# DL0WH_BiTuner_Ctrl_1V3.net
KiCad netlist of a schematic drawn in EAGLE
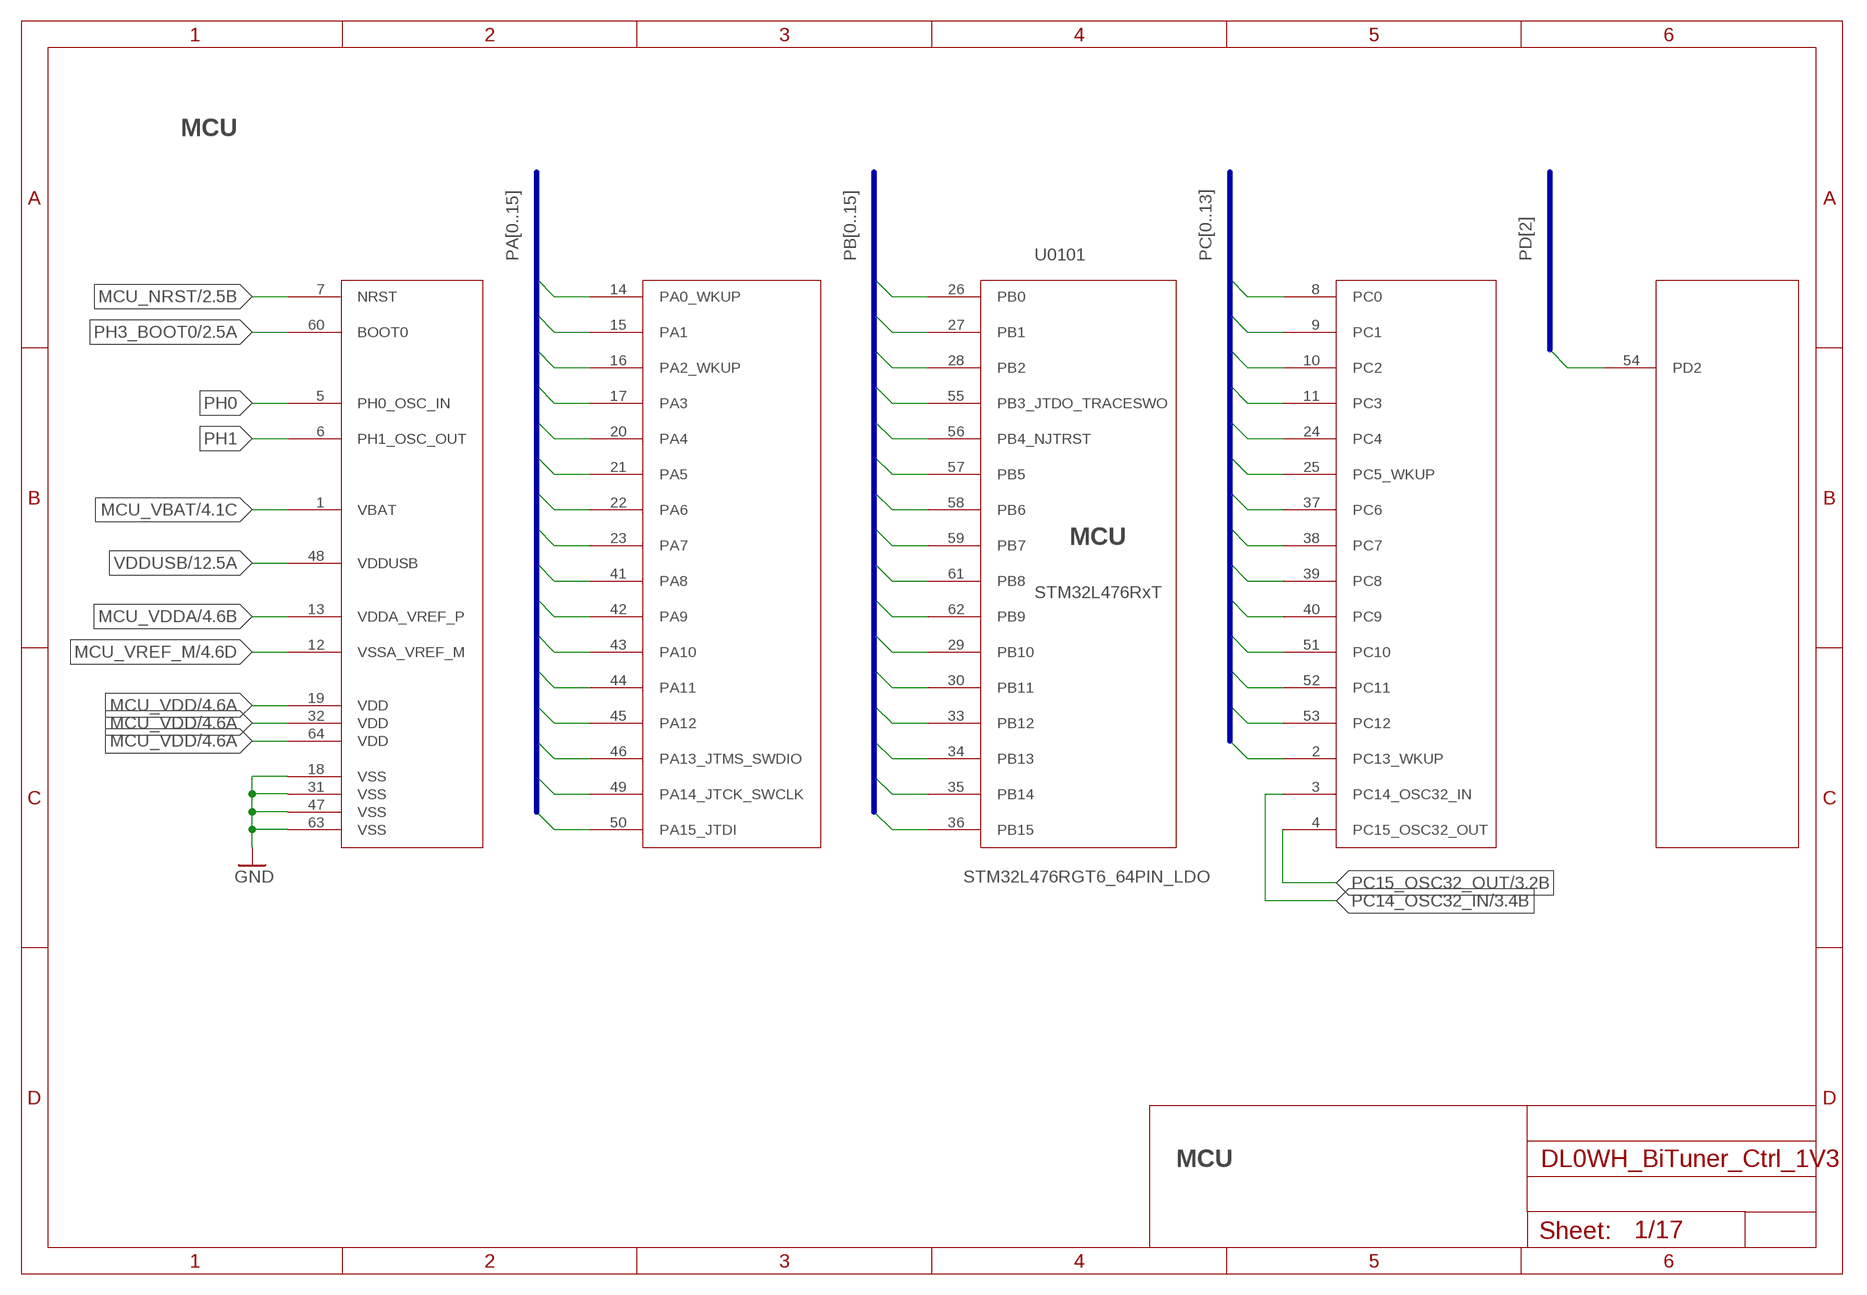
[diagram p0: schematic, sheet 1]
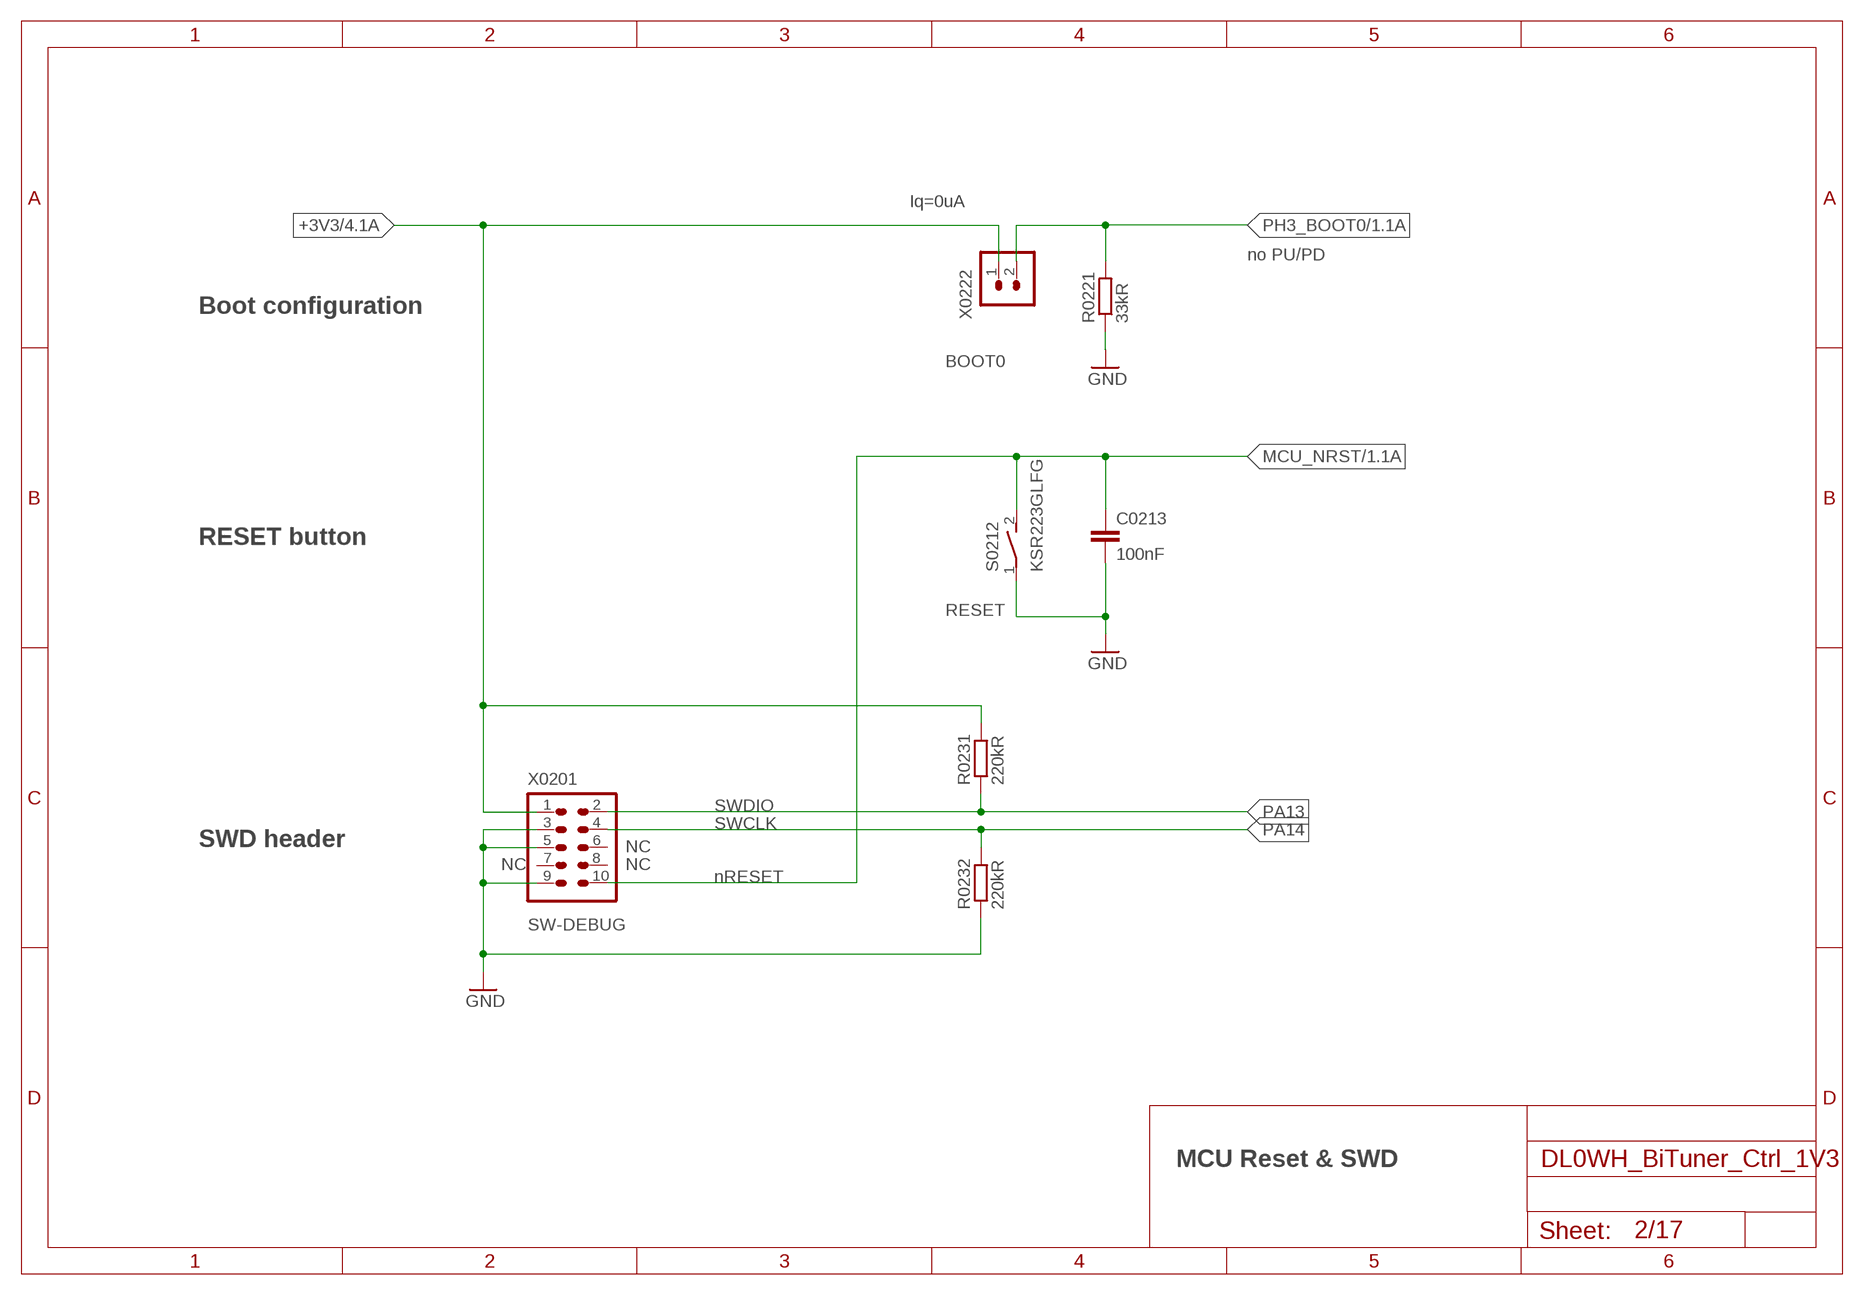
[diagram p1: schematic, sheet 2]
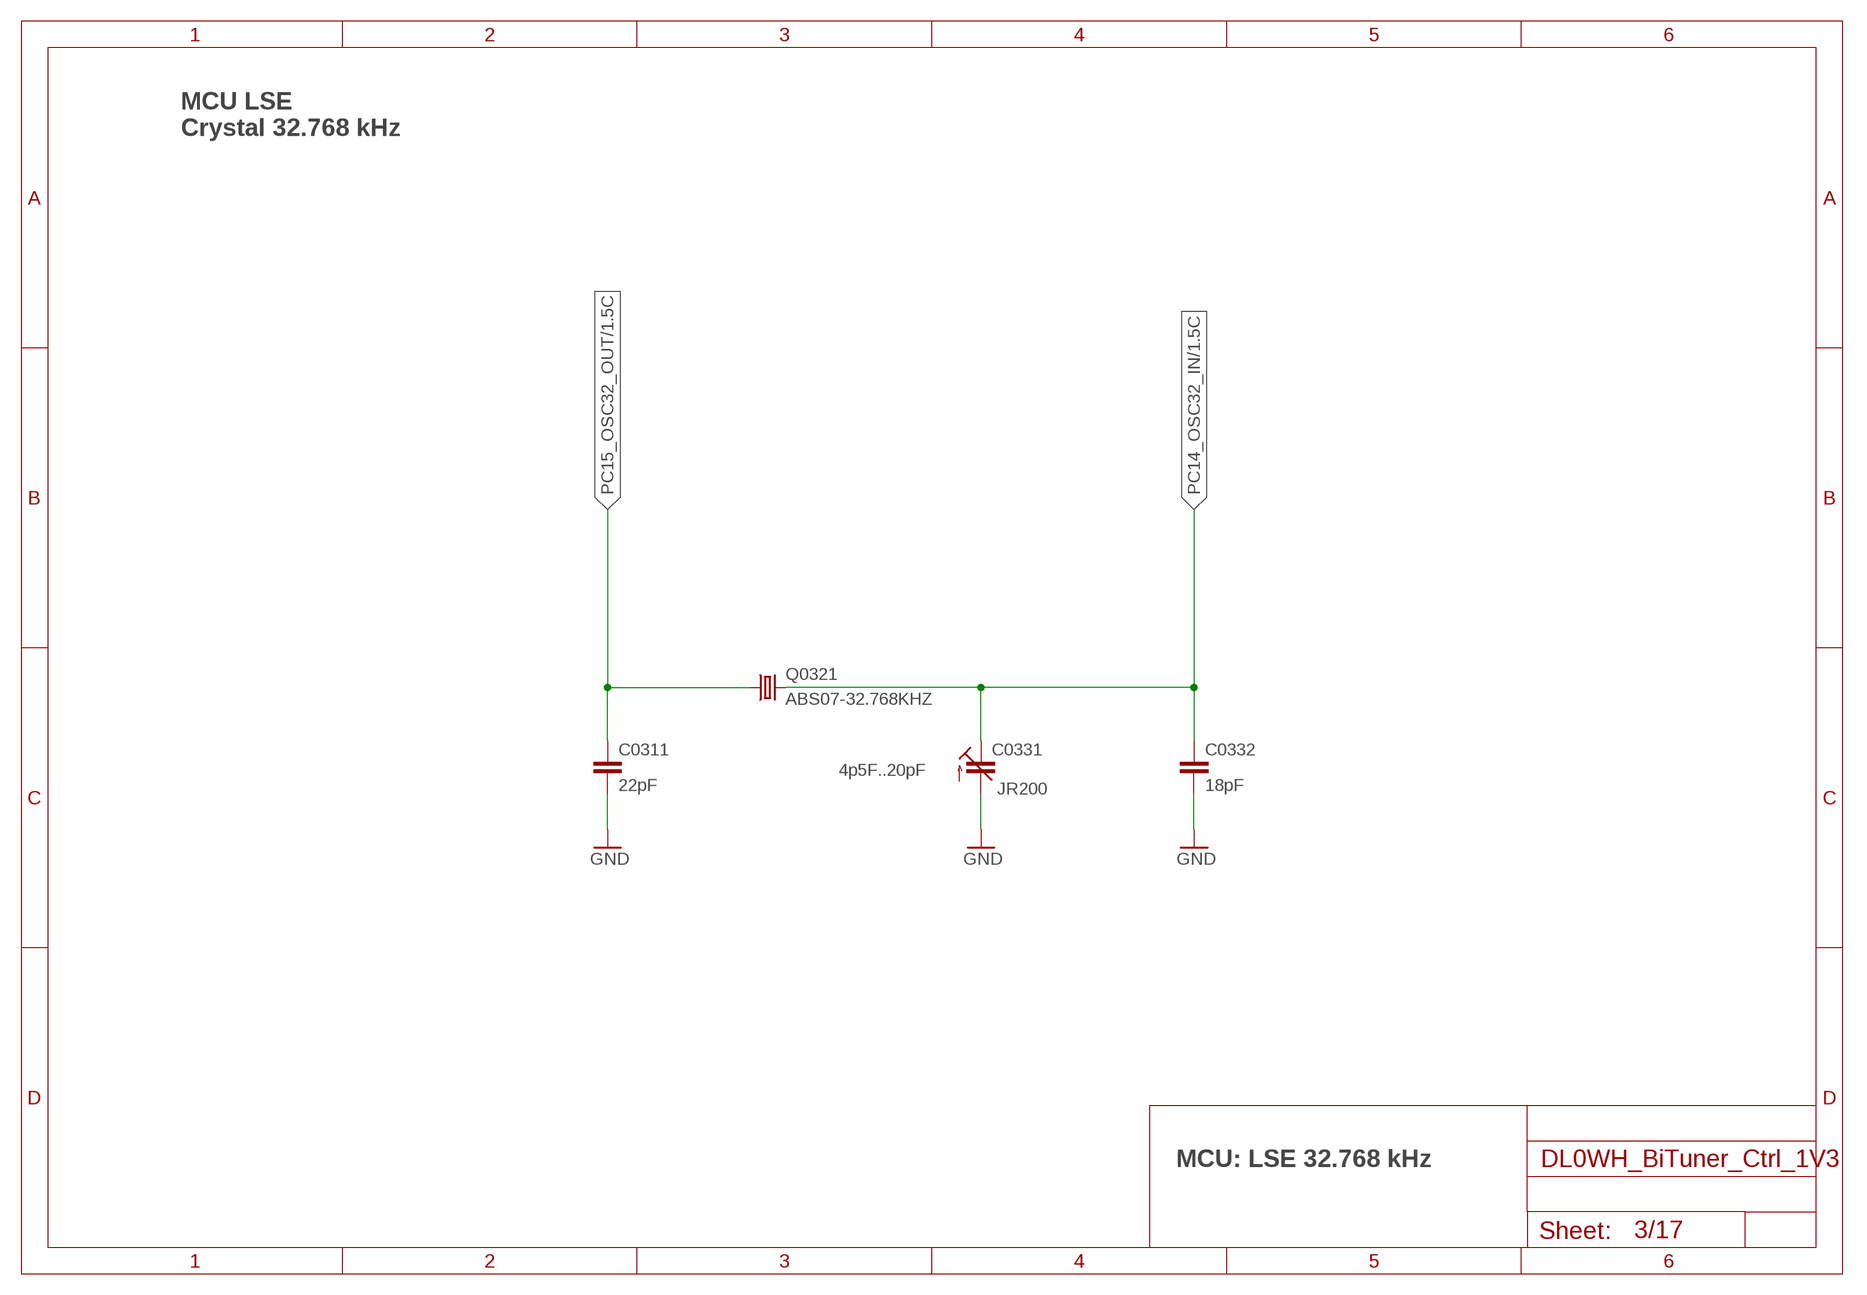
[diagram p2: schematic, sheet 3]
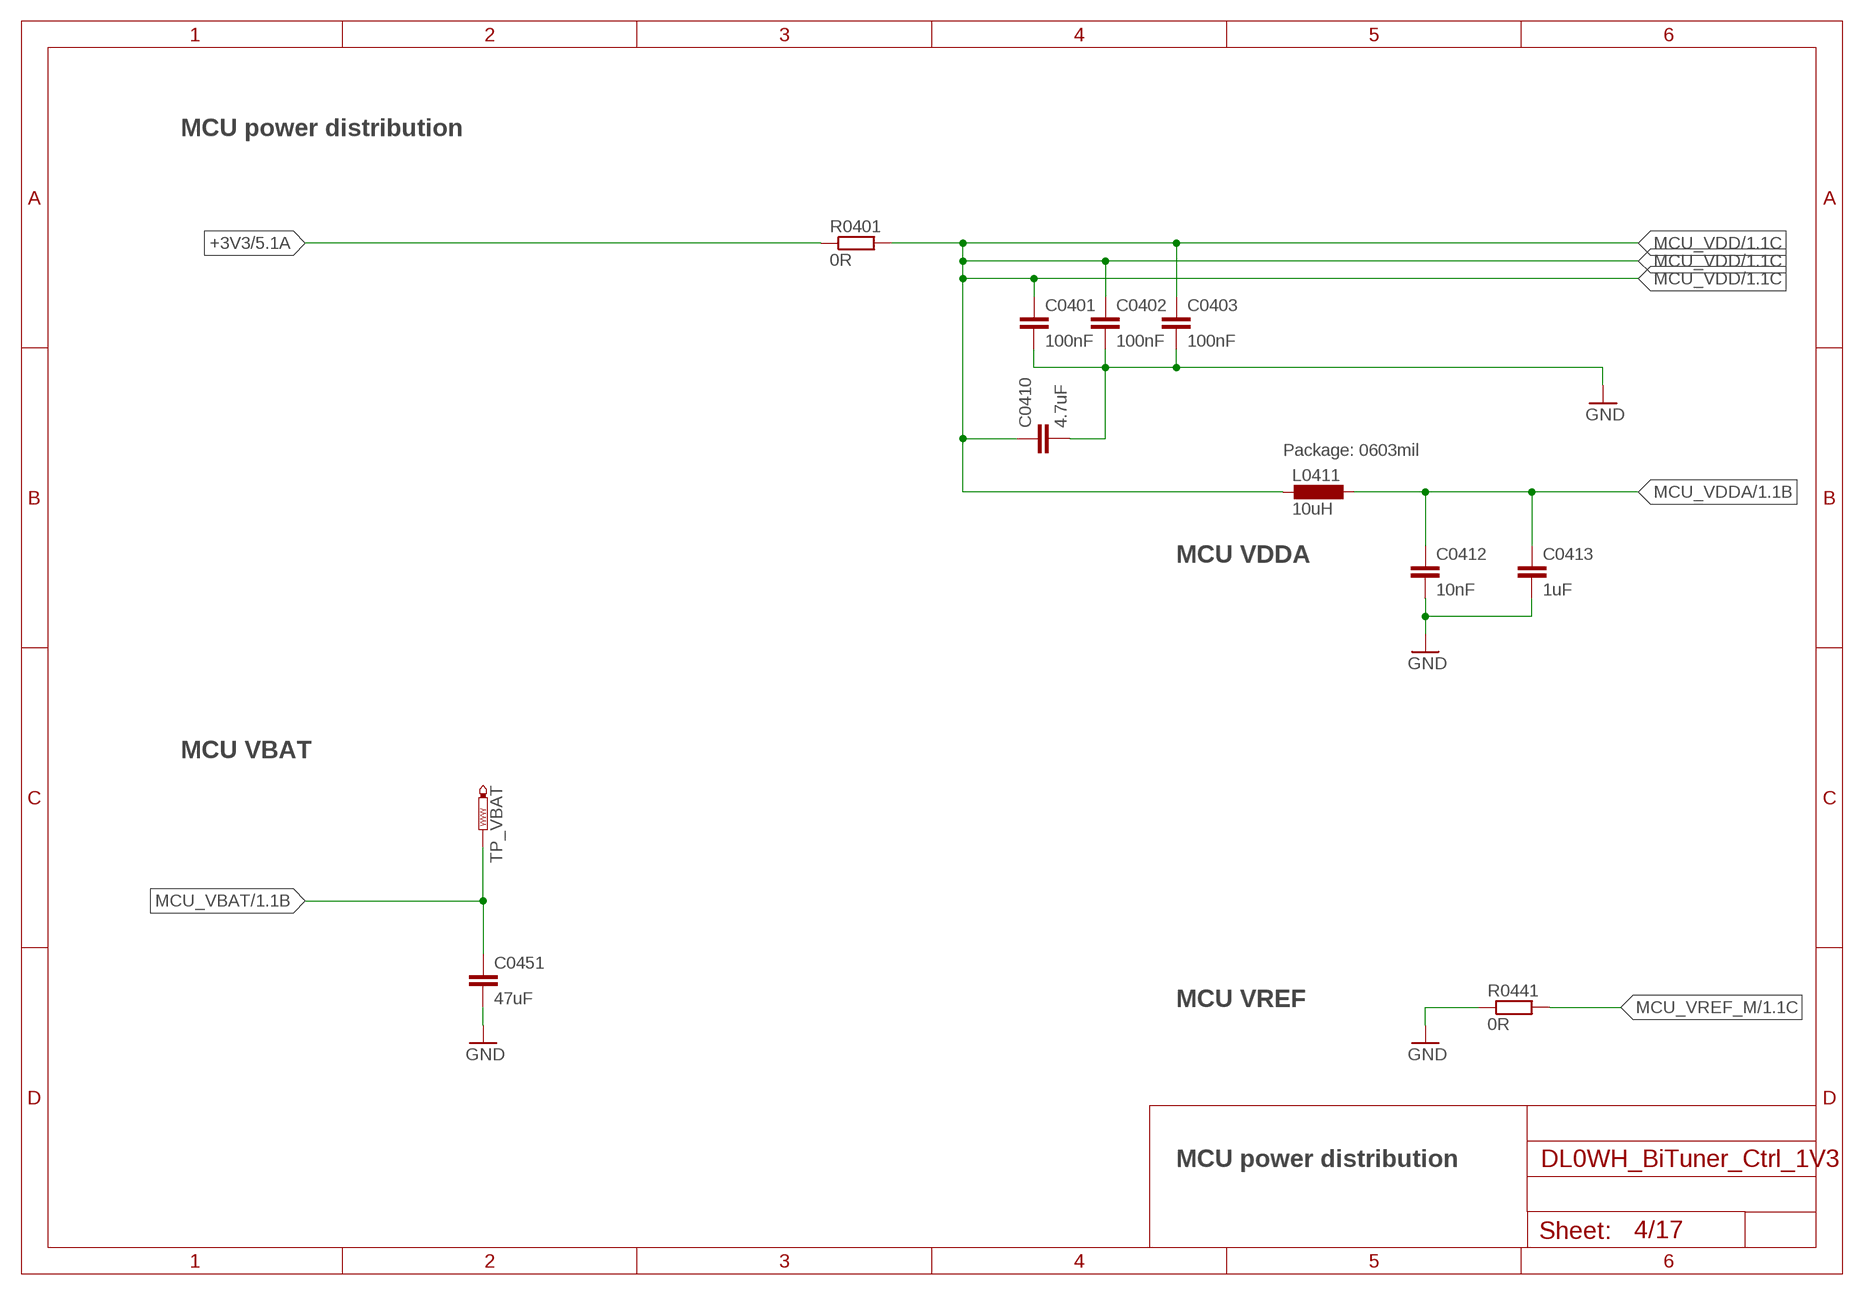
[diagram p3: schematic, sheet 4]
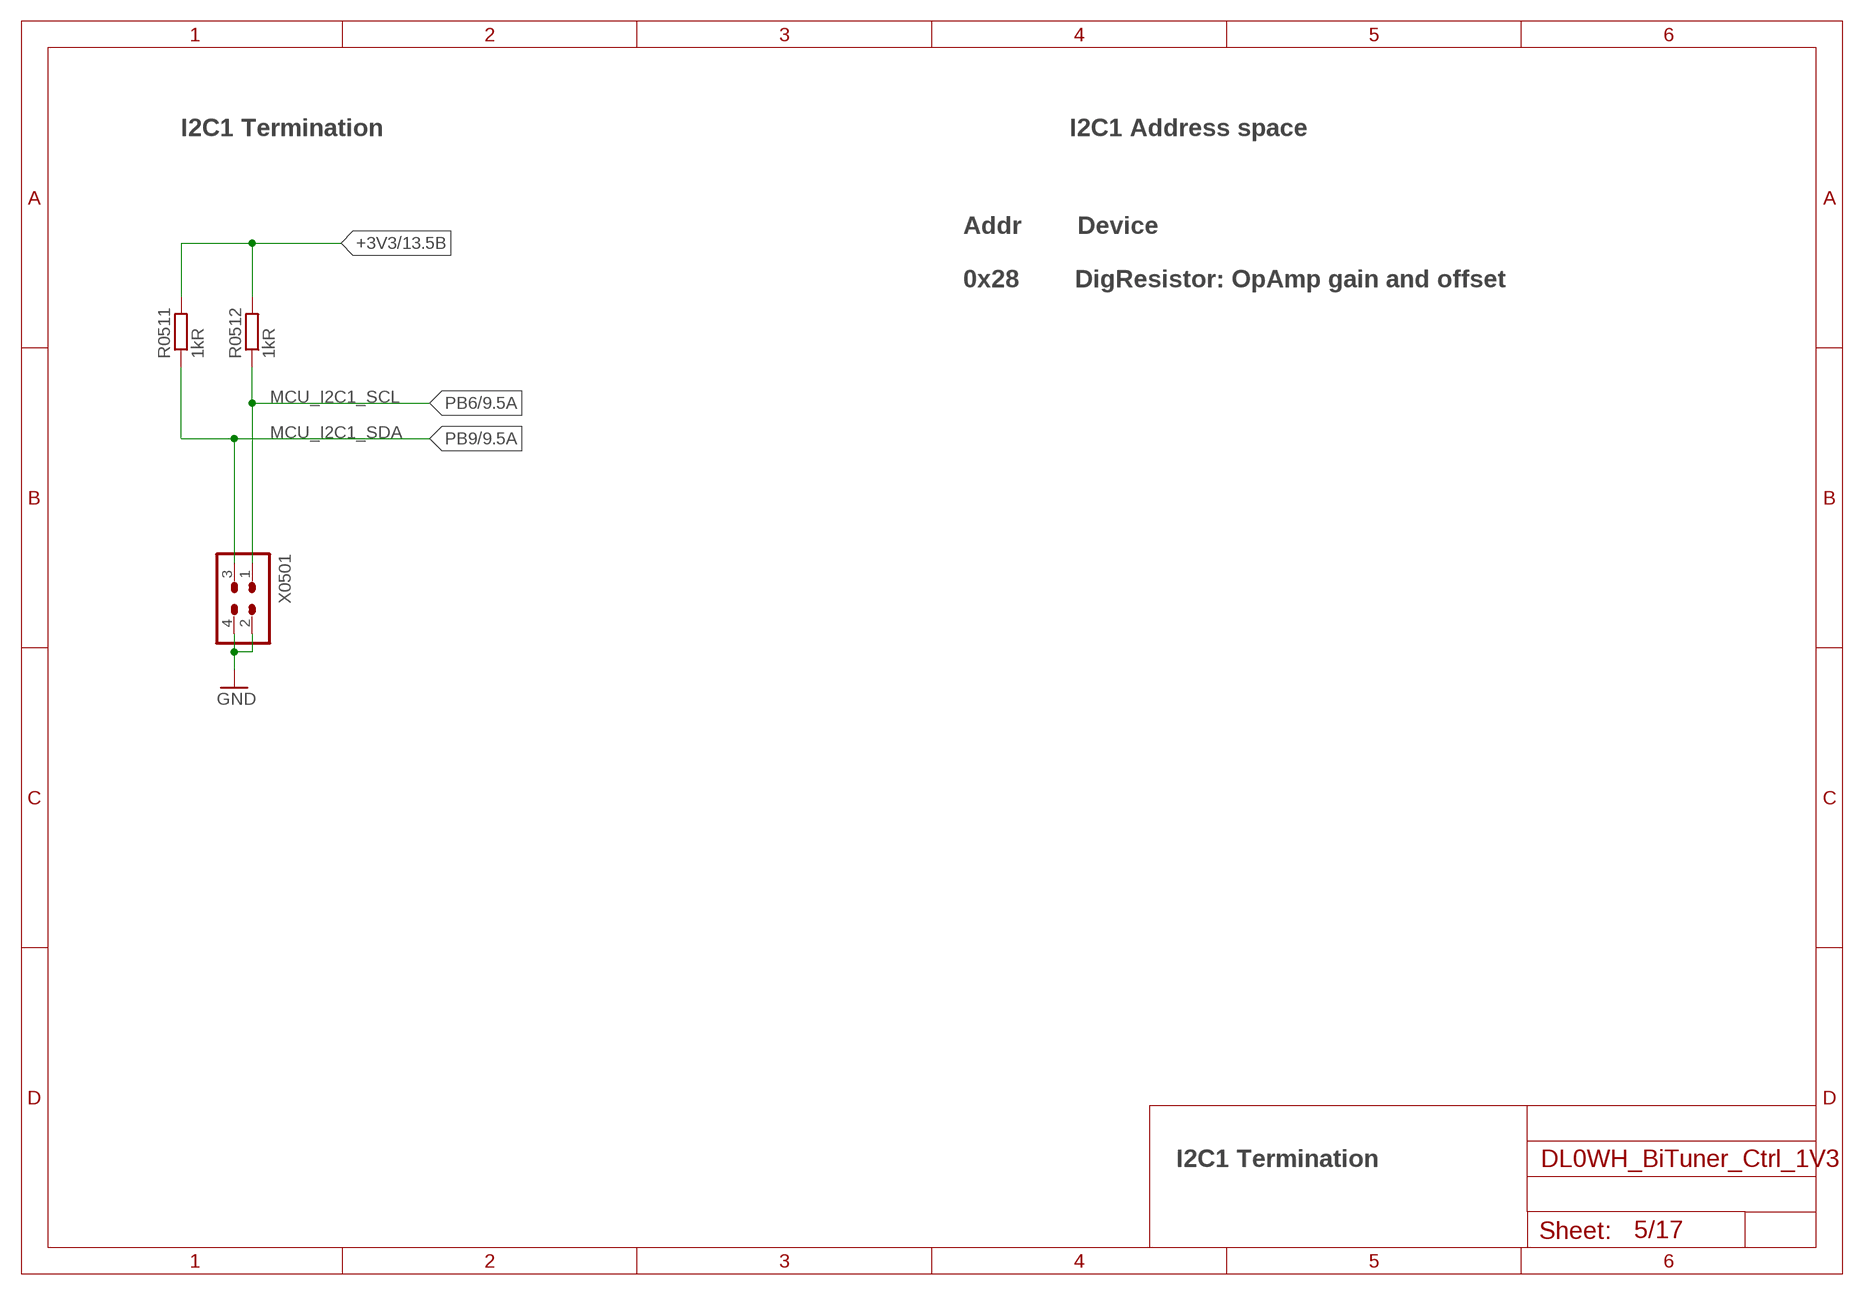
[diagram p4: schematic, sheet 5]
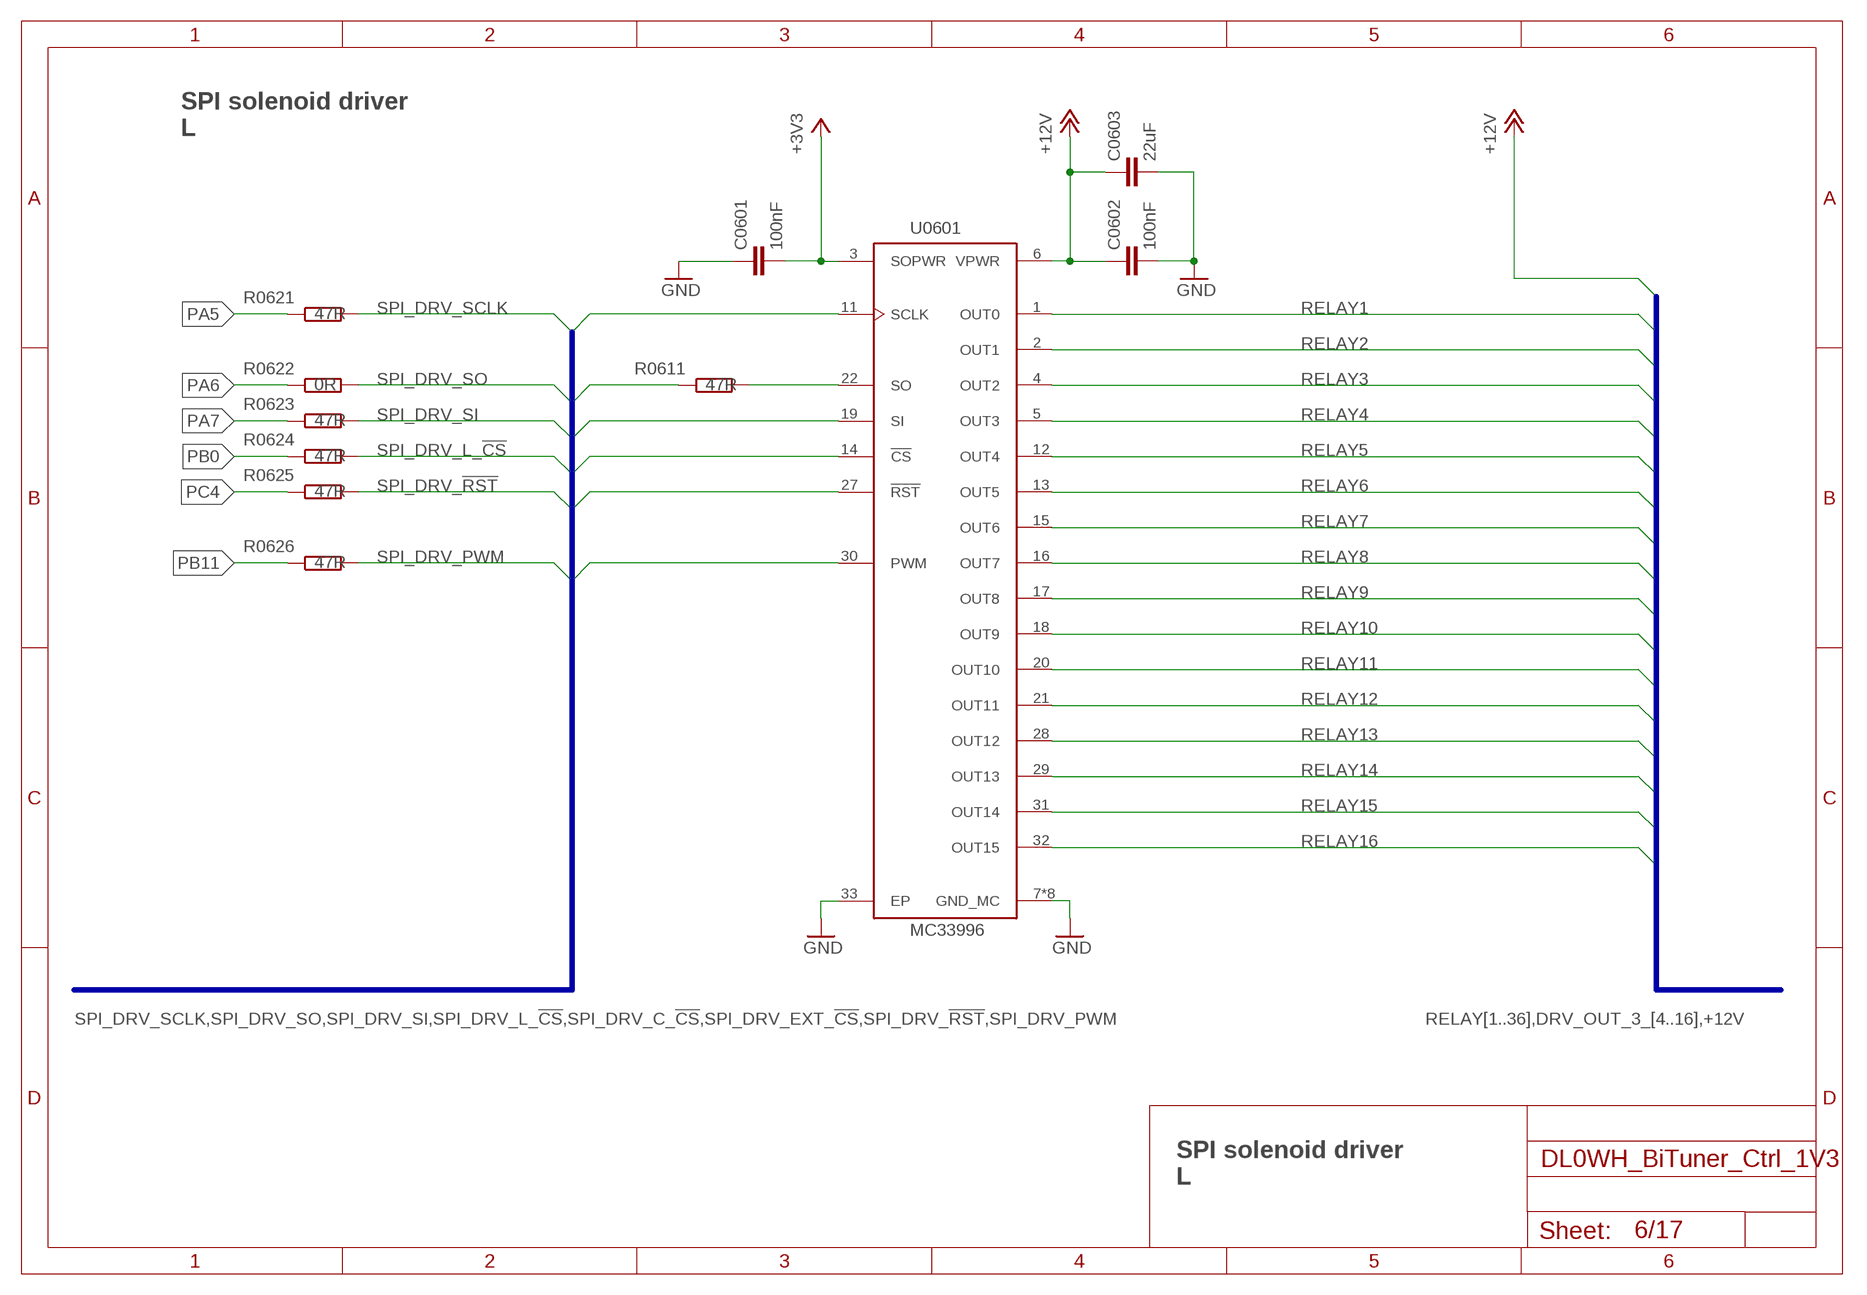
[diagram p5: schematic, sheet 6]
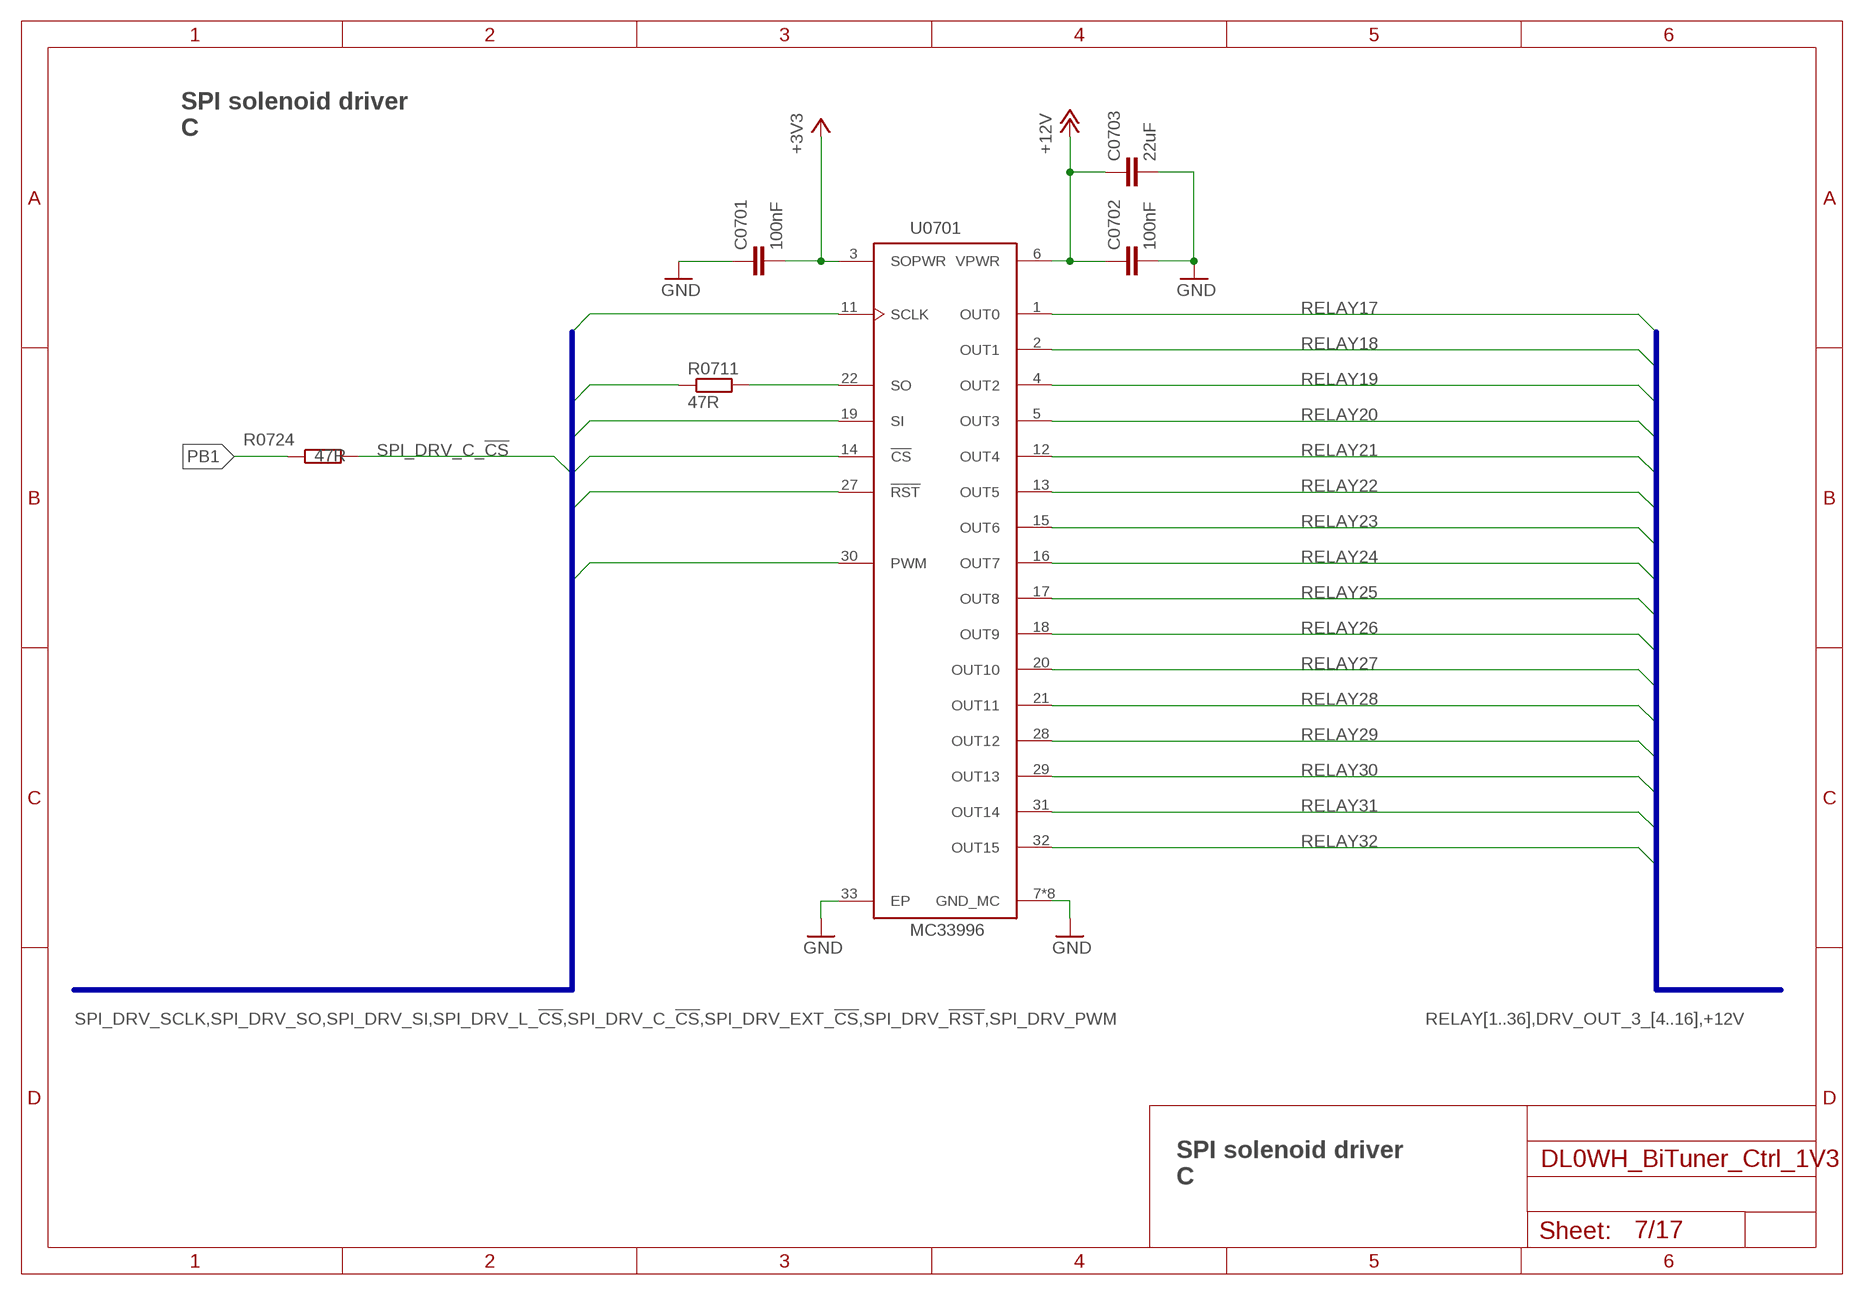
[diagram p6: schematic, sheet 7]
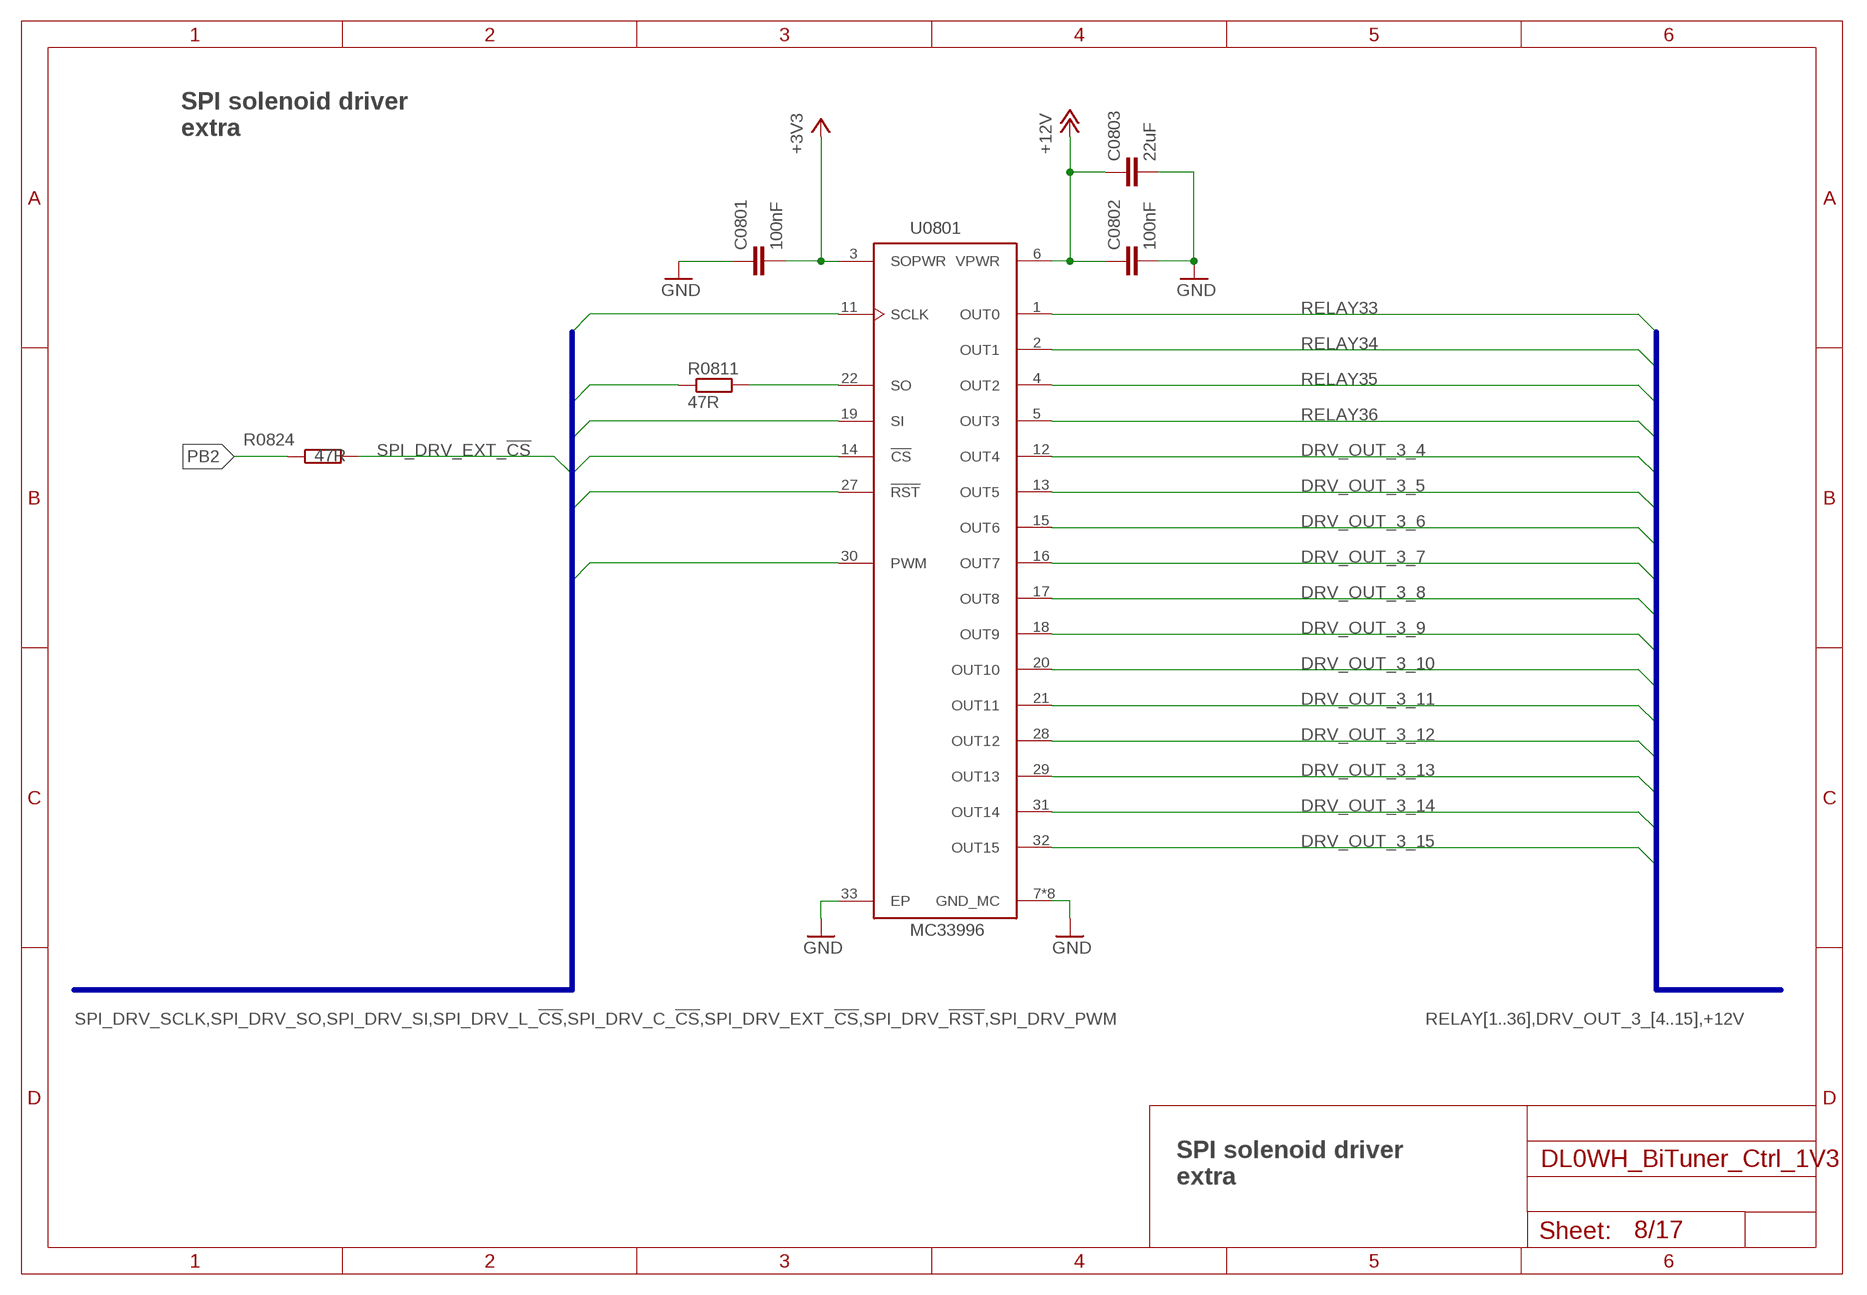
[diagram p7: schematic, sheet 8]
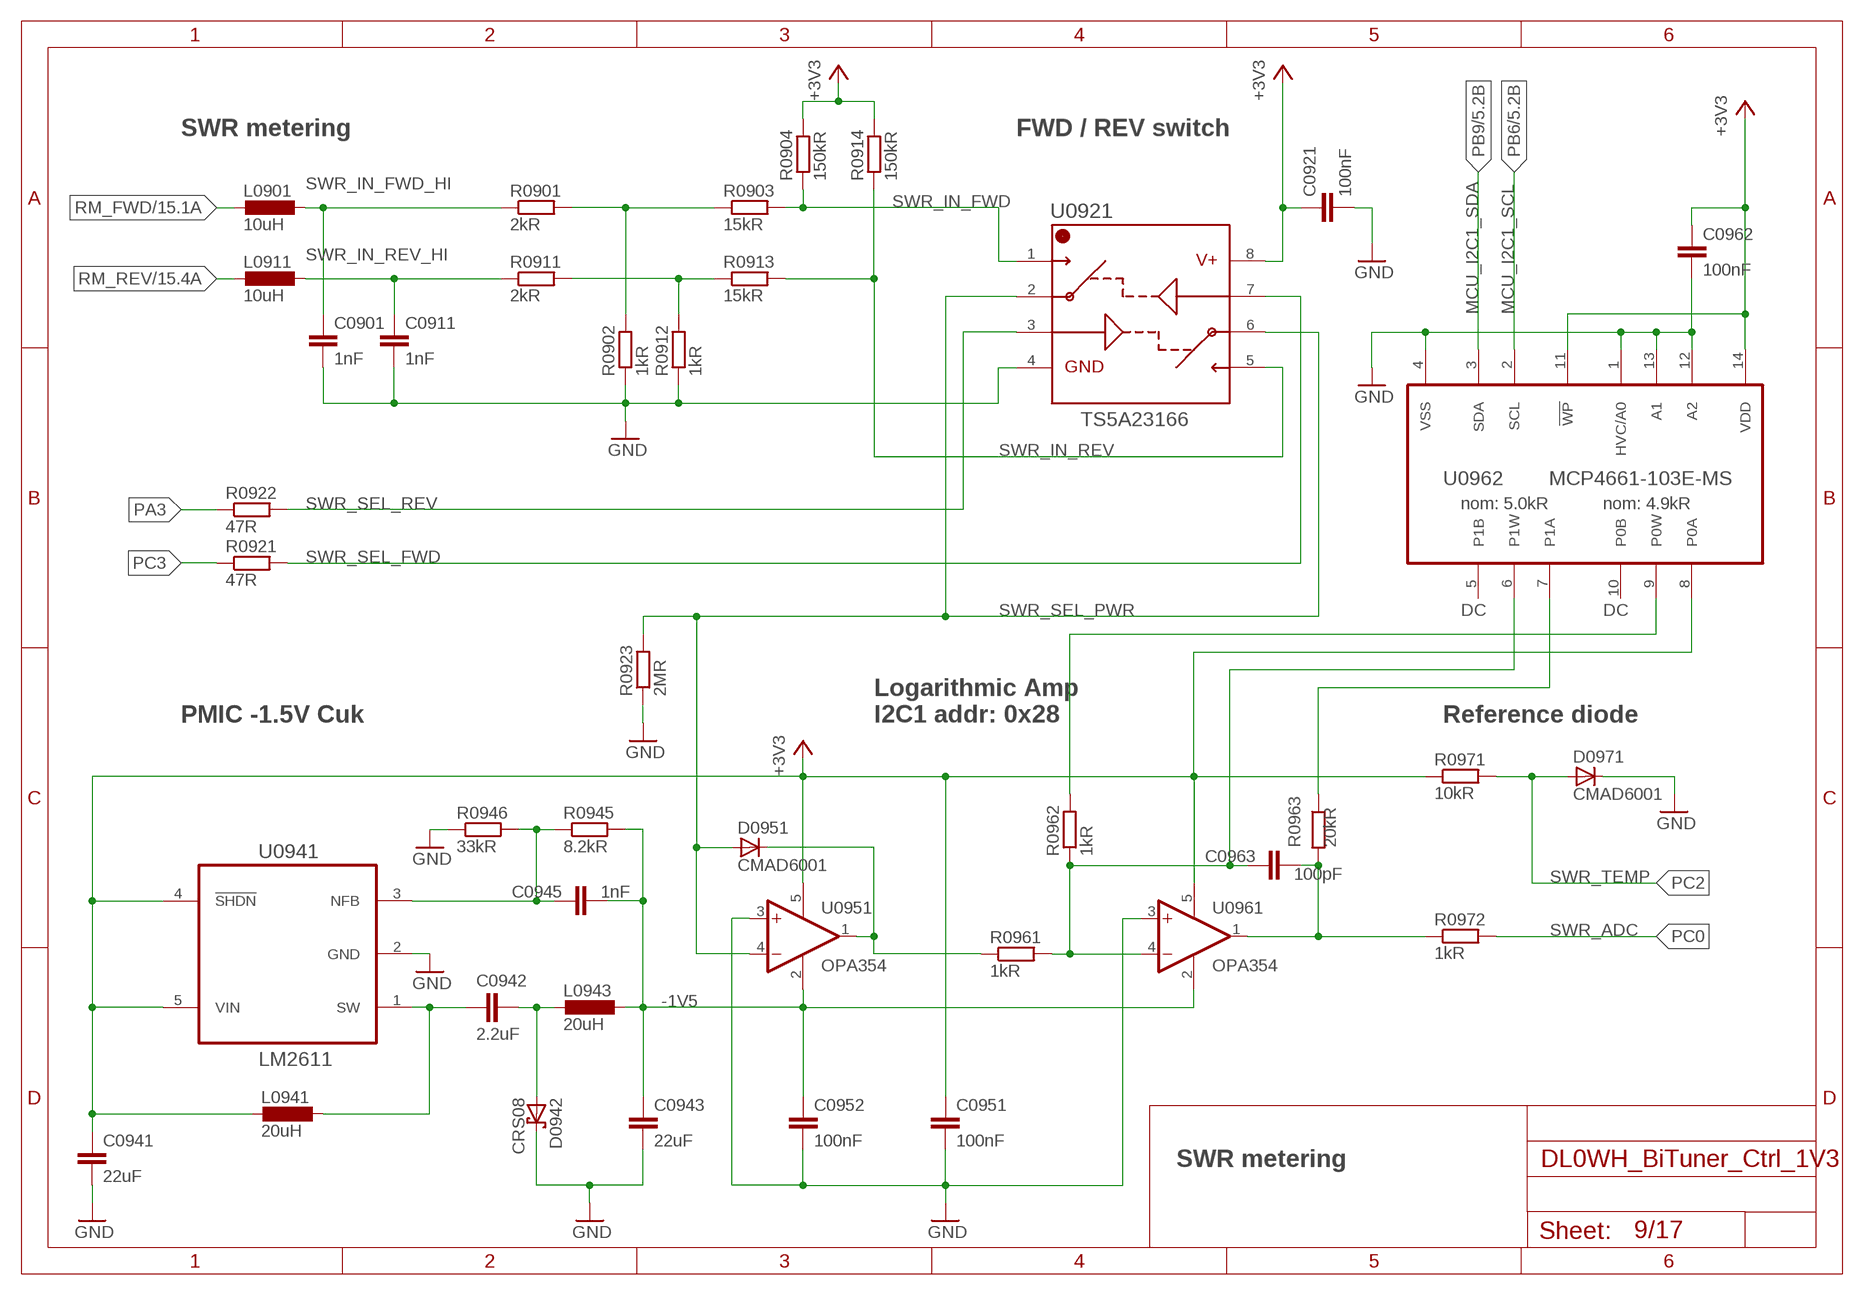
[diagram p8: schematic, sheet 9]
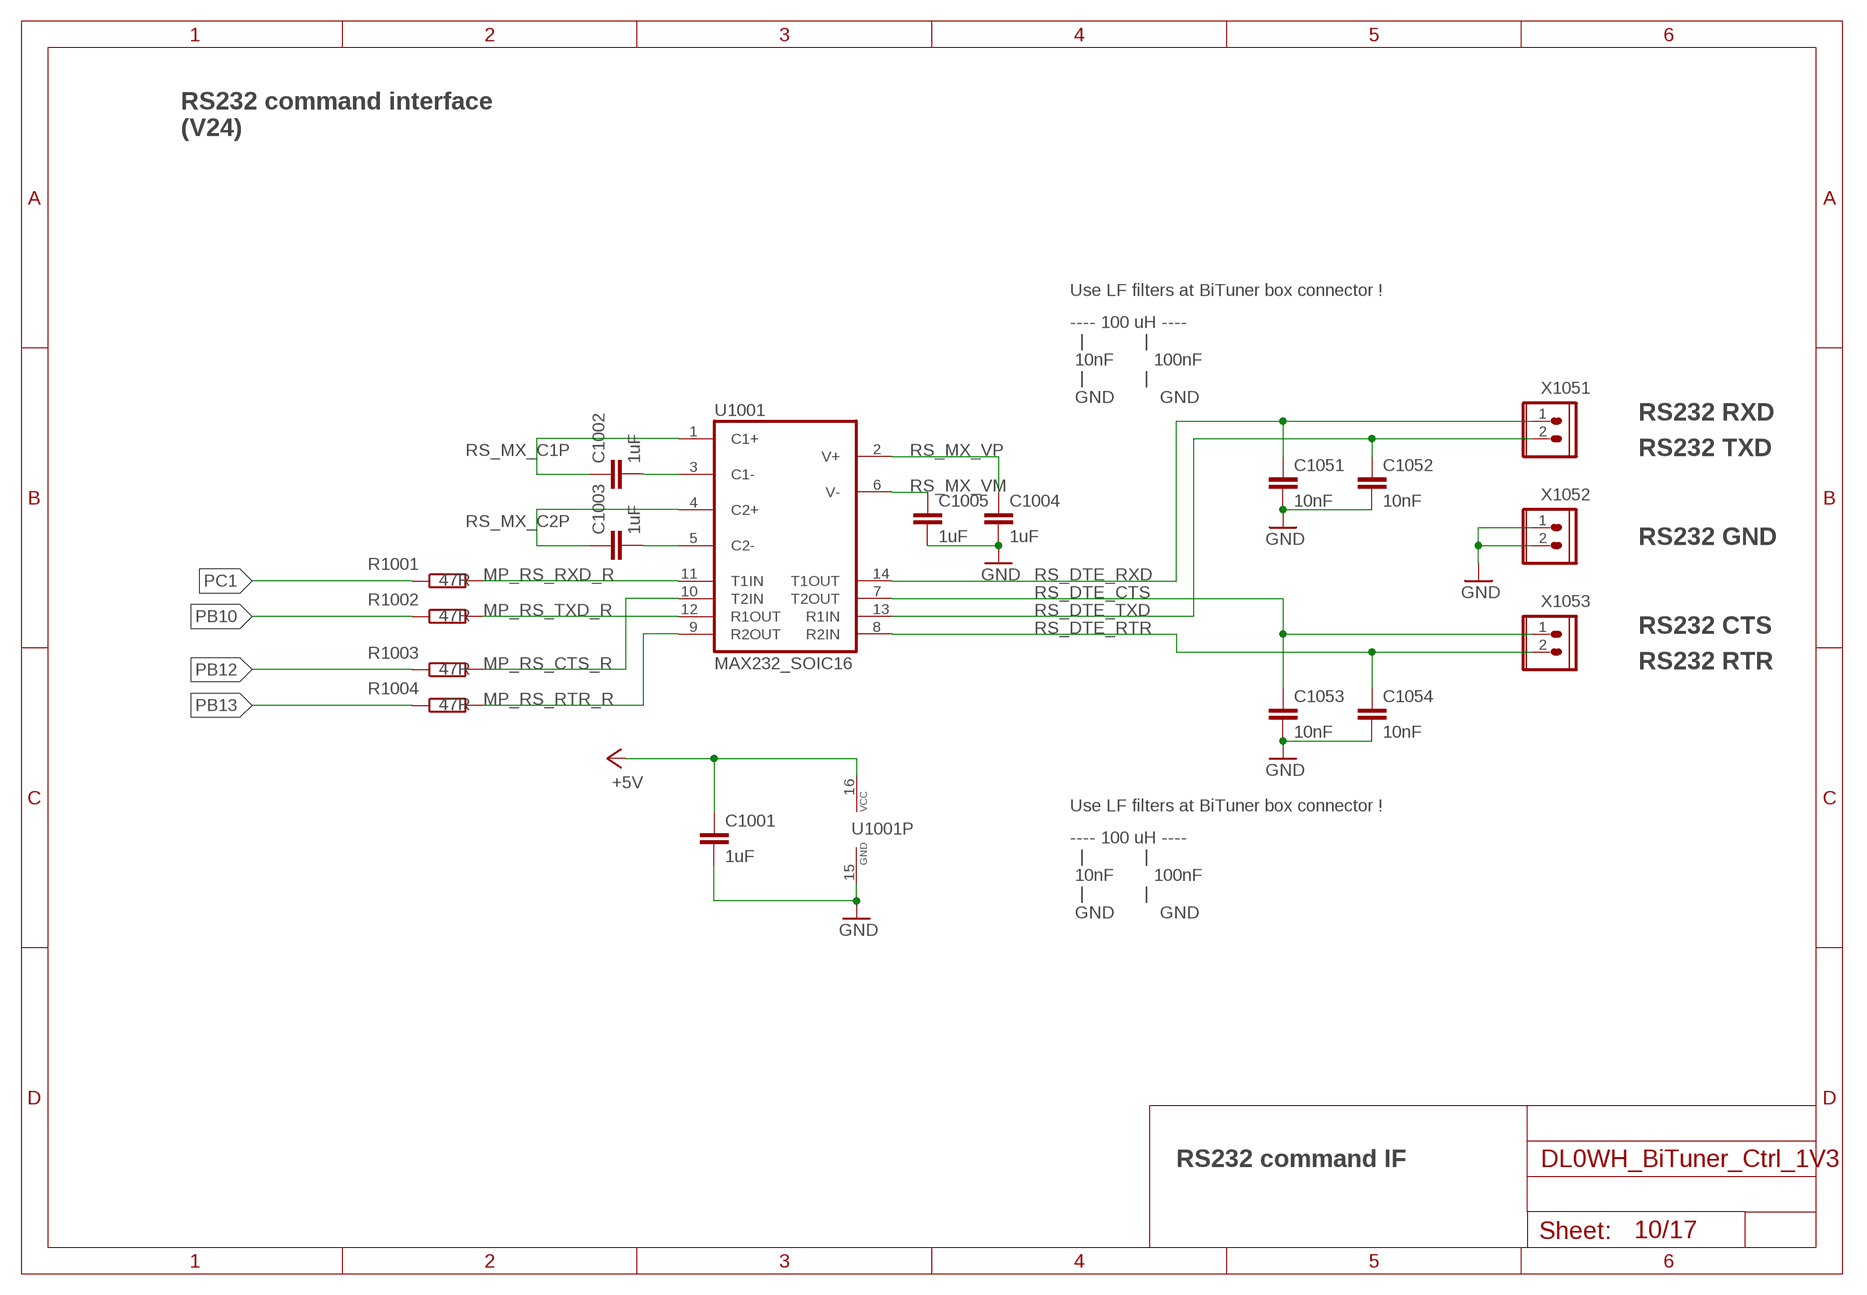
[diagram p9: schematic, sheet 10]
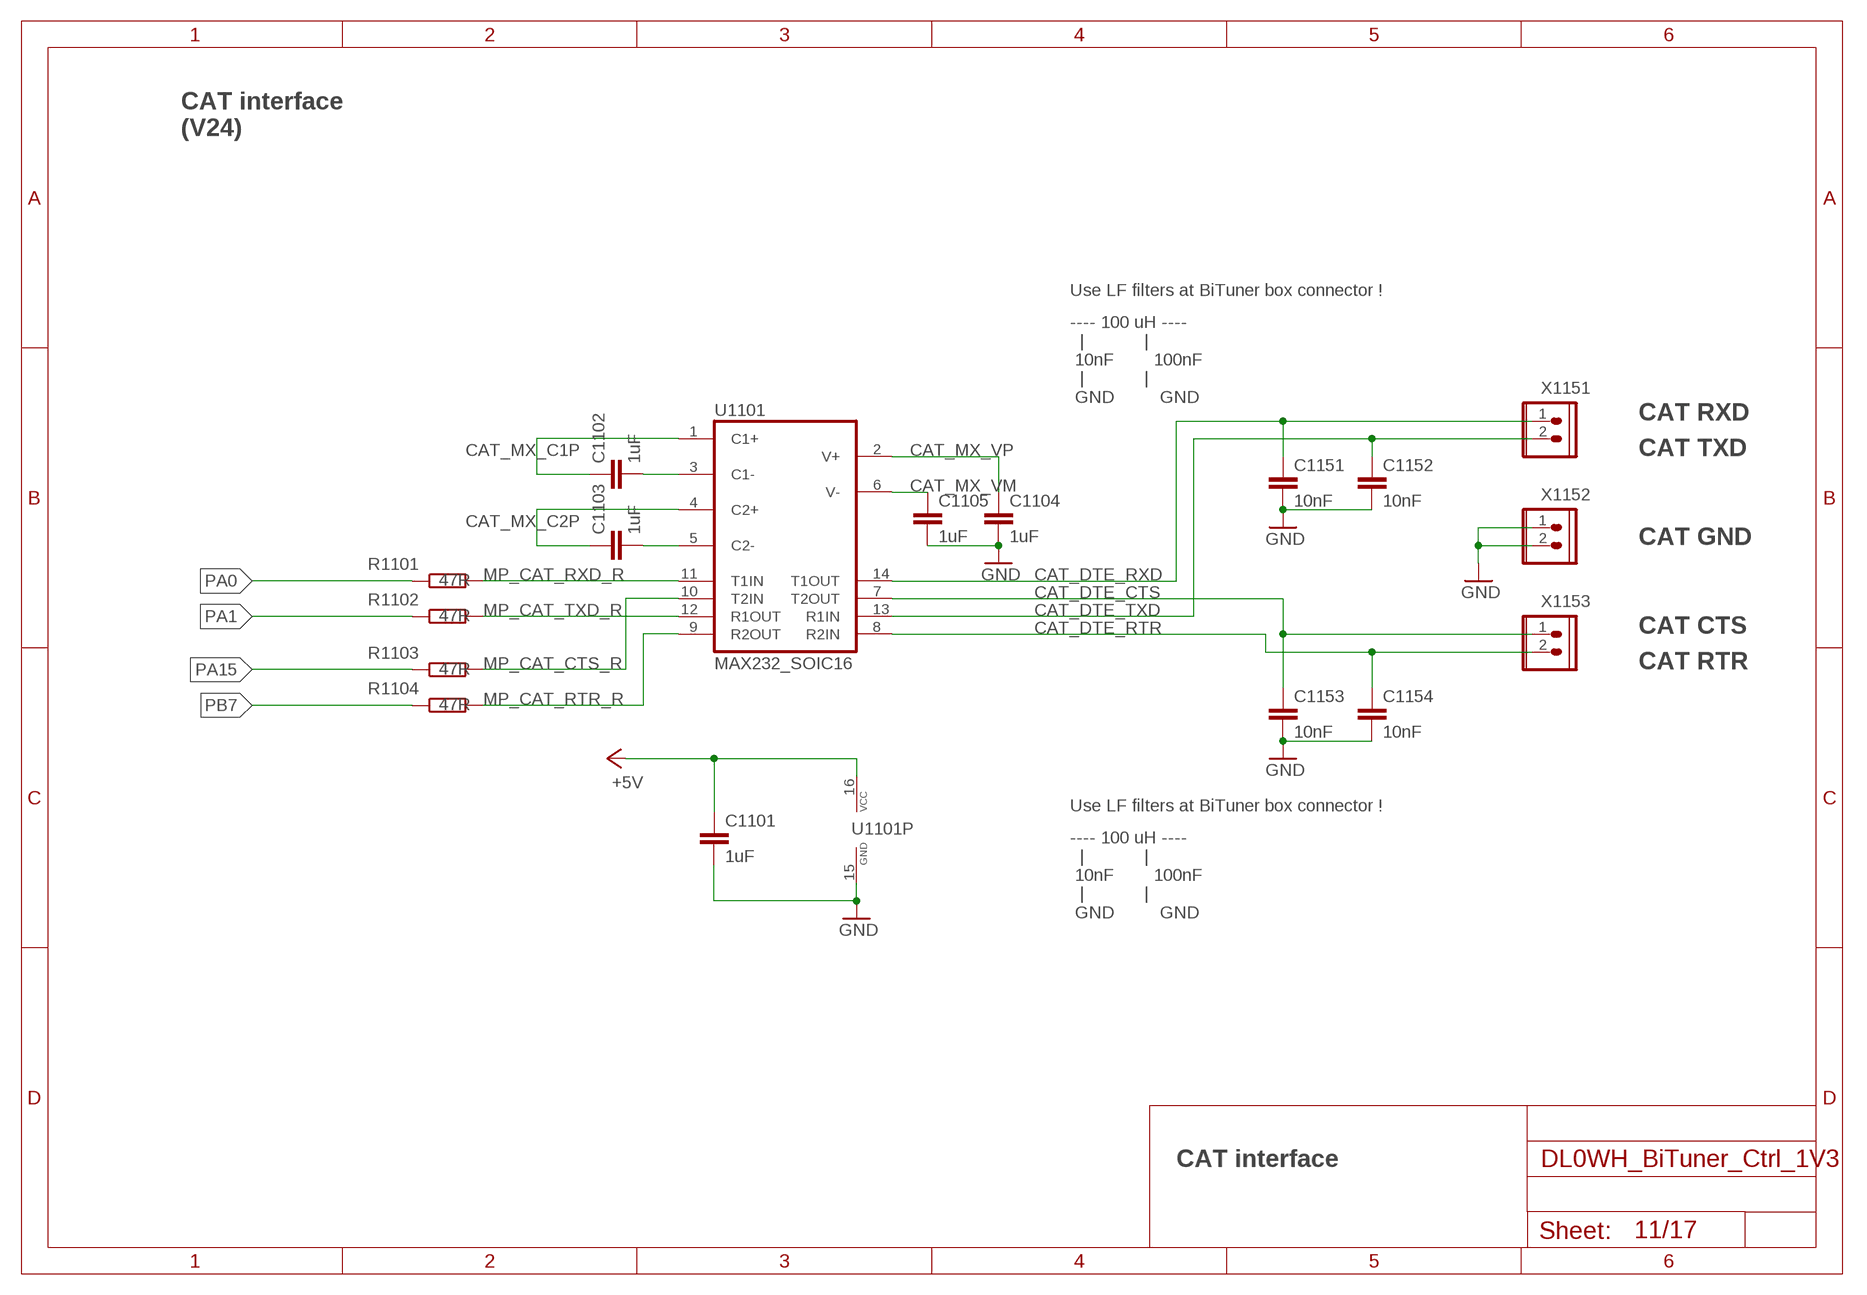
[diagram p10: schematic, sheet 11]
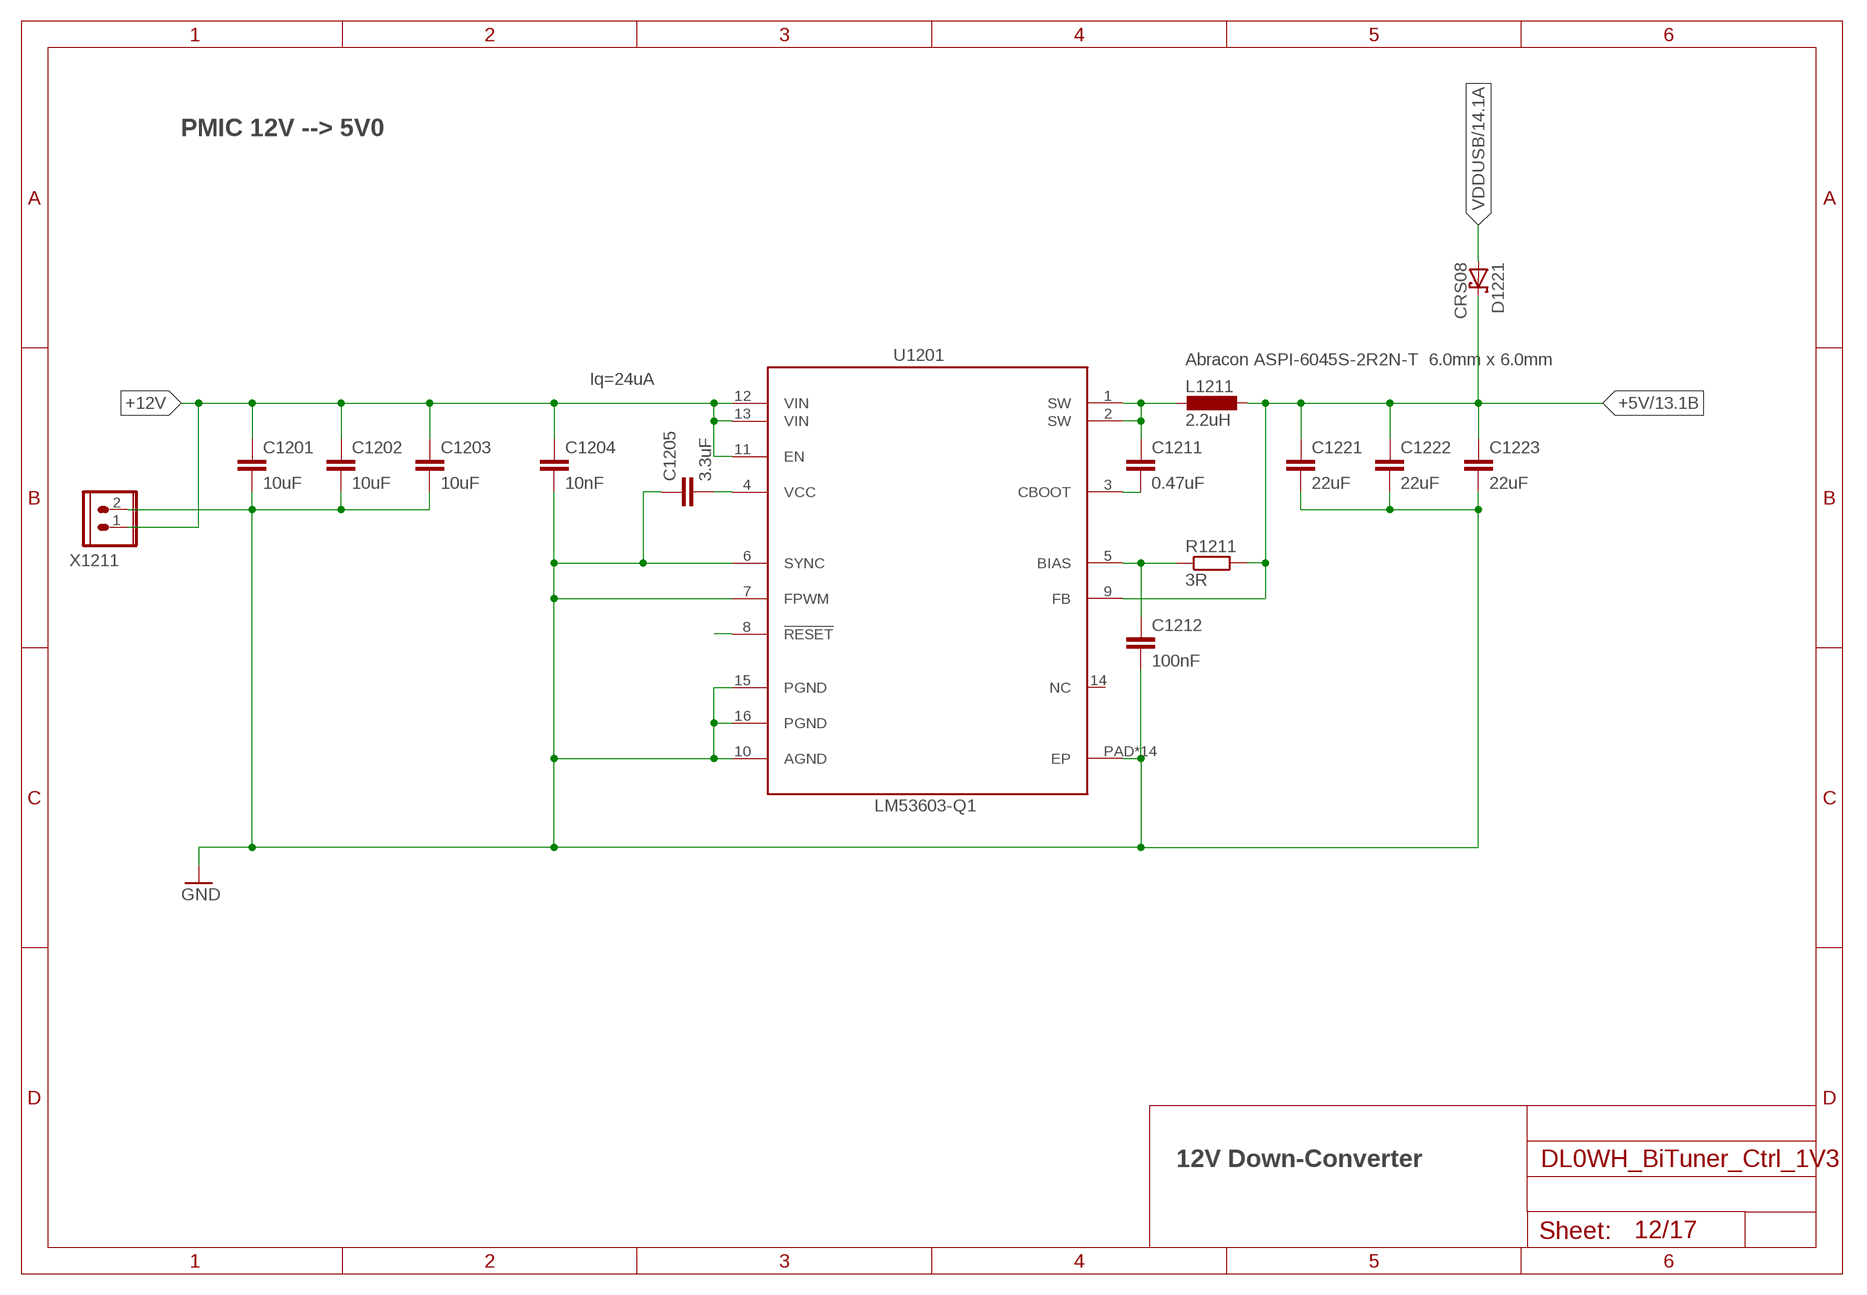
[diagram p11: schematic, sheet 12]
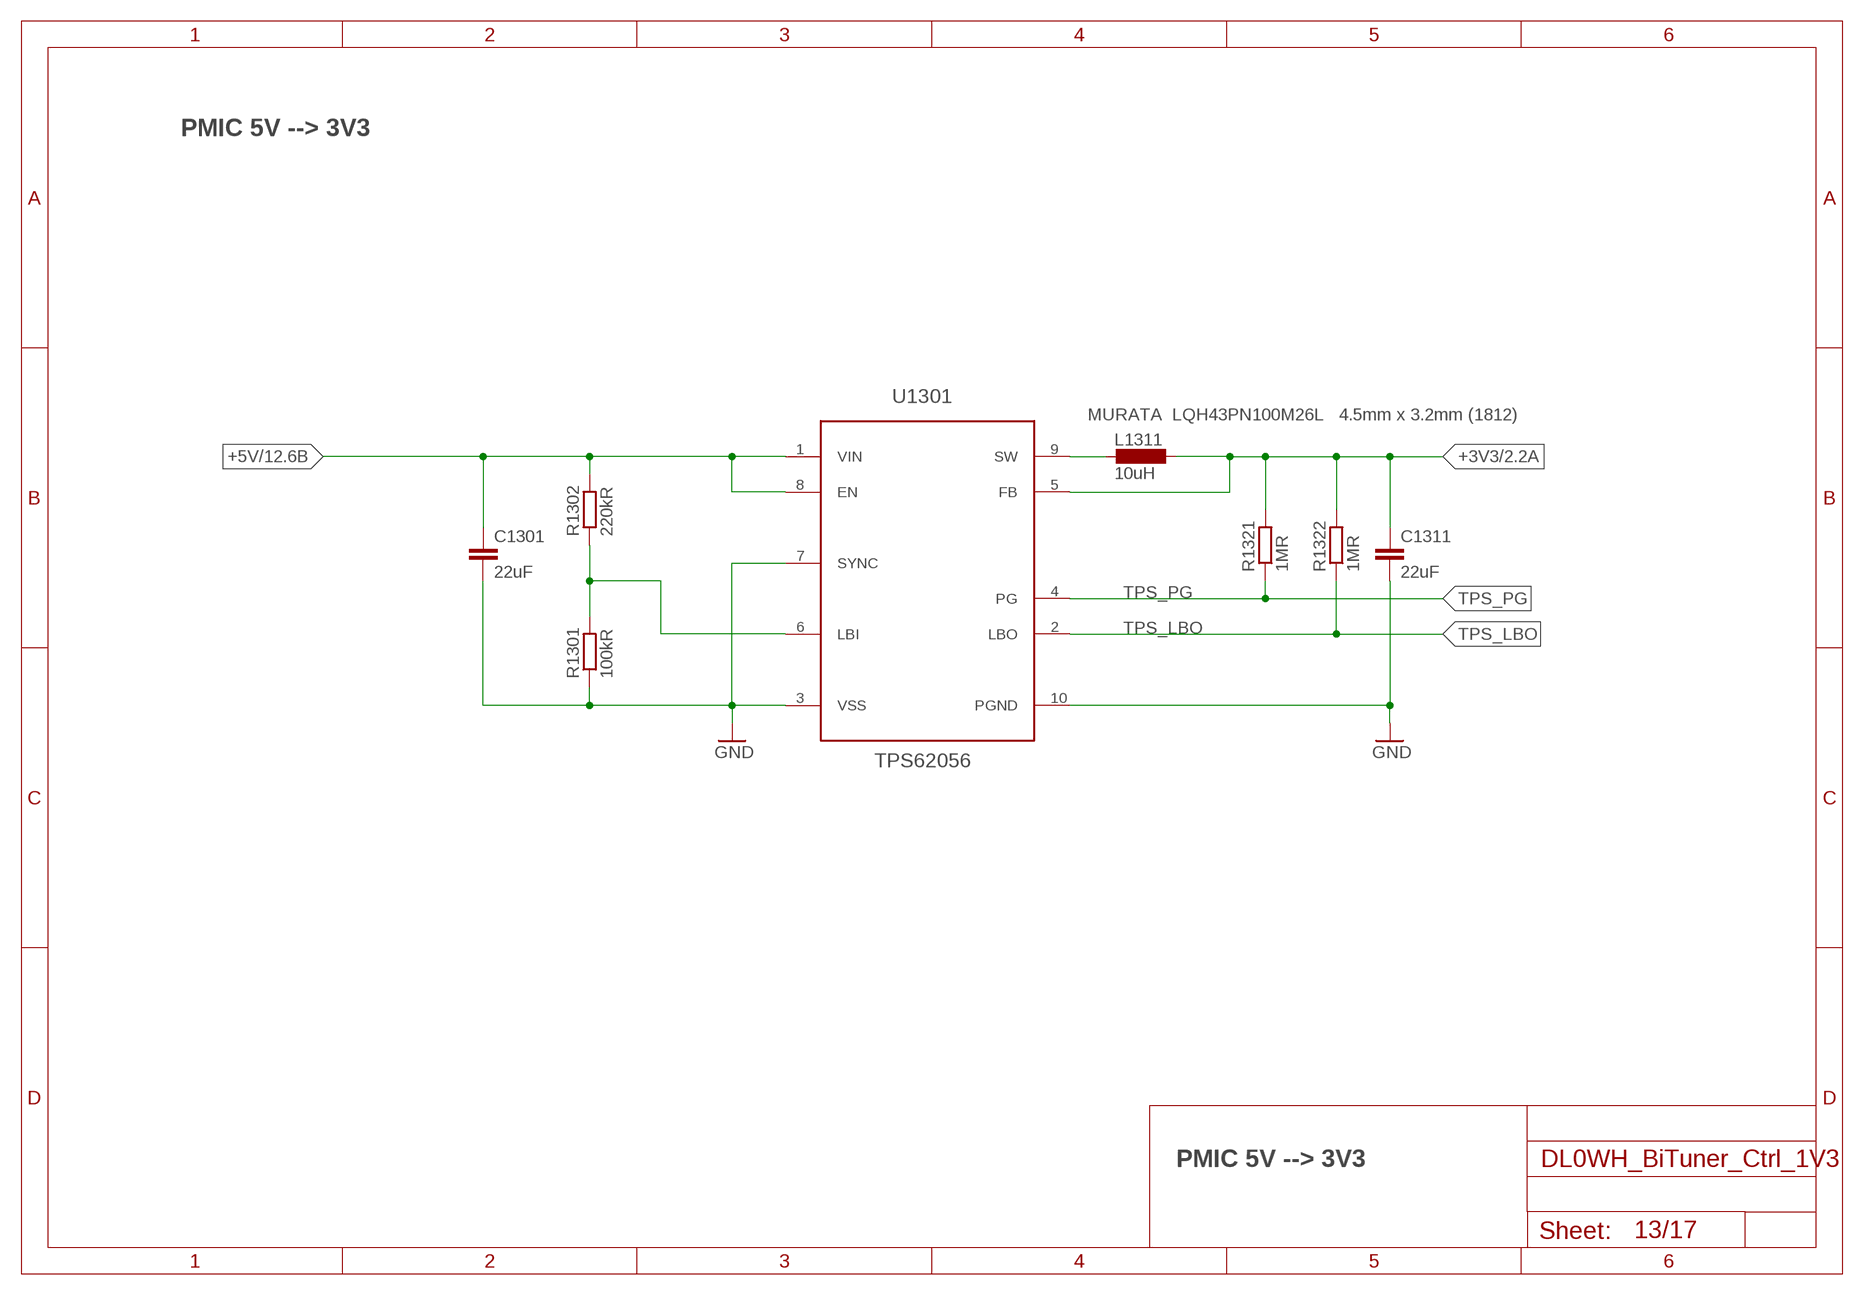
[diagram p12: schematic, sheet 13]
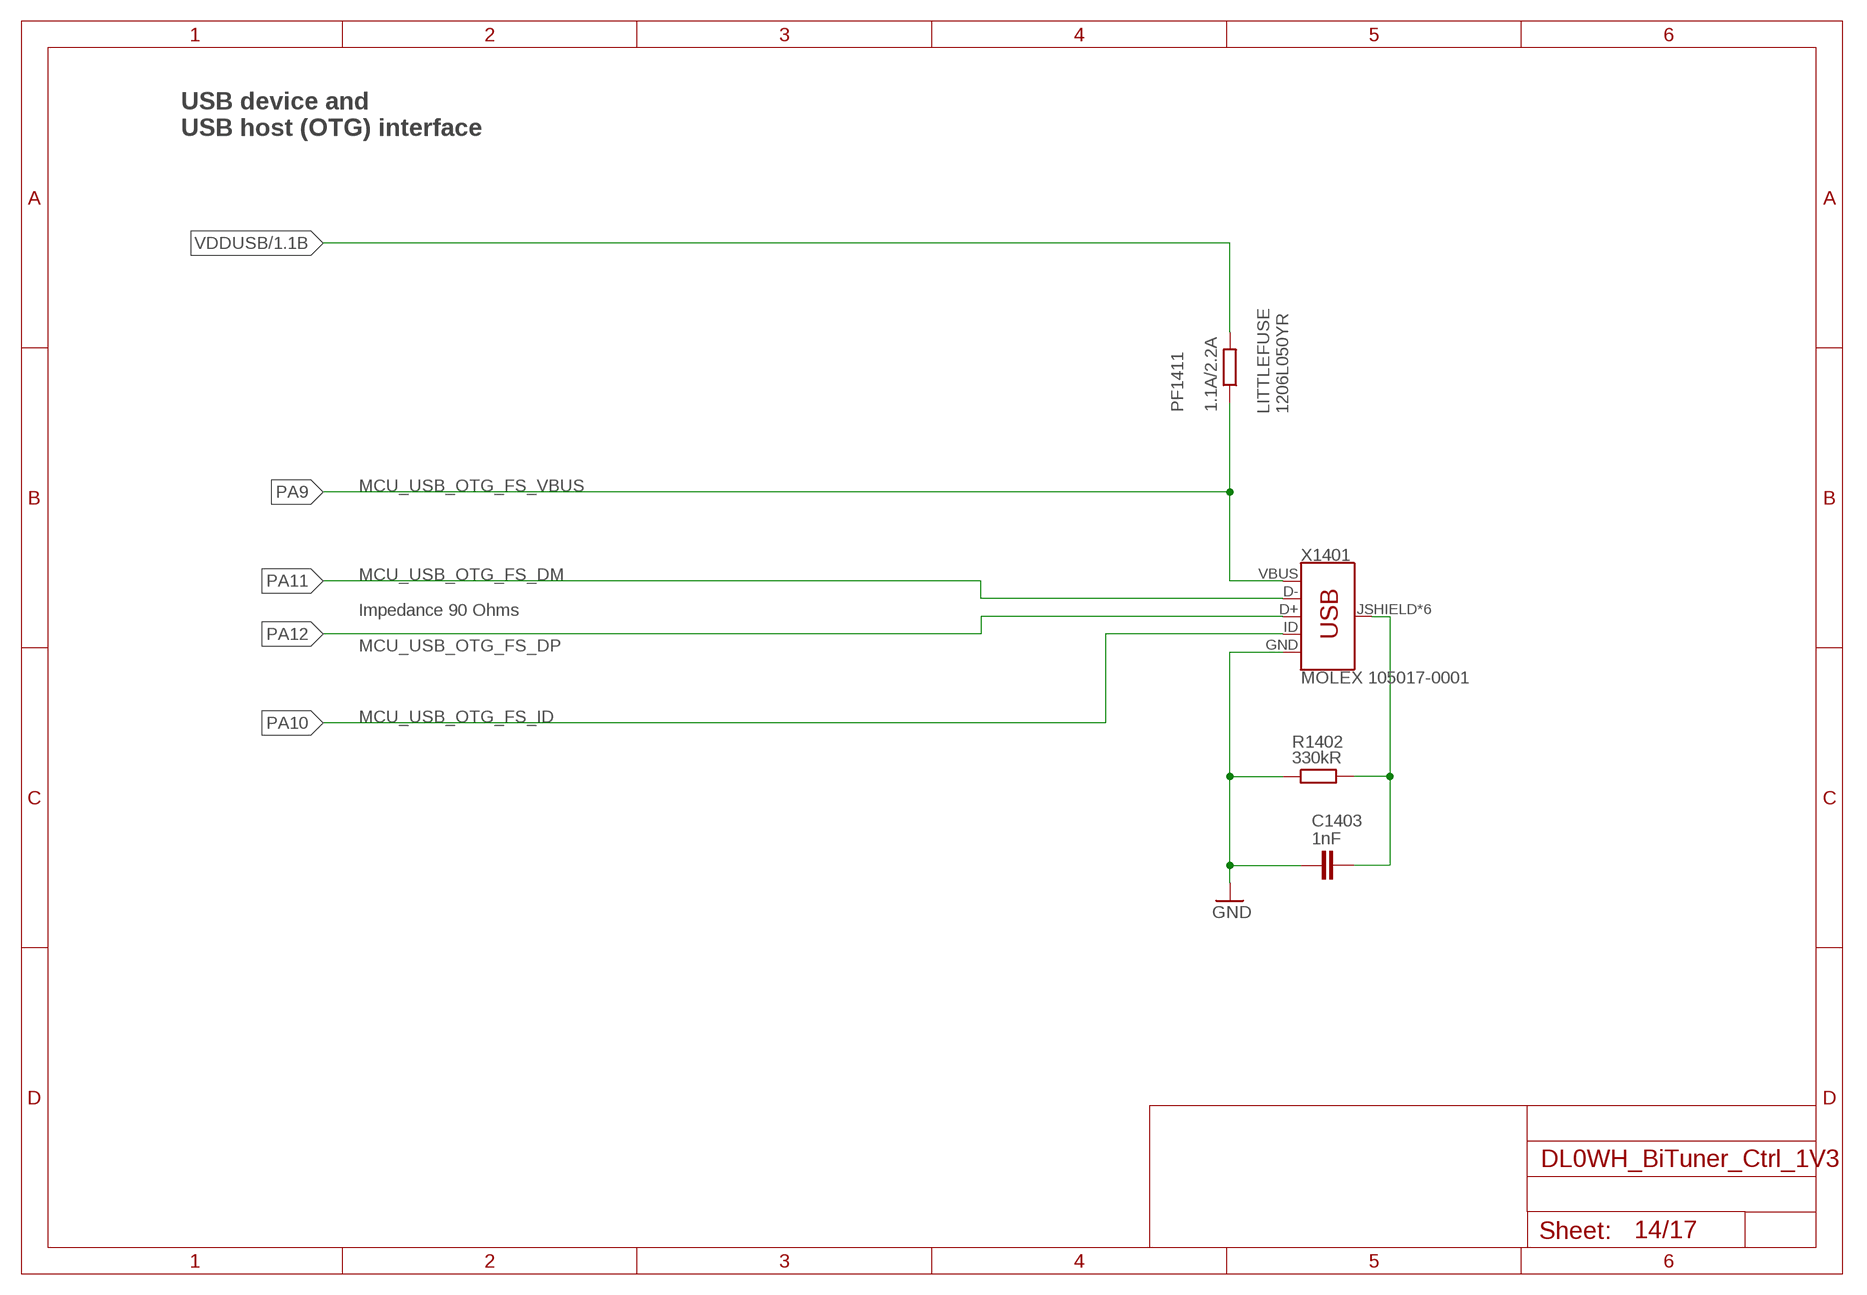
[diagram p13: schematic, sheet 14]
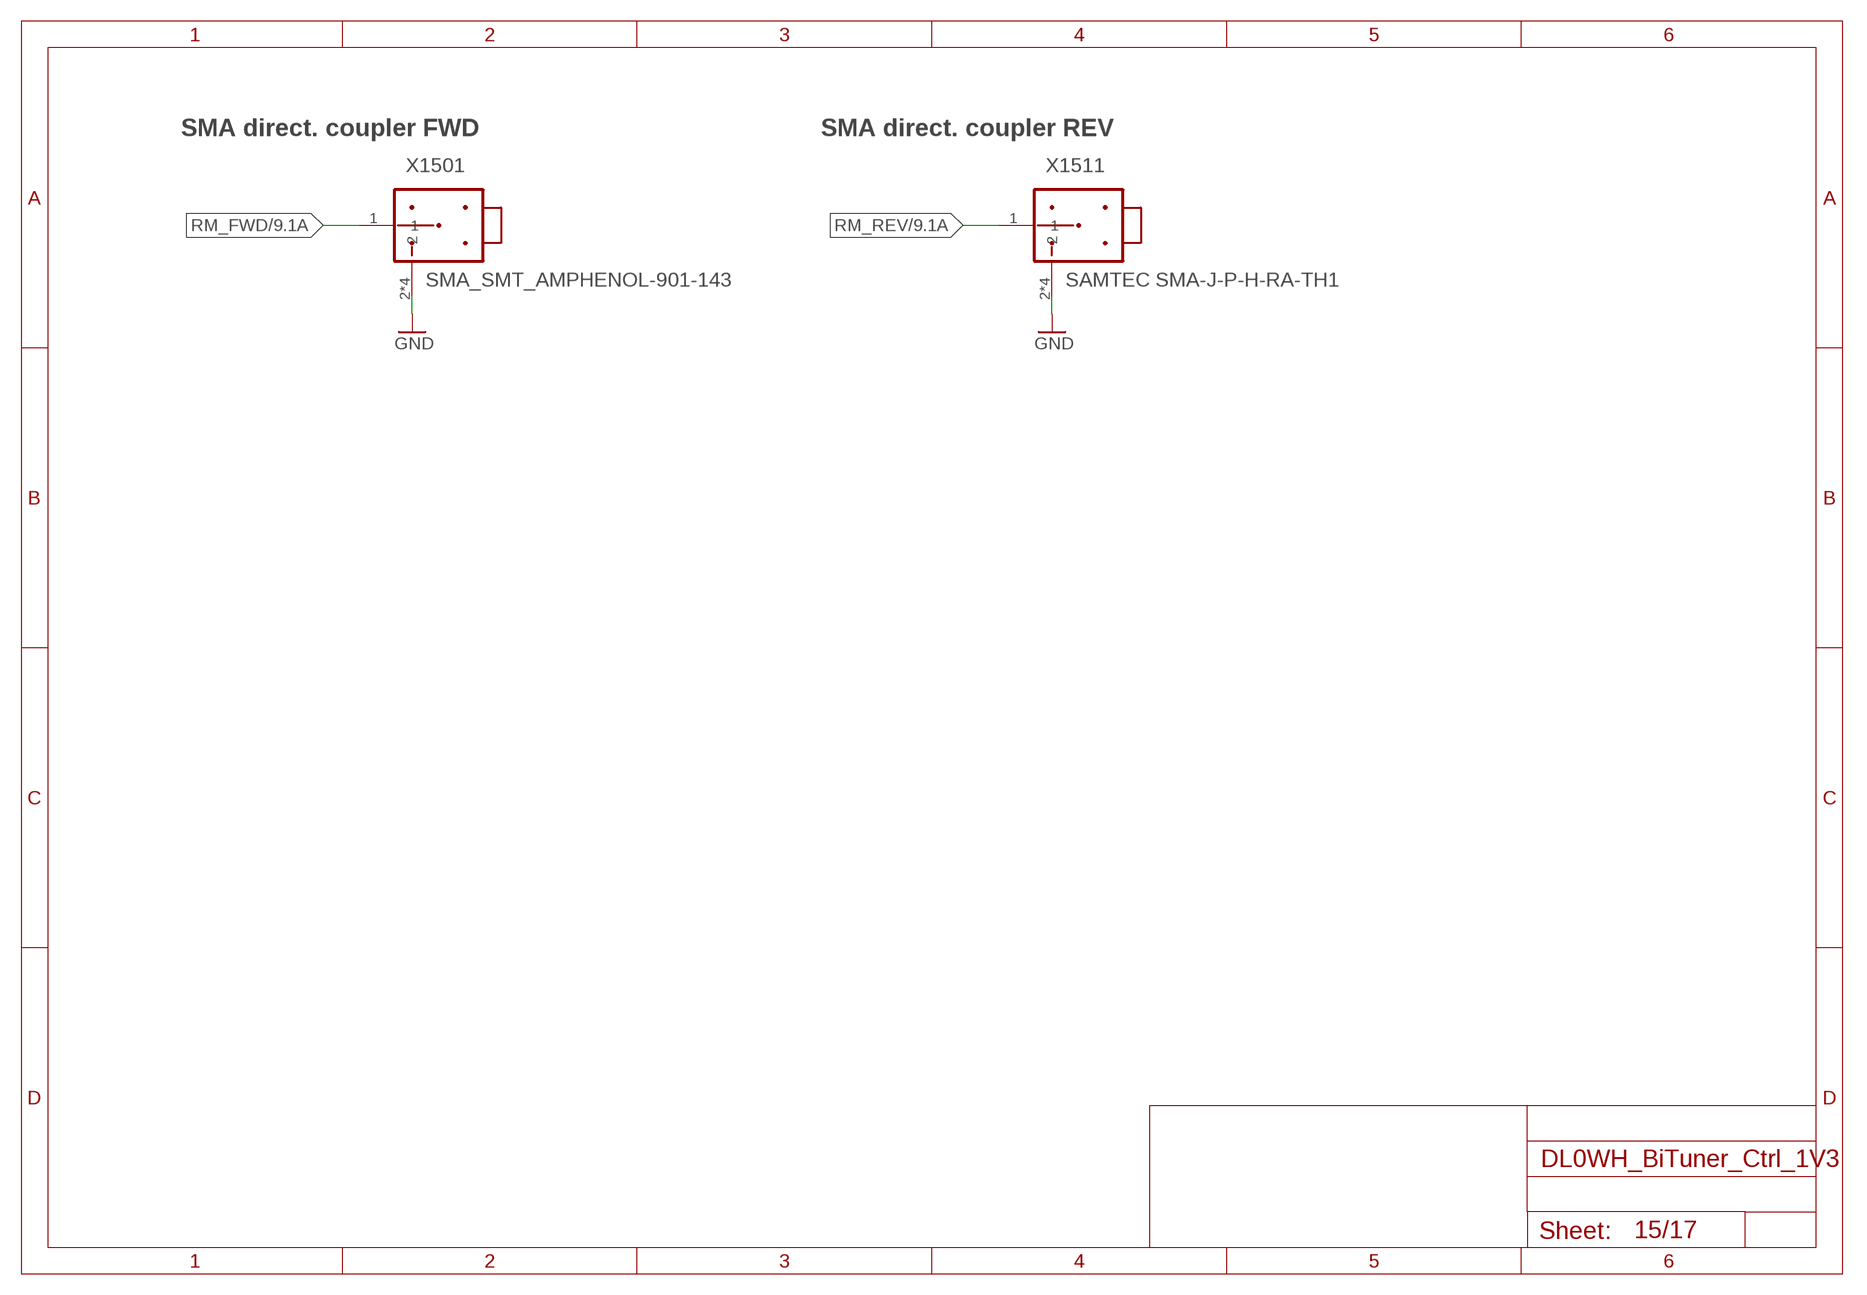
[diagram p14: schematic, sheet 15]
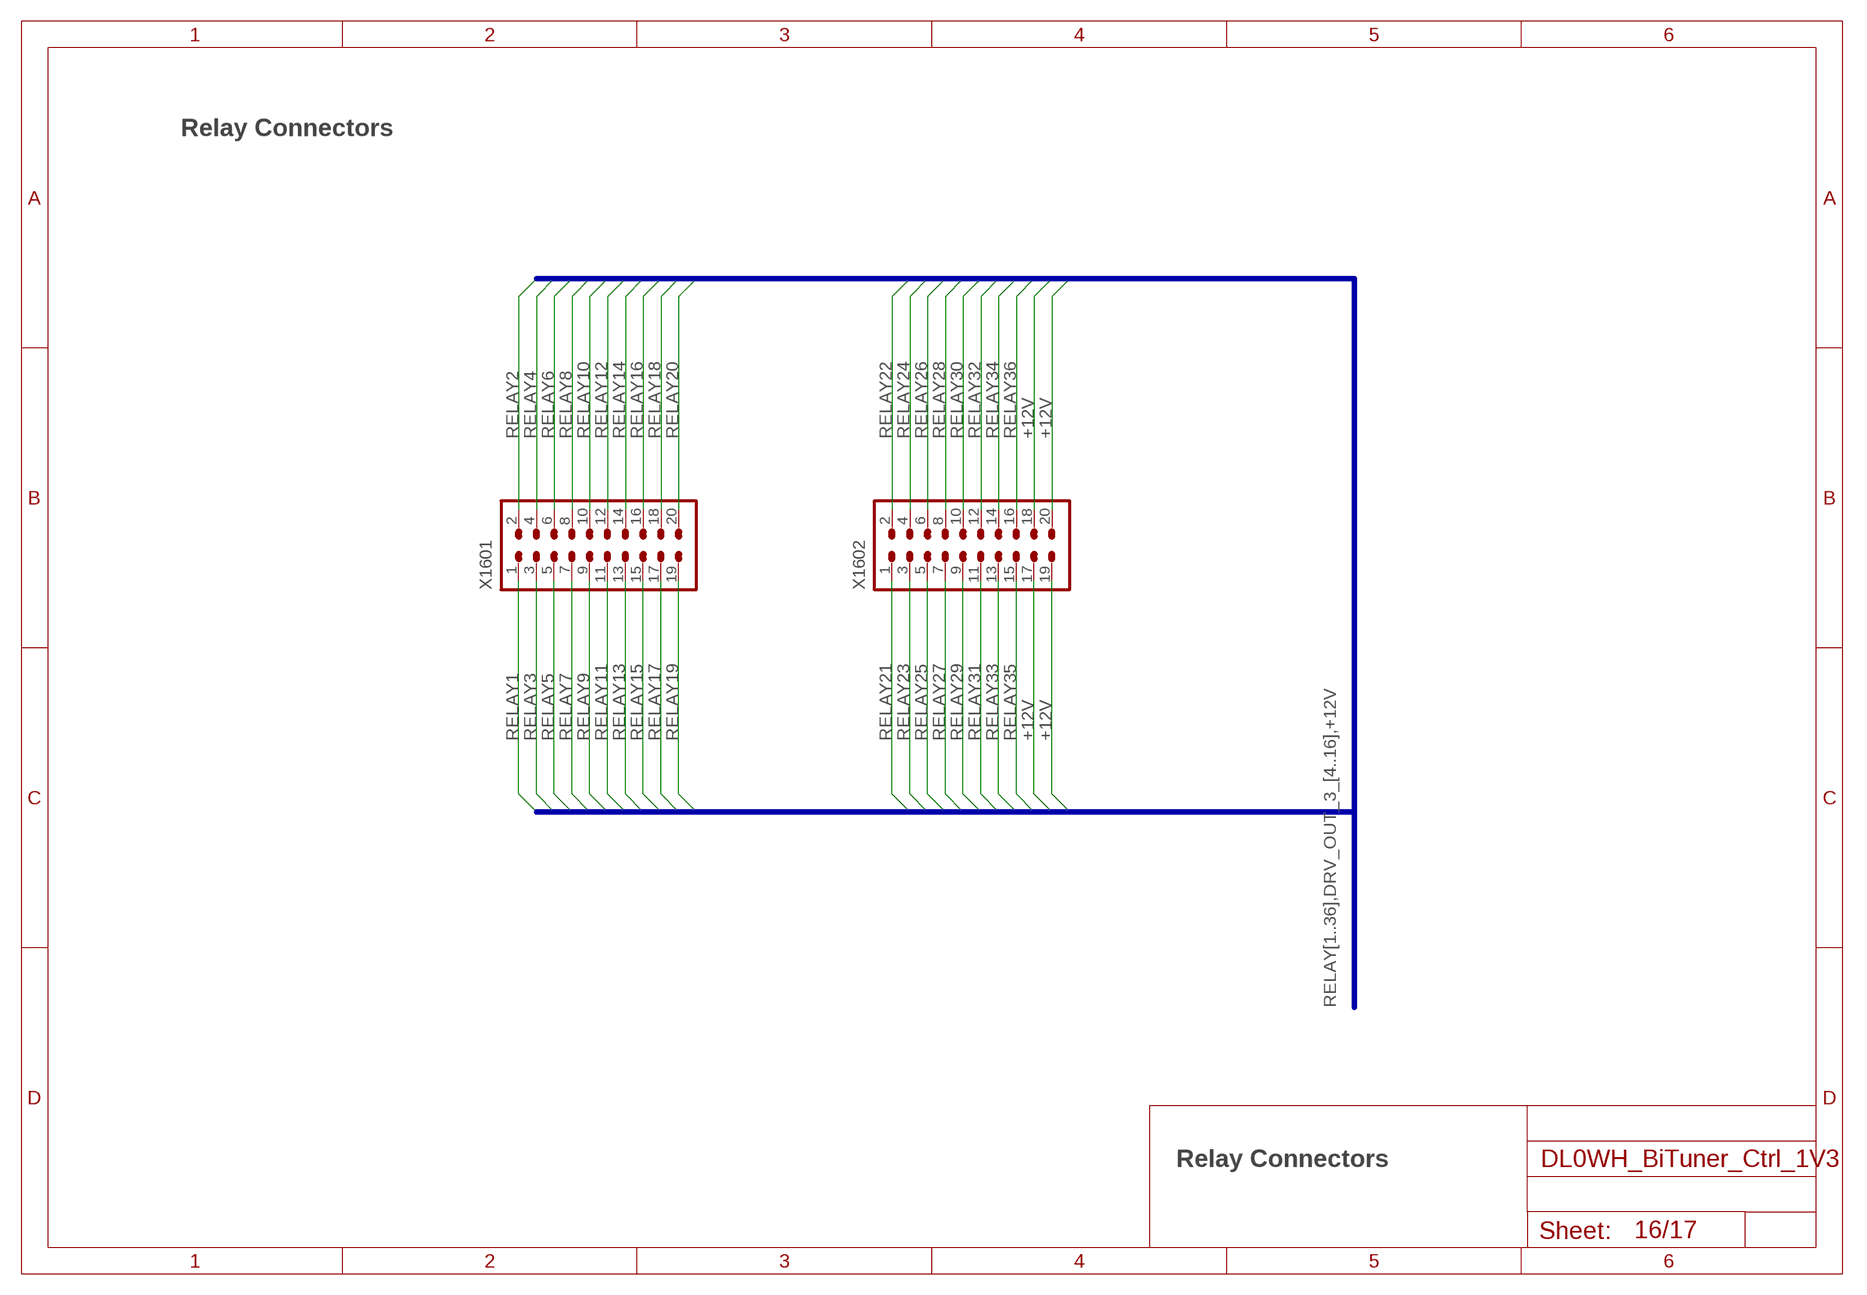
[diagram p15: schematic, sheet 16]
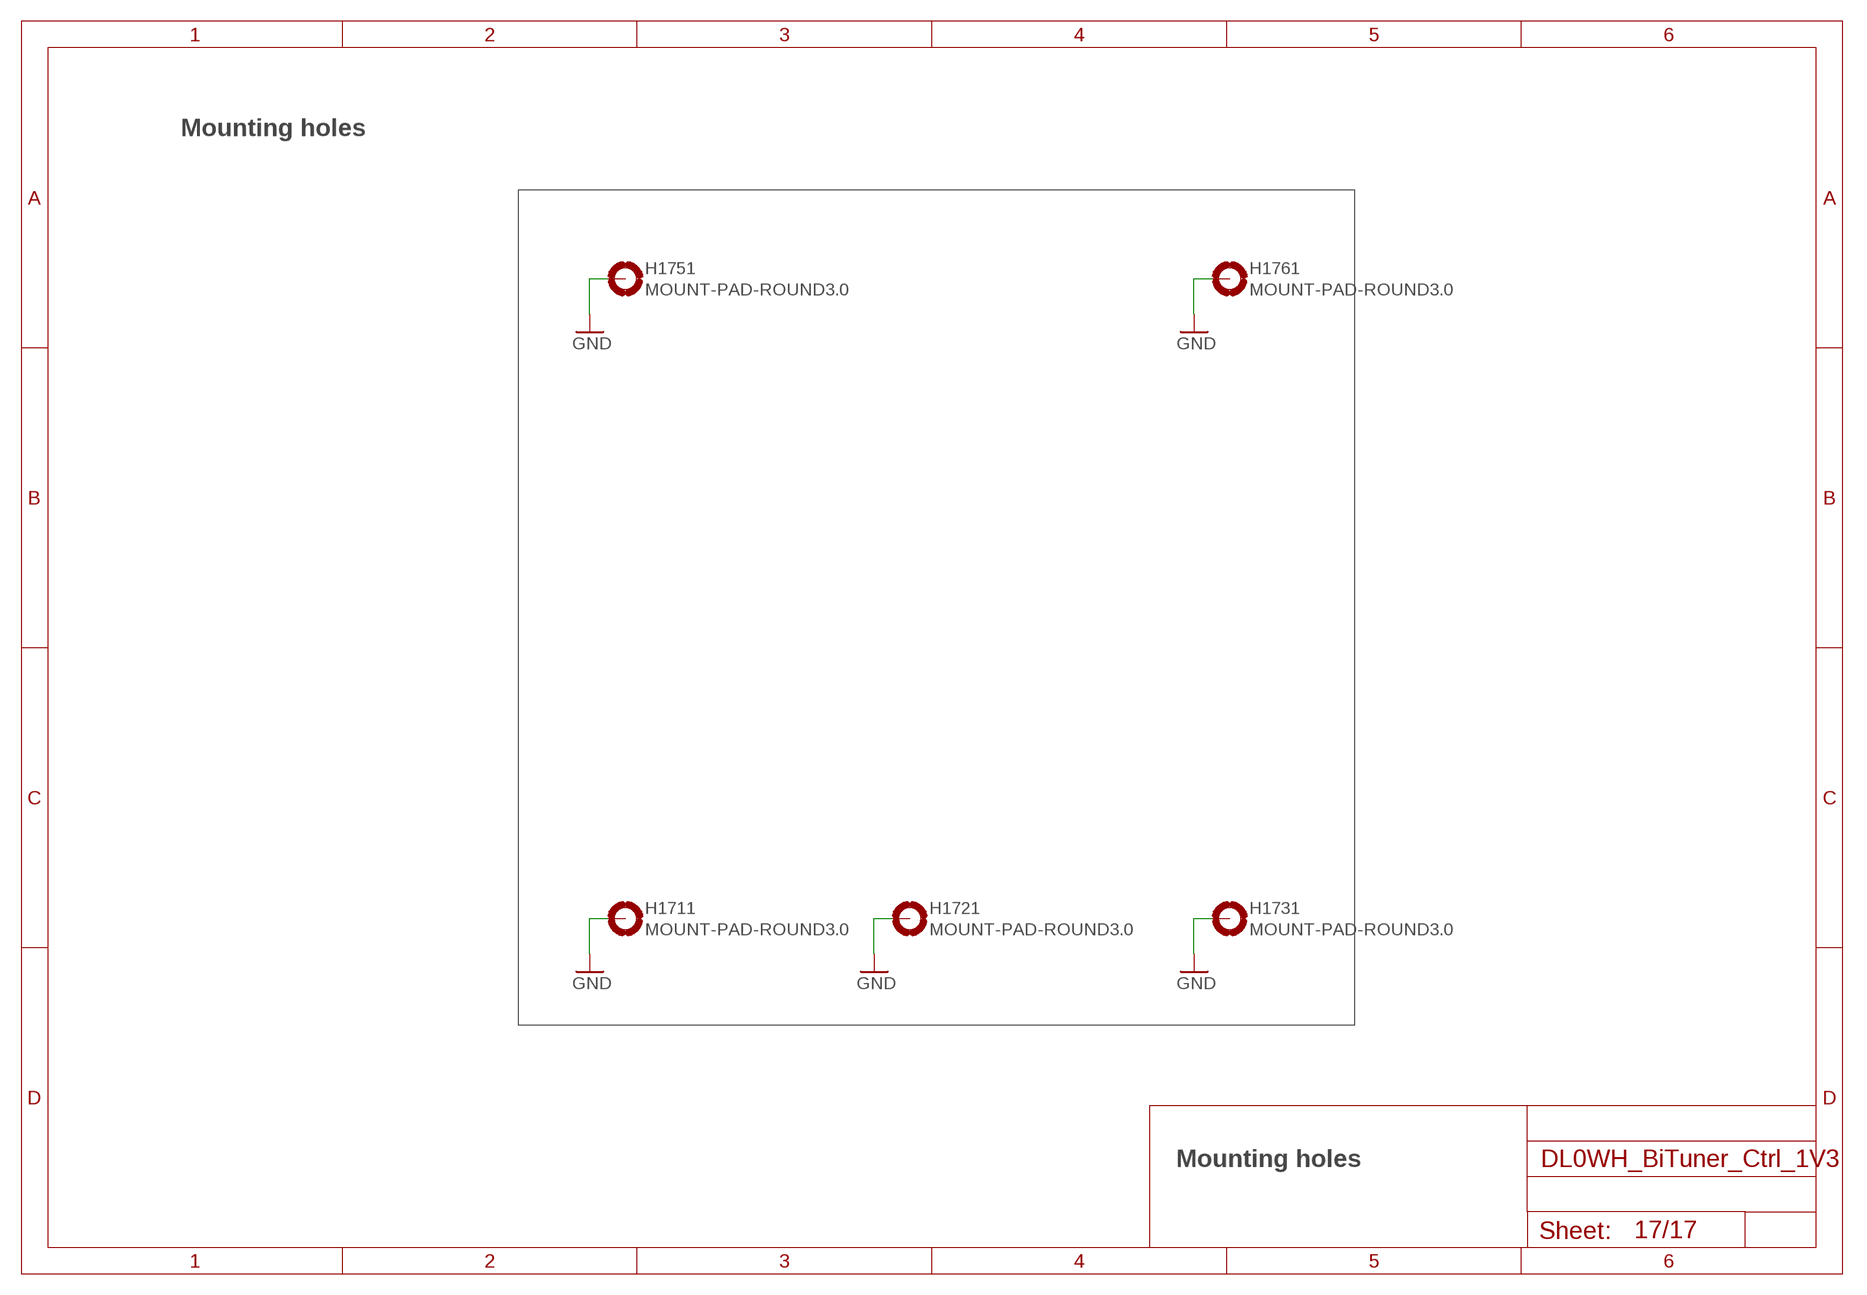
[diagram p16: schematic, sheet 17]

(export (version "E")
  (design (tool "Eeschema 10.0.6"))
  (components
    (comp (ref "C0901")
      (value "1nF")
      (footprint "eagle-import:C0402")
      (libsource (lib "eagle-import") (part "C-EUC0402"))
    )
    (comp (ref "C0911")
      (value "1nF")
      (footprint "eagle-import:C0402")
      (libsource (lib "eagle-import") (part "C-EUC0402"))
    )
    (comp (ref "C0921")
      (value "100nF")
      (footprint "eagle-import:C0402")
      (libsource (lib "eagle-import") (part "C-EUC0402"))
    )
    (comp (ref "C0941")
      (value "22uF")
      (footprint "eagle-import:C0603")
      (libsource (lib "eagle-import") (part "C-EUC0603"))
    )
    (comp (ref "C0942")
      (value "2.2uF")
      (footprint "eagle-import:C0603")
      (libsource (lib "eagle-import") (part "C-EUC0603"))
    )
    (comp (ref "C0943")
      (value "22uF")
      (footprint "eagle-import:C0603")
      (libsource (lib "eagle-import") (part "C-EUC0603"))
    )
    (comp (ref "C0945")
      (value "1nF")
      (footprint "eagle-import:C0402")
      (libsource (lib "eagle-import") (part "C-EUC0402"))
    )
    (comp (ref "C0951")
      (value "100nF")
      (footprint "eagle-import:C0402")
      (libsource (lib "eagle-import") (part "C-EUC0402"))
    )
    (comp (ref "C0952")
      (value "100nF")
      (footprint "eagle-import:C0402")
      (libsource (lib "eagle-import") (part "C-EUC0402"))
    )
    (comp (ref "C0962")
      (value "100nF")
      (footprint "eagle-import:C0402")
      (libsource (lib "eagle-import") (part "C-EUC0402"))
    )
    (comp (ref "C0963")
      (value "100pF")
      (footprint "eagle-import:C0402")
      (libsource (lib "eagle-import") (part "C-EUC0402"))
    )
    (comp (ref "D0942")
      (value "CRS08")
      (footprint "eagle-import:SOD80C")
      (libsource (lib "eagle-import") (part "CRS08"))
    )
    (comp (ref "D0951")
      (value "CMAD6001")
      (footprint "eagle-import:SOD923")
      (libsource (lib "eagle-import") (part "D_SOD923"))
    )
    (comp (ref "D0971")
      (value "CMAD6001")
      (footprint "eagle-import:SOD923")
      (libsource (lib "eagle-import") (part "D_SOD923"))
    )
    (comp (ref "L0901")
      (value "10uH")
      (footprint "eagle-import:L0603")
      (libsource (lib "eagle-import") (part "L-EUL0603"))
    )
    (comp (ref "L0911")
      (value "10uH")
      (footprint "eagle-import:L0603")
      (libsource (lib "eagle-import") (part "L-EUL0603"))
    )
    (comp (ref "L0941")
      (value "20uH")
      (footprint "eagle-import:L1812")
      (libsource (lib "eagle-import") (part "L-EUL1812"))
    )
    (comp (ref "L0943")
      (value "20uH")
      (footprint "eagle-import:L1812")
      (libsource (lib "eagle-import") (part "L-EUL1812"))
    )
    (comp (ref "R0901")
      (value "2kR")
      (footprint "eagle-import:R0402")
      (libsource (lib "eagle-import") (part "R-EU_R0402"))
    )
    (comp (ref "R0902")
      (value "1kR")
      (footprint "eagle-import:R0402")
      (libsource (lib "eagle-import") (part "R-EU_R0402"))
    )
    (comp (ref "R0903")
      (value "15kR")
      (footprint "eagle-import:R0402")
      (libsource (lib "eagle-import") (part "R-EU_R0402"))
    )
    (comp (ref "R0904")
      (value "150kR")
      (footprint "eagle-import:R0402")
      (libsource (lib "eagle-import") (part "R-EU_R0402"))
    )
    (comp (ref "R0911")
      (value "2kR")
      (footprint "eagle-import:R0402")
      (libsource (lib "eagle-import") (part "R-EU_R0402"))
    )
    (comp (ref "R0912")
      (value "1kR")
      (footprint "eagle-import:R0402")
      (libsource (lib "eagle-import") (part "R-EU_R0402"))
    )
    (comp (ref "R0913")
      (value "15kR")
      (footprint "eagle-import:R0402")
      (libsource (lib "eagle-import") (part "R-EU_R0402"))
    )
    (comp (ref "R0914")
      (value "150kR")
      (footprint "eagle-import:R0402")
      (libsource (lib "eagle-import") (part "R-EU_R0402"))
    )
    (comp (ref "R0921")
      (value "47R")
      (footprint "eagle-import:R0402")
      (libsource (lib "eagle-import") (part "R-EU_R0402"))
    )
    (comp (ref "R0922")
      (value "47R")
      (footprint "eagle-import:R0402")
      (libsource (lib "eagle-import") (part "R-EU_R0402"))
    )
    (comp (ref "R0923")
      (value "2MR")
      (footprint "eagle-import:R0402")
      (libsource (lib "eagle-import") (part "R-EU_R0402"))
    )
    (comp (ref "R0945")
      (value "8.2kR")
      (footprint "eagle-import:R0402")
      (libsource (lib "eagle-import") (part "R-EU_R0402"))
    )
    (comp (ref "R0946")
      (value "33kR")
      (footprint "eagle-import:R0402")
      (libsource (lib "eagle-import") (part "R-EU_R0402"))
    )
    (comp (ref "R0961")
      (value "1kR")
      (footprint "eagle-import:R0402")
      (libsource (lib "eagle-import") (part "R-EU_R0402"))
    )
    (comp (ref "R0962")
      (value "1kR")
      (footprint "eagle-import:R0402")
      (libsource (lib "eagle-import") (part "R-EU_R0402"))
    )
    (comp (ref "R0963")
      (value "20kR")
      (footprint "eagle-import:R0402")
      (libsource (lib "eagle-import") (part "R-EU_R0402"))
    )
    (comp (ref "R0971")
      (value "10kR")
      (footprint "eagle-import:R0402")
      (libsource (lib "eagle-import") (part "R-EU_R0402"))
    )
    (comp (ref "R0972")
      (value "1kR")
      (footprint "eagle-import:R0402")
      (libsource (lib "eagle-import") (part "R-EU_R0402"))
    )
    (comp (ref "U0921")
      (value "TS5A23166")
      (footprint "eagle-import:R-PDSO-G8")
      (libsource (lib "eagle-import") (part "TS5A23166"))
    )
    (comp (ref "U0941")
      (value "LM2611")
      (footprint "eagle-import:SOT95P280X145-5N")
      (libsource (lib "eagle-import") (part "LM2611"))
    )
    (comp (ref "U0951")
      (value "OPA354")
      (footprint "eagle-import:SOT-23-5")
      (fields (field (name "MPN") "OPA354AIDBVT"))
      (libsource (lib "eagle-import") (part "OPA354"))
    )
    (comp (ref "U0961")
      (value "OPA354")
      (footprint "eagle-import:SOT-23-5")
      (fields (field (name "MPN") "OPA354AIDBVT"))
      (libsource (lib "eagle-import") (part "OPA354"))
    )
    (comp (ref "U0962")
      (value "MCP4661-103E-MS")
      (footprint "eagle-import:TSSOP14")
      (libsource (lib "eagle-import") (part "MCP4661-104E-MS"))
    )
    (comp (ref "C1301")
      (value "22uF")
      (footprint "eagle-import:C0603")
      (libsource (lib "eagle-import") (part "C-EUC0603"))
    )
    (comp (ref "C1311")
      (value "22uF")
      (footprint "eagle-import:C0603")
      (libsource (lib "eagle-import") (part "C-EUC0603"))
    )
    (comp (ref "L1311")
      (value "10uH")
      (footprint "eagle-import:L_4.50MM_X_3.20MM")
      (libsource (lib "eagle-import") (part "L-EU4.50X3.20MM"))
    )
    (comp (ref "R1301")
      (value "100kR")
      (footprint "eagle-import:R0402")
      (libsource (lib "eagle-import") (part "R-EU_R0402"))
    )
    (comp (ref "R1302")
      (value "220kR")
      (footprint "eagle-import:R0402")
      (libsource (lib "eagle-import") (part "R-EU_R0402"))
    )
    (comp (ref "R1321")
      (value "1MR")
      (footprint "eagle-import:R0402")
      (libsource (lib "eagle-import") (part "R-EU_R0402"))
    )
    (comp (ref "R1322")
      (value "1MR")
      (footprint "eagle-import:R0402")
      (libsource (lib "eagle-import") (part "R-EU_R0402"))
    )
    (comp (ref "U1301")
      (value "TPS62056")
      (footprint "eagle-import:S-PDSO-G10")
      (libsource (lib "eagle-import") (part "TPS62051"))
    )
    (comp (ref "U0101")
      (value "STM32L476RGT6_64PIN_LDO")
      (footprint "eagle-import:LQFP64")
      (libsource (lib "eagle-import") (part "STM32L476RXT_64PIN_LDO"))
    )
    (comp (ref "H1711")
      (value "MOUNT-PAD-ROUND3.0")
      (footprint "eagle-import:3,0-PAD")
      (libsource (lib "eagle-import") (part "MOUNT-PAD-ROUND3.0"))
    )
    (comp (ref "H1721")
      (value "MOUNT-PAD-ROUND3.0")
      (footprint "eagle-import:3,0-PAD")
      (libsource (lib "eagle-import") (part "MOUNT-PAD-ROUND3.0"))
    )
    (comp (ref "H1731")
      (value "MOUNT-PAD-ROUND3.0")
      (footprint "eagle-import:3,0-PAD")
      (libsource (lib "eagle-import") (part "MOUNT-PAD-ROUND3.0"))
    )
    (comp (ref "H1751")
      (value "MOUNT-PAD-ROUND3.0")
      (footprint "eagle-import:3,0-PAD")
      (libsource (lib "eagle-import") (part "MOUNT-PAD-ROUND3.0"))
    )
    (comp (ref "H1761")
      (value "MOUNT-PAD-ROUND3.0")
      (footprint "eagle-import:3,0-PAD")
      (libsource (lib "eagle-import") (part "MOUNT-PAD-ROUND3.0"))
    )
    (comp (ref "C0801")
      (value "100nF")
      (footprint "eagle-import:C0402")
      (libsource (lib "eagle-import") (part "C-EUC0402"))
    )
    (comp (ref "C0802")
      (value "100nF")
      (footprint "eagle-import:C0402")
      (libsource (lib "eagle-import") (part "C-EUC0402"))
    )
    (comp (ref "C0803")
      (value "22uF")
      (footprint "eagle-import:C0603")
      (libsource (lib "eagle-import") (part "C-EUC0603"))
    )
    (comp (ref "R0811")
      (value "47R")
      (footprint "eagle-import:R0402")
      (libsource (lib "eagle-import") (part "R-EU_R0402"))
    )
    (comp (ref "R0824")
      (value "47R")
      (footprint "eagle-import:R0402")
      (libsource (lib "eagle-import") (part "R-EU_R0402"))
    )
    (comp (ref "U0801")
      (value "MC33996")
      (footprint "eagle-import:SOICW32")
      (libsource (lib "eagle-import") (part "MC33996"))
    )
    (comp (ref "C1403")
      (value "1nF")
      (footprint "eagle-import:C0402")
      (libsource (lib "eagle-import") (part "C-EUC0402"))
    )
    (comp (ref "PF1411")
      (value "1.1A/2.2A")
      (footprint "eagle-import:M1206")
      (libsource (lib "eagle-import") (part "rcl_R-EU_M1206"))
    )
    (comp (ref "R1402")
      (value "330kR")
      (footprint "eagle-import:R0402")
      (libsource (lib "eagle-import") (part "R-EU_R0402"))
    )
    (comp (ref "X1401")
      (value "MOLEX 105017-0001")
      (footprint "eagle-import:USB-B-MICRO-SMD_MOLEX-105017-0001")
      (libsource (lib "eagle-import") (part "USB_MICRO-B_MOLEX"))
    )
    (comp (ref "C0401")
      (value "100nF")
      (footprint "eagle-import:C0402")
      (libsource (lib "eagle-import") (part "C-EUC0402"))
    )
    (comp (ref "C0402")
      (value "100nF")
      (footprint "eagle-import:C0402")
      (libsource (lib "eagle-import") (part "C-EUC0402"))
    )
    (comp (ref "C0403")
      (value "100nF")
      (footprint "eagle-import:C0402")
      (libsource (lib "eagle-import") (part "C-EUC0402"))
    )
    (comp (ref "C0410")
      (value "4.7uF")
      (footprint "eagle-import:C0603")
      (libsource (lib "eagle-import") (part "C-EUC0603"))
    )
    (comp (ref "C0412")
      (value "10nF")
      (footprint "eagle-import:C0402")
      (libsource (lib "eagle-import") (part "C-EUC0402"))
    )
    (comp (ref "C0413")
      (value "1uF")
      (footprint "eagle-import:C0402")
      (libsource (lib "eagle-import") (part "C-EUC0402"))
    )
    (comp (ref "C0451")
      (value "47uF")
      (footprint "eagle-import:C0805")
      (libsource (lib "eagle-import") (part "C-EUC0805"))
    )
    (comp (ref "L0411")
      (value "10uH")
      (footprint "eagle-import:L0603")
      (libsource (lib "eagle-import") (part "L-EUL0603"))
    )
    (comp (ref "R0401")
      (value "0R")
      (footprint "eagle-import:R0402")
      (libsource (lib "eagle-import") (part "R-EU_R0402"))
    )
    (comp (ref "R0441")
      (value "0R")
      (footprint "eagle-import:R0402")
      (libsource (lib "eagle-import") (part "R-EU_R0402"))
    )
    (comp (ref "TP_VBAT")
      (value "PTR1B1,27")
      (footprint "eagle-import:B1,27")
      (libsource (lib "eagle-import") (part "PTR1B1,27"))
    )
    (comp (ref "C0601")
      (value "100nF")
      (footprint "eagle-import:C0402")
      (libsource (lib "eagle-import") (part "C-EUC0402"))
    )
    (comp (ref "C0602")
      (value "100nF")
      (footprint "eagle-import:C0402")
      (libsource (lib "eagle-import") (part "C-EUC0402"))
    )
    (comp (ref "C0603")
      (value "22uF")
      (footprint "eagle-import:C0603")
      (libsource (lib "eagle-import") (part "C-EUC0603"))
    )
    (comp (ref "R0611")
      (value "47R")
      (footprint "eagle-import:R0402")
      (libsource (lib "eagle-import") (part "R-EU_R0402"))
    )
    (comp (ref "R0621")
      (value "47R")
      (footprint "eagle-import:R0402")
      (libsource (lib "eagle-import") (part "R-EU_R0402"))
    )
    (comp (ref "R0622")
      (value "0R")
      (footprint "eagle-import:R0402")
      (libsource (lib "eagle-import") (part "R-EU_R0402"))
    )
    (comp (ref "R0623")
      (value "47R")
      (footprint "eagle-import:R0402")
      (libsource (lib "eagle-import") (part "R-EU_R0402"))
    )
    (comp (ref "R0624")
      (value "47R")
      (footprint "eagle-import:R0402")
      (libsource (lib "eagle-import") (part "R-EU_R0402"))
    )
    (comp (ref "R0625")
      (value "47R")
      (footprint "eagle-import:R0402")
      (libsource (lib "eagle-import") (part "R-EU_R0402"))
    )
    (comp (ref "R0626")
      (value "47R")
      (footprint "eagle-import:R0402")
      (libsource (lib "eagle-import") (part "R-EU_R0402"))
    )
    (comp (ref "U0601")
      (value "MC33996")
      (footprint "eagle-import:SOICW32")
      (libsource (lib "eagle-import") (part "MC33996"))
    )
    (comp (ref "X1501")
      (value "SMA_SMT_AMPHENOL-901-143")
      (footprint "eagle-import:SMA_SMT_AMPHENOL_901-143")
      (fields (field (name "MPN") "901-143"))
      (libsource (lib "eagle-import") (part "SMA_SMT_AMPHENOL-901-143"))
    )
    (comp (ref "X1511")
      (value "SAMTEC SMA-J-P-H-RA-TH1")
      (footprint "eagle-import:SMA_SMT_AMPHENOL_901-143")
      (fields (field (name "MPN") "901-143"))
      (libsource (lib "eagle-import") (part "SMA_SMT_AMPHENOL-901-143"))
    )
    (comp (ref "C1001")
      (value "1uF")
      (footprint "eagle-import:C0402")
      (libsource (lib "eagle-import") (part "C-EUC0402"))
    )
    (comp (ref "C1002")
      (value "1uF")
      (footprint "eagle-import:C0402")
      (libsource (lib "eagle-import") (part "C-EUC0402"))
    )
    (comp (ref "C1003")
      (value "1uF")
      (footprint "eagle-import:C0402")
      (libsource (lib "eagle-import") (part "C-EUC0402"))
    )
    (comp (ref "C1004")
      (value "1uF")
      (footprint "eagle-import:C0402")
      (libsource (lib "eagle-import") (part "C-EUC0402"))
    )
    (comp (ref "C1005")
      (value "1uF")
      (footprint "eagle-import:C0402")
      (libsource (lib "eagle-import") (part "C-EUC0402"))
    )
    (comp (ref "C1051")
      (value "10nF")
      (footprint "eagle-import:C0402")
      (libsource (lib "eagle-import") (part "C-EUC0402"))
    )
    (comp (ref "C1052")
      (value "10nF")
      (footprint "eagle-import:C0402")
      (libsource (lib "eagle-import") (part "C-EUC0402"))
    )
    (comp (ref "C1053")
      (value "10nF")
      (footprint "eagle-import:C0402")
      (libsource (lib "eagle-import") (part "C-EUC0402"))
    )
    (comp (ref "C1054")
      (value "10nF")
      (footprint "eagle-import:C0402")
      (libsource (lib "eagle-import") (part "C-EUC0402"))
    )
    (comp (ref "R1001")
      (value "47R")
      (footprint "eagle-import:R0402")
      (libsource (lib "eagle-import") (part "R-EU_R0402"))
    )
    (comp (ref "R1002")
      (value "47R")
      (footprint "eagle-import:R0402")
      (libsource (lib "eagle-import") (part "R-EU_R0402"))
    )
    (comp (ref "R1003")
      (value "47R")
      (footprint "eagle-import:R0402")
      (libsource (lib "eagle-import") (part "R-EU_R0402"))
    )
    (comp (ref "R1004")
      (value "47R")
      (footprint "eagle-import:R0402")
      (libsource (lib "eagle-import") (part "R-EU_R0402"))
    )
    (comp (ref "U1001")
      (value "MAX232_SOIC16")
      (footprint "eagle-import:SOIC16N")
      (fields (field (name "MF") "MAXIM") (field (name "MPN") "MAX232ECDR"))
      (libsource (lib "eagle-import") (part "MAX232_SOIC16"))
    )
    (comp (ref "X1051")
      (value "WIRE-TO-BOARD_5MM08_1X02")
      (footprint "eagle-import:WIRE-TO-BOARD_5MM08_1X02")
      (libsource (lib "eagle-import") (part "WIRE-TO-BOARD_5MM08_1X02"))
    )
    (comp (ref "X1052")
      (value "WIRE-TO-BOARD_5MM08_1X02")
      (footprint "eagle-import:WIRE-TO-BOARD_5MM08_1X02")
      (libsource (lib "eagle-import") (part "WIRE-TO-BOARD_5MM08_1X02"))
    )
    (comp (ref "X1053")
      (value "WIRE-TO-BOARD_5MM08_1X02")
      (footprint "eagle-import:WIRE-TO-BOARD_5MM08_1X02")
      (libsource (lib "eagle-import") (part "WIRE-TO-BOARD_5MM08_1X02"))
    )
    (comp (ref "C0701")
      (value "100nF")
      (footprint "eagle-import:C0402")
      (libsource (lib "eagle-import") (part "C-EUC0402"))
    )
    (comp (ref "C0702")
      (value "100nF")
      (footprint "eagle-import:C0402")
      (libsource (lib "eagle-import") (part "C-EUC0402"))
    )
    (comp (ref "C0703")
      (value "22uF")
      (footprint "eagle-import:C0603")
      (libsource (lib "eagle-import") (part "C-EUC0603"))
    )
    (comp (ref "R0711")
      (value "47R")
      (footprint "eagle-import:R0402")
      (libsource (lib "eagle-import") (part "R-EU_R0402"))
    )
    (comp (ref "R0724")
      (value "47R")
      (footprint "eagle-import:R0402")
      (libsource (lib "eagle-import") (part "R-EU_R0402"))
    )
    (comp (ref "U0701")
      (value "MC33996")
      (footprint "eagle-import:SOICW32")
      (libsource (lib "eagle-import") (part "MC33996"))
    )
    (comp (ref "C1101")
      (value "1uF")
      (footprint "eagle-import:C0402")
      (libsource (lib "eagle-import") (part "C-EUC0402"))
    )
    (comp (ref "C1102")
      (value "1uF")
      (footprint "eagle-import:C0402")
      (libsource (lib "eagle-import") (part "C-EUC0402"))
    )
    (comp (ref "C1103")
      (value "1uF")
      (footprint "eagle-import:C0402")
      (libsource (lib "eagle-import") (part "C-EUC0402"))
    )
    (comp (ref "C1104")
      (value "1uF")
      (footprint "eagle-import:C0402")
      (libsource (lib "eagle-import") (part "C-EUC0402"))
    )
    (comp (ref "C1105")
      (value "1uF")
      (footprint "eagle-import:C0402")
      (libsource (lib "eagle-import") (part "C-EUC0402"))
    )
    (comp (ref "C1151")
      (value "10nF")
      (footprint "eagle-import:C0402")
      (libsource (lib "eagle-import") (part "C-EUC0402"))
    )
    (comp (ref "C1152")
      (value "10nF")
      (footprint "eagle-import:C0402")
      (libsource (lib "eagle-import") (part "C-EUC0402"))
    )
    (comp (ref "C1153")
      (value "10nF")
      (footprint "eagle-import:C0402")
      (libsource (lib "eagle-import") (part "C-EUC0402"))
    )
    (comp (ref "C1154")
      (value "10nF")
      (footprint "eagle-import:C0402")
      (libsource (lib "eagle-import") (part "C-EUC0402"))
    )
    (comp (ref "R1101")
      (value "47R")
      (footprint "eagle-import:R0402")
      (libsource (lib "eagle-import") (part "R-EU_R0402"))
    )
    (comp (ref "R1102")
      (value "47R")
      (footprint "eagle-import:R0402")
      (libsource (lib "eagle-import") (part "R-EU_R0402"))
    )
    (comp (ref "R1103")
      (value "47R")
      (footprint "eagle-import:R0402")
      (libsource (lib "eagle-import") (part "R-EU_R0402"))
    )
    (comp (ref "R1104")
      (value "47R")
      (footprint "eagle-import:R0402")
      (libsource (lib "eagle-import") (part "R-EU_R0402"))
    )
    (comp (ref "U1101")
      (value "MAX232_SOIC16")
      (footprint "eagle-import:SOIC16N")
      (fields (field (name "MF") "MAXIM") (field (name "MPN") "MAX232ECDR"))
      (libsource (lib "eagle-import") (part "MAX232_SOIC16"))
    )
    (comp (ref "X1151")
      (value "WIRE-TO-BOARD_5MM08_1X02")
      (footprint "eagle-import:WIRE-TO-BOARD_5MM08_1X02")
      (libsource (lib "eagle-import") (part "WIRE-TO-BOARD_5MM08_1X02"))
    )
    (comp (ref "X1152")
      (value "WIRE-TO-BOARD_5MM08_1X02")
      (footprint "eagle-import:WIRE-TO-BOARD_5MM08_1X02")
      (libsource (lib "eagle-import") (part "WIRE-TO-BOARD_5MM08_1X02"))
    )
    (comp (ref "X1153")
      (value "WIRE-TO-BOARD_5MM08_1X02")
      (footprint "eagle-import:WIRE-TO-BOARD_5MM08_1X02")
      (libsource (lib "eagle-import") (part "WIRE-TO-BOARD_5MM08_1X02"))
    )
    (comp (ref "R0511")
      (value "1kR")
      (footprint "eagle-import:R0402")
      (libsource (lib "eagle-import") (part "R-EU_R0402"))
    )
    (comp (ref "R0512")
      (value "1kR")
      (footprint "eagle-import:R0402")
      (libsource (lib "eagle-import") (part "R-EU_R0402"))
    )
    (comp (ref "X0501")
      (value "HEADER-2X2")
      (footprint "eagle-import:2X02")
      (libsource (lib "eagle-import") (part "HEADER-2X2"))
    )
    (comp (ref "C1201")
      (value "10uF")
      (footprint "eagle-import:C0603")
      (libsource (lib "eagle-import") (part "C-EUC0603"))
    )
    (comp (ref "C1202")
      (value "10uF")
      (footprint "eagle-import:C0603")
      (libsource (lib "eagle-import") (part "C-EUC0603"))
    )
    (comp (ref "C1203")
      (value "10uF")
      (footprint "eagle-import:C0603")
      (libsource (lib "eagle-import") (part "C-EUC0603"))
    )
    (comp (ref "C1204")
      (value "10nF")
      (footprint "eagle-import:C0402")
      (libsource (lib "eagle-import") (part "C-EUC0402"))
    )
    (comp (ref "C1205")
      (value "3.3uF")
      (footprint "eagle-import:C0603")
      (libsource (lib "eagle-import") (part "C-EUC0603"))
    )
    (comp (ref "C1211")
      (value "0.47uF")
      (footprint "eagle-import:C0402")
      (libsource (lib "eagle-import") (part "C-EUC0402"))
    )
    (comp (ref "C1212")
      (value "100nF")
      (footprint "eagle-import:C0402")
      (libsource (lib "eagle-import") (part "C-EUC0402"))
    )
    (comp (ref "C1221")
      (value "22uF")
      (footprint "eagle-import:C0603")
      (libsource (lib "eagle-import") (part "C-EUC0603"))
    )
    (comp (ref "C1222")
      (value "22uF")
      (footprint "eagle-import:C0603")
      (libsource (lib "eagle-import") (part "C-EUC0603"))
    )
    (comp (ref "C1223")
      (value "22uF")
      (footprint "eagle-import:C0603")
      (libsource (lib "eagle-import") (part "C-EUC0603"))
    )
    (comp (ref "D1221")
      (value "CRS08")
      (footprint "eagle-import:SOD80C")
      (libsource (lib "eagle-import") (part "CRS08"))
    )
    (comp (ref "L1211")
      (value "2.2uH")
      (footprint "eagle-import:L_6.00MM_X_6.00MM")
      (libsource (lib "eagle-import") (part "L-EU6.00X6.00MM"))
    )
    (comp (ref "R1211")
      (value "3R")
      (footprint "eagle-import:R0402")
      (libsource (lib "eagle-import") (part "R-EU_R0402"))
    )
    (comp (ref "U1201")
      (value "LM53603-Q1")
      (footprint "eagle-import:HTSSOP16")
      (libsource (lib "eagle-import") (part "LM53603-Q1"))
    )
    (comp (ref "X1211")
      (value "WIRE-TO-BOARD_5MM08_1X02")
      (footprint "eagle-import:WIRE-TO-BOARD_5MM08_1X02")
      (libsource (lib "eagle-import") (part "WIRE-TO-BOARD_5MM08_1X02"))
    )
    (comp (ref "C0213")
      (value "100nF")
      (footprint "eagle-import:C0402")
      (libsource (lib "eagle-import") (part "C-EUC0402"))
    )
    (comp (ref "R0221")
      (value "33kR")
      (footprint "eagle-import:R0402")
      (libsource (lib "eagle-import") (part "R-EU_R0402"))
    )
    (comp (ref "R0231")
      (value "220kR")
      (footprint "eagle-import:R0402")
      (libsource (lib "eagle-import") (part "R-EU_R0402"))
    )
    (comp (ref "R0232")
      (value "220kR")
      (footprint "eagle-import:R0402")
      (libsource (lib "eagle-import") (part "R-EU_R0402"))
    )
    (comp (ref "S0212")
      (value "KSR223GLFG")
      (footprint "eagle-import:KSR223G_SMD_1POL")
      (libsource (lib "eagle-import") (part "KSR223G_SMD_1POL"))
    )
    (comp (ref "X0201")
      (value "FTSH-105-01-F-D-K")
      (footprint "eagle-import:2X05_1MM27_SHROUDED_CORTEX_JTAG_SWD")
      (libsource (lib "eagle-import") (part "2X05_1MM27_SHROUDED_CORTEX_JTAG_SWD{dblquote}"))
    )
    (comp (ref "X0222")
      (value "HEADER-1X2")
      (footprint "eagle-import:1X02")
      (libsource (lib "eagle-import") (part "HEADER-1X2"))
    )
    (comp (ref "C0311")
      (value "22pF")
      (footprint "eagle-import:C0402")
      (libsource (lib "eagle-import") (part "C-EUC0402"))
    )
    (comp (ref "C0331")
      (value "JR200")
      (footprint "eagle-import:3MM2_X_2MM5")
      (libsource (lib "eagle-import") (part "C-TRIMM3MM2_2MM5"))
    )
    (comp (ref "C0332")
      (value "18pF")
      (footprint "eagle-import:C0402")
      (libsource (lib "eagle-import") (part "C-EUC0402"))
    )
    (comp (ref "Q0321")
      (value "ABS07-32.768KHZ")
      (footprint "eagle-import:ABS07")
      (fields (field (name "MANUFACTURER") "ABS07-32.768KHZ-1-T"))
      (libsource (lib "eagle-import") (part "ABS07-32.768KHZ"))
    )
    (comp (ref "X1601")
      (value "2X10_2MM56_SOCKET")
      (footprint "eagle-import:2X10")
      (libsource (lib "eagle-import") (part "2X10_2MM56_SOCKET"))
    )
    (comp (ref "X1602")
      (value "2X10_2MM56_SOCKET")
      (footprint "eagle-import:2X10")
      (libsource (lib "eagle-import") (part "2X10_2MM56_SOCKET"))
    )
  )
  (nets
    (net (code "26") (name "+3V3") (class "Default")
      (node (ref "C0601") (pin "2") (pinfunction "2_2") (pintype "passive"))
      (node (ref "C0701") (pin "2") (pinfunction "2_2") (pintype "passive"))
      (node (ref "C0801") (pin "2") (pinfunction "2_2") (pintype "passive"))
      (node (ref "C0921") (pin "1") (pinfunction "1_1") (pintype "passive"))
      (node (ref "C0941") (pin "1") (pinfunction "1_1") (pintype "passive"))
      (node (ref "C0951") (pin "1") (pinfunction "1_1") (pintype "passive"))
      (node (ref "C0962") (pin "1") (pinfunction "1_1") (pintype "passive"))
      (node (ref "C1311") (pin "1") (pinfunction "1_1") (pintype "passive"))
      (node (ref "L0941") (pin "2") (pinfunction "2_2") (pintype "passive"))
      (node (ref "L1311") (pin "1") (pinfunction "1_1") (pintype "passive"))
      (node (ref "L1311") (pin "3") (pinfunction "1_3") (pintype "passive"))
      (node (ref "R0231") (pin "2") (pinfunction "2_2") (pintype "passive"))
      (node (ref "R0401") (pin "1") (pinfunction "1_1") (pintype "passive"))
      (node (ref "R0511") (pin "2") (pinfunction "2_2") (pintype "passive"))
      (node (ref "R0512") (pin "2") (pinfunction "2_2") (pintype "passive"))
      (node (ref "R0904") (pin "2") (pinfunction "2_2") (pintype "passive"))
      (node (ref "R0914") (pin "2") (pinfunction "2_2") (pintype "passive"))
      (node (ref "R0971") (pin "1") (pinfunction "1_1") (pintype "passive"))
      (node (ref "R1321") (pin "2") (pinfunction "2_2") (pintype "passive"))
      (node (ref "R1322") (pin "2") (pinfunction "2_2") (pintype "passive"))
      (node (ref "U0601") (pin "3") (pinfunction "SOPWR_3") (pintype "power_in"))
      (node (ref "U0701") (pin "3") (pinfunction "SOPWR_3") (pintype "power_in"))
      (node (ref "U0801") (pin "3") (pinfunction "SOPWR_3") (pintype "power_in"))
      (node (ref "U0921") (pin "8") (pinfunction "8_8") (pintype "power_in"))
      (node (ref "U0941") (pin "4") (pinfunction "~{SHDN}_4") (pintype "input"))
      (node (ref "U0941") (pin "5") (pinfunction "VIN_5") (pintype "power_in"))
      (node (ref "U0951") (pin "5") (pinfunction "V+_5") (pintype "power_in"))
      (node (ref "U0961") (pin "5") (pinfunction "V+_5") (pintype "power_in"))
      (node (ref "U0962") (pin "11") (pinfunction "~{WP}_11") (pintype "input"))
      (node (ref "U0962") (pin "14") (pinfunction "VDD_14") (pintype "power_in"))
      (node (ref "U0962") (pin "8") (pinfunction "P0A_8") (pintype "passive"))
      (node (ref "U1301") (pin "5") (pinfunction "FB_5") (pintype "passive"))
      (node (ref "X0201") (pin "1") (pinfunction "1_1") (pintype "passive"))
      (node (ref "X0222") (pin "1") (pinfunction "1_1") (pintype "passive"))
    )
    (net (code "27") (name "+5V") (class "Default")
      (node (ref "C1001") (pin "1") (pinfunction "1_1") (pintype "passive"))
      (node (ref "C1101") (pin "1") (pinfunction "1_1") (pintype "passive"))
      (node (ref "C1221") (pin "1") (pinfunction "1_1") (pintype "passive"))
      (node (ref "C1222") (pin "1") (pinfunction "1_1") (pintype "passive"))
      (node (ref "C1223") (pin "1") (pinfunction "1_1") (pintype "passive"))
      (node (ref "C1301") (pin "1") (pinfunction "1_1") (pintype "passive"))
      (node (ref "D1221") (pin "C") (pinfunction "C_C") (pintype "passive"))
      (node (ref "L1211") (pin "1") (pinfunction "1_1") (pintype "passive"))
      (node (ref "R1211") (pin "2") (pinfunction "2_2") (pintype "passive"))
      (node (ref "R1302") (pin "2") (pinfunction "2_2") (pintype "passive"))
      (node (ref "U1001") (pin "16") (pinfunction "VCC_16") (pintype "power_in"))
      (node (ref "U1101") (pin "16") (pinfunction "VCC_16") (pintype "power_in"))
      (node (ref "U1201") (pin "9") (pinfunction "FB_9") (pintype "passive"))
      (node (ref "U1301") (pin "1") (pinfunction "VIN_1") (pintype "power_in"))
      (node (ref "U1301") (pin "8") (pinfunction "EN_8") (pintype "input"))
    )
    (net (code "28") (name "+12V") (class "Default")
      (node (ref "C0602") (pin "1") (pinfunction "1_1") (pintype "passive"))
      (node (ref "C0603") (pin "1") (pinfunction "1_1") (pintype "passive"))
      (node (ref "C0702") (pin "1") (pinfunction "1_1") (pintype "passive"))
      (node (ref "C0703") (pin "1") (pinfunction "1_1") (pintype "passive"))
      (node (ref "C0802") (pin "1") (pinfunction "1_1") (pintype "passive"))
      (node (ref "C0803") (pin "1") (pinfunction "1_1") (pintype "passive"))
      (node (ref "C1201") (pin "1") (pinfunction "1_1") (pintype "passive"))
      (node (ref "C1202") (pin "1") (pinfunction "1_1") (pintype "passive"))
      (node (ref "C1203") (pin "1") (pinfunction "1_1") (pintype "passive"))
      (node (ref "C1204") (pin "1") (pinfunction "1_1") (pintype "passive"))
      (node (ref "U0601") (pin "6") (pinfunction "VPWR_6") (pintype "power_in"))
      (node (ref "U0701") (pin "6") (pinfunction "VPWR_6") (pintype "power_in"))
      (node (ref "U0801") (pin "6") (pinfunction "VPWR_6") (pintype "power_in"))
      (node (ref "U1201") (pin "11") (pinfunction "EN_11") (pintype "input"))
      (node (ref "U1201") (pin "12") (pinfunction "VIN_12") (pintype "power_in"))
      (node (ref "U1201") (pin "13") (pinfunction "VIN_13") (pintype "power_in"))
      (node (ref "X1211") (pin "1") (pinfunction "1_1") (pintype "passive"))
      (node (ref "X1602") (pin "17") (pinfunction "17_17") (pintype "passive"))
      (node (ref "X1602") (pin "18") (pinfunction "18_18") (pintype "passive"))
      (node (ref "X1602") (pin "19") (pinfunction "19_19") (pintype "passive"))
      (node (ref "X1602") (pin "20") (pinfunction "20_20") (pintype "passive"))
    )
    (net (code "29") (name "-1V5") (class "Default")
      (node (ref "C0943") (pin "1") (pinfunction "1_1") (pintype "passive"))
      (node (ref "C0945") (pin "2") (pinfunction "2_2") (pintype "passive"))
      (node (ref "C0952") (pin "1") (pinfunction "1_1") (pintype "passive"))
      (node (ref "L0943") (pin "1") (pinfunction "1_1") (pintype "passive"))
      (node (ref "R0945") (pin "2") (pinfunction "2_2") (pintype "passive"))
      (node (ref "U0951") (pin "2") (pinfunction "V-_2") (pintype "power_in"))
      (node (ref "U0961") (pin "2") (pinfunction "V-_2") (pintype "power_in"))
    )
    (net (code "41") (name "CAT_DTE_CTS") (class "Default")
      (node (ref "C1153") (pin "1") (pinfunction "1_1") (pintype "passive"))
      (node (ref "U1101") (pin "7") (pinfunction "T2OUT_7") (pintype "output"))
      (node (ref "X1153") (pin "1") (pinfunction "1_1") (pintype "passive"))
    )
    (net (code "42") (name "CAT_DTE_RTR") (class "Default")
      (node (ref "C1154") (pin "1") (pinfunction "1_1") (pintype "passive"))
      (node (ref "U1101") (pin "8") (pinfunction "R2IN_8") (pintype "input"))
      (node (ref "X1153") (pin "2") (pinfunction "2_2") (pintype "passive"))
    )
    (net (code "43") (name "CAT_DTE_RXD") (class "Default")
      (node (ref "C1151") (pin "1") (pinfunction "1_1") (pintype "passive"))
      (node (ref "U1101") (pin "14") (pinfunction "T1OUT_14") (pintype "output"))
      (node (ref "X1151") (pin "1") (pinfunction "1_1") (pintype "passive"))
    )
    (net (code "44") (name "CAT_DTE_TXD") (class "Default")
      (node (ref "C1152") (pin "1") (pinfunction "1_1") (pintype "passive"))
      (node (ref "U1101") (pin "13") (pinfunction "R1IN_13") (pintype "input"))
      (node (ref "X1151") (pin "2") (pinfunction "2_2") (pintype "passive"))
    )
    (net (code "45") (name "CAT_MX_C1P") (class "Default")
      (node (ref "C1102") (pin "1") (pinfunction "1_1") (pintype "passive"))
      (node (ref "U1101") (pin "1") (pinfunction "C1+_1") (pintype "bidirectional"))
    )
    (net (code "46") (name "CAT_MX_C2P") (class "Default")
      (node (ref "C1103") (pin "1") (pinfunction "1_1") (pintype "passive"))
      (node (ref "U1101") (pin "4") (pinfunction "C2+_4") (pintype "bidirectional"))
    )
    (net (code "47") (name "CAT_MX_VM") (class "Default")
      (node (ref "C1105") (pin "1") (pinfunction "1_1") (pintype "passive"))
      (node (ref "U1101") (pin "6") (pinfunction "V-_6") (pintype "bidirectional"))
    )
    (net (code "48") (name "CAT_MX_VP") (class "Default")
      (node (ref "C1104") (pin "1") (pinfunction "1_1") (pintype "passive"))
      (node (ref "U1101") (pin "2") (pinfunction "V+_2") (pintype "bidirectional"))
    )
    (net (code "49") (name "DRV_OUT_3_4") (class "Default")
      (node (ref "U0801") (pin "12") (pinfunction "OUT4_12") (pintype "passive"))
    )
    (net (code "50") (name "DRV_OUT_3_5") (class "Default")
      (node (ref "U0801") (pin "13") (pinfunction "OUT5_13") (pintype "passive"))
    )
    (net (code "51") (name "DRV_OUT_3_6") (class "Default")
      (node (ref "U0801") (pin "15") (pinfunction "OUT6_15") (pintype "passive"))
    )
    (net (code "52") (name "DRV_OUT_3_7") (class "Default")
      (node (ref "U0801") (pin "16") (pinfunction "OUT7_16") (pintype "passive"))
    )
    (net (code "53") (name "DRV_OUT_3_8") (class "Default")
      (node (ref "U0801") (pin "17") (pinfunction "OUT8_17") (pintype "passive"))
    )
    (net (code "54") (name "DRV_OUT_3_9") (class "Default")
      (node (ref "U0801") (pin "18") (pinfunction "OUT9_18") (pintype "passive"))
    )
    (net (code "55") (name "DRV_OUT_3_10") (class "Default")
      (node (ref "U0801") (pin "20") (pinfunction "OUT10_20") (pintype "passive"))
    )
    (net (code "56") (name "DRV_OUT_3_11") (class "Default")
      (node (ref "U0801") (pin "21") (pinfunction "OUT11_21") (pintype "passive"))
    )
    (net (code "57") (name "DRV_OUT_3_12") (class "Default")
      (node (ref "U0801") (pin "28") (pinfunction "OUT12_28") (pintype "passive"))
    )
    (net (code "58") (name "DRV_OUT_3_13") (class "Default")
      (node (ref "U0801") (pin "29") (pinfunction "OUT13_29") (pintype "passive"))
    )
    (net (code "59") (name "DRV_OUT_3_14") (class "Default")
      (node (ref "U0801") (pin "31") (pinfunction "OUT14_31") (pintype "passive"))
    )
    (net (code "60") (name "DRV_OUT_3_15") (class "Default")
      (node (ref "U0801") (pin "32") (pinfunction "OUT15_32") (pintype "passive"))
    )
    (net (code "61") (name "GND") (class "Default")
      (node (ref "C0213") (pin "2") (pinfunction "2_2") (pintype "passive"))
      (node (ref "C0311") (pin "2") (pinfunction "2_2") (pintype "passive"))
      (node (ref "C0331") (pin "+") (pinfunction "A_+") (pintype "passive"))
      (node (ref "C0332") (pin "2") (pinfunction "2_2") (pintype "passive"))
      (node (ref "C0401") (pin "2") (pinfunction "2_2") (pintype "passive"))
      (node (ref "C0402") (pin "2") (pinfunction "2_2") (pintype "passive"))
      (node (ref "C0403") (pin "2") (pinfunction "2_2") (pintype "passive"))
      (node (ref "C0410") (pin "2") (pinfunction "2_2") (pintype "passive"))
      (node (ref "C0412") (pin "2") (pinfunction "2_2") (pintype "passive"))
      (node (ref "C0413") (pin "2") (pinfunction "2_2") (pintype "passive"))
      (node (ref "C0451") (pin "2") (pinfunction "2_2") (pintype "passive"))
      (node (ref "C0601") (pin "1") (pinfunction "1_1") (pintype "passive"))
      (node (ref "C0602") (pin "2") (pinfunction "2_2") (pintype "passive"))
      (node (ref "C0603") (pin "2") (pinfunction "2_2") (pintype "passive"))
      (node (ref "C0701") (pin "1") (pinfunction "1_1") (pintype "passive"))
      (node (ref "C0702") (pin "2") (pinfunction "2_2") (pintype "passive"))
      (node (ref "C0703") (pin "2") (pinfunction "2_2") (pintype "passive"))
      (node (ref "C0801") (pin "1") (pinfunction "1_1") (pintype "passive"))
      (node (ref "C0802") (pin "2") (pinfunction "2_2") (pintype "passive"))
      (node (ref "C0803") (pin "2") (pinfunction "2_2") (pintype "passive"))
      (node (ref "C0901") (pin "2") (pinfunction "2_2") (pintype "passive"))
      (node (ref "C0911") (pin "2") (pinfunction "2_2") (pintype "passive"))
      (node (ref "C0921") (pin "2") (pinfunction "2_2") (pintype "passive"))
      (node (ref "C0941") (pin "2") (pinfunction "2_2") (pintype "passive"))
      (node (ref "C0943") (pin "2") (pinfunction "2_2") (pintype "passive"))
      (node (ref "C0951") (pin "2") (pinfunction "2_2") (pintype "passive"))
      (node (ref "C0952") (pin "2") (pinfunction "2_2") (pintype "passive"))
      (node (ref "C0962") (pin "2") (pinfunction "2_2") (pintype "passive"))
      (node (ref "C1001") (pin "2") (pinfunction "2_2") (pintype "passive"))
      (node (ref "C1004") (pin "2") (pinfunction "2_2") (pintype "passive"))
      (node (ref "C1005") (pin "2") (pinfunction "2_2") (pintype "passive"))
      (node (ref "C1051") (pin "2") (pinfunction "2_2") (pintype "passive"))
      (node (ref "C1052") (pin "2") (pinfunction "2_2") (pintype "passive"))
      (node (ref "C1053") (pin "2") (pinfunction "2_2") (pintype "passive"))
      (node (ref "C1054") (pin "2") (pinfunction "2_2") (pintype "passive"))
      (node (ref "C1101") (pin "2") (pinfunction "2_2") (pintype "passive"))
      (node (ref "C1104") (pin "2") (pinfunction "2_2") (pintype "passive"))
      (node (ref "C1105") (pin "2") (pinfunction "2_2") (pintype "passive"))
      (node (ref "C1151") (pin "2") (pinfunction "2_2") (pintype "passive"))
      (node (ref "C1152") (pin "2") (pinfunction "2_2") (pintype "passive"))
      (node (ref "C1153") (pin "2") (pinfunction "2_2") (pintype "passive"))
      (node (ref "C1154") (pin "2") (pinfunction "2_2") (pintype "passive"))
      (node (ref "C1201") (pin "2") (pinfunction "2_2") (pintype "passive"))
      (node (ref "C1202") (pin "2") (pinfunction "2_2") (pintype "passive"))
      (node (ref "C1203") (pin "2") (pinfunction "2_2") (pintype "passive"))
      (node (ref "C1204") (pin "2") (pinfunction "2_2") (pintype "passive"))
      (node (ref "C1205") (pin "1") (pinfunction "1_1") (pintype "passive"))
      (node (ref "C1212") (pin "2") (pinfunction "2_2") (pintype "passive"))
      (node (ref "C1221") (pin "2") (pinfunction "2_2") (pintype "passive"))
      (node (ref "C1222") (pin "2") (pinfunction "2_2") (pintype "passive"))
      (node (ref "C1223") (pin "2") (pinfunction "2_2") (pintype "passive"))
      (node (ref "C1301") (pin "2") (pinfunction "2_2") (pintype "passive"))
      (node (ref "C1311") (pin "2") (pinfunction "2_2") (pintype "passive"))
      (node (ref "C1403") (pin "1") (pinfunction "1_1") (pintype "passive"))
      (node (ref "D0942") (pin "C") (pinfunction "C_C") (pintype "passive"))
      (node (ref "D0971") (pin "C") (pinfunction "C_C") (pintype "passive"))
      (node (ref "H1711") (pin "B3,0") (pinfunction "MOUNT_B3,0") (pintype "passive"))
      (node (ref "H1721") (pin "B3,0") (pinfunction "MOUNT_B3,0") (pintype "passive"))
      (node (ref "H1731") (pin "B3,0") (pinfunction "MOUNT_B3,0") (pintype "passive"))
      (node (ref "H1751") (pin "B3,0") (pinfunction "MOUNT_B3,0") (pintype "passive"))
      (node (ref "H1761") (pin "B3,0") (pinfunction "MOUNT_B3,0") (pintype "passive"))
      (node (ref "R0221") (pin "1") (pinfunction "1_1") (pintype "passive"))
      (node (ref "R0232") (pin "1") (pinfunction "1_1") (pintype "passive"))
      (node (ref "R0441") (pin "1") (pinfunction "1_1") (pintype "passive"))
      (node (ref "R0902") (pin "1") (pinfunction "1_1") (pintype "passive"))
      (node (ref "R0912") (pin "1") (pinfunction "1_1") (pintype "passive"))
      (node (ref "R0923") (pin "1") (pinfunction "1_1") (pintype "passive"))
      (node (ref "R0946") (pin "1") (pinfunction "1_1") (pintype "passive"))
      (node (ref "R1301") (pin "1") (pinfunction "1_1") (pintype "passive"))
      (node (ref "R1402") (pin "1") (pinfunction "1_1") (pintype "passive"))
      (node (ref "S0212") (pin "1") (pinfunction "P_1") (pintype "passive"))
      (node (ref "U0101") (pin "18") (pinfunction "VSS_18") (pintype "passive"))
      (node (ref "U0101") (pin "31") (pinfunction "VSS_31") (pintype "passive"))
      (node (ref "U0101") (pin "47") (pinfunction "VSS_47") (pintype "passive"))
      (node (ref "U0101") (pin "63") (pinfunction "VSS_63") (pintype "passive"))
      (node (ref "U0601") (pin "10") (pinfunction "GND_MC_10") (pintype "passive"))
      (node (ref "U0601") (pin "23") (pinfunction "GND_MC_23") (pintype "passive"))
      (node (ref "U0601") (pin "24") (pinfunction "GND_MC_24") (pintype "passive"))
      (node (ref "U0601") (pin "25") (pinfunction "GND_MC_25") (pintype "passive"))
      (node (ref "U0601") (pin "26") (pinfunction "GND_MC_26") (pintype "passive"))
      (node (ref "U0601") (pin "33") (pinfunction "EP_33") (pintype "passive"))
      (node (ref "U0601") (pin "7") (pinfunction "GND_MC_7") (pintype "passive"))
      (node (ref "U0601") (pin "8") (pinfunction "GND_MC_8") (pintype "passive"))
      (node (ref "U0601") (pin "9") (pinfunction "GND_MC_9") (pintype "passive"))
      (node (ref "U0701") (pin "10") (pinfunction "GND_MC_10") (pintype "passive"))
      (node (ref "U0701") (pin "23") (pinfunction "GND_MC_23") (pintype "passive"))
      (node (ref "U0701") (pin "24") (pinfunction "GND_MC_24") (pintype "passive"))
      (node (ref "U0701") (pin "25") (pinfunction "GND_MC_25") (pintype "passive"))
      (node (ref "U0701") (pin "26") (pinfunction "GND_MC_26") (pintype "passive"))
      (node (ref "U0701") (pin "33") (pinfunction "EP_33") (pintype "passive"))
      (node (ref "U0701") (pin "7") (pinfunction "GND_MC_7") (pintype "passive"))
      (node (ref "U0701") (pin "8") (pinfunction "GND_MC_8") (pintype "passive"))
      (node (ref "U0701") (pin "9") (pinfunction "GND_MC_9") (pintype "passive"))
      (node (ref "U0801") (pin "10") (pinfunction "GND_MC_10") (pintype "passive"))
      (node (ref "U0801") (pin "23") (pinfunction "GND_MC_23") (pintype "passive"))
      (node (ref "U0801") (pin "24") (pinfunction "GND_MC_24") (pintype "passive"))
      (node (ref "U0801") (pin "25") (pinfunction "GND_MC_25") (pintype "passive"))
      (node (ref "U0801") (pin "26") (pinfunction "GND_MC_26") (pintype "passive"))
      (node (ref "U0801") (pin "33") (pinfunction "EP_33") (pintype "passive"))
      (node (ref "U0801") (pin "7") (pinfunction "GND_MC_7") (pintype "passive"))
      (node (ref "U0801") (pin "8") (pinfunction "GND_MC_8") (pintype "passive"))
      (node (ref "U0801") (pin "9") (pinfunction "GND_MC_9") (pintype "passive"))
      (node (ref "U0921") (pin "4") (pinfunction "4_4") (pintype "passive"))
      (node (ref "U0941") (pin "2") (pinfunction "GND_2") (pintype "passive"))
      (node (ref "U0951") (pin "3") (pinfunction "+IN_3") (pintype "input"))
      (node (ref "U0961") (pin "3") (pinfunction "+IN_3") (pintype "input"))
      (node (ref "U0962") (pin "1") (pinfunction "HVC/A0_1") (pintype "input"))
      (node (ref "U0962") (pin "12") (pinfunction "A2_12") (pintype "input"))
      (node (ref "U0962") (pin "13") (pinfunction "A1_13") (pintype "input"))
      (node (ref "U0962") (pin "4") (pinfunction "VSS_4") (pintype "passive"))
      (node (ref "U1001") (pin "15") (pinfunction "GND_15") (pintype "power_in"))
      (node (ref "U1101") (pin "15") (pinfunction "GND_15") (pintype "power_in"))
      (node (ref "U1201") (pin "10") (pinfunction "AGND_10") (pintype "passive"))
      (node (ref "U1201") (pin "15") (pinfunction "PGND_15") (pintype "passive"))
      (node (ref "U1201") (pin "16") (pinfunction "PGND_16") (pintype "passive"))
      (node (ref "U1201") (pin "6") (pinfunction "SYNC_6") (pintype "input"))
      (node (ref "U1201") (pin "7") (pinfunction "FPWM_7") (pintype "input"))
      (node (ref "U1201") (pin "PAD") (pinfunction "EP_PAD") (pintype "passive"))
      (node (ref "U1201") (pin "PAD1") (pinfunction "EP_PAD1") (pintype "passive"))
      (node (ref "U1201") (pin "PAD10") (pinfunction "EP_PAD10") (pintype "passive"))
      (node (ref "U1201") (pin "PAD11") (pinfunction "EP_PAD11") (pintype "passive"))
      (node (ref "U1201") (pin "PAD12") (pinfunction "EP_PAD12") (pintype "passive"))
      (node (ref "U1201") (pin "PAD13") (pinfunction "EP_PAD13") (pintype "passive"))
      (node (ref "U1201") (pin "PAD2") (pinfunction "EP_PAD2") (pintype "passive"))
      (node (ref "U1201") (pin "PAD3") (pinfunction "EP_PAD3") (pintype "passive"))
      (node (ref "U1201") (pin "PAD4") (pinfunction "EP_PAD4") (pintype "passive"))
      (node (ref "U1201") (pin "PAD5") (pinfunction "EP_PAD5") (pintype "passive"))
      (node (ref "U1201") (pin "PAD6") (pinfunction "EP_PAD6") (pintype "passive"))
      (node (ref "U1201") (pin "PAD7") (pinfunction "EP_PAD7") (pintype "passive"))
      (node (ref "U1201") (pin "PAD8") (pinfunction "EP_PAD8") (pintype "passive"))
      (node (ref "U1201") (pin "PAD9") (pinfunction "EP_PAD9") (pintype "passive"))
      (node (ref "U1301") (pin "10") (pinfunction "PGND_10") (pintype "passive"))
      (node (ref "U1301") (pin "3") (pinfunction "VSS_3") (pintype "passive"))
      (node (ref "U1301") (pin "7") (pinfunction "SYNC_7") (pintype "input"))
      (node (ref "X0201") (pin "3") (pinfunction "3_3") (pintype "passive"))
      (node (ref "X0201") (pin "5") (pinfunction "5_5") (pintype "passive"))
      (node (ref "X0201") (pin "9") (pinfunction "9_9") (pintype "passive"))
      (node (ref "X0501") (pin "2") (pinfunction "2_2") (pintype "passive"))
      (node (ref "X0501") (pin "4") (pinfunction "4_4") (pintype "passive"))
      (node (ref "X1052") (pin "1") (pinfunction "1_1") (pintype "passive"))
      (node (ref "X1052") (pin "2") (pinfunction "2_2") (pintype "passive"))
      (node (ref "X1152") (pin "1") (pinfunction "1_1") (pintype "passive"))
      (node (ref "X1152") (pin "2") (pinfunction "2_2") (pintype "passive"))
      (node (ref "X1211") (pin "2") (pinfunction "2_2") (pintype "passive"))
      (node (ref "X1401") (pin "GND") (pinfunction "GND_GND") (pintype "passive"))
      (node (ref "X1501") (pin "2") (pinfunction "2_2") (pintype "passive"))
      (node (ref "X1501") (pin "3") (pinfunction "2_3") (pintype "passive"))
      (node (ref "X1501") (pin "4") (pinfunction "2_4") (pintype "passive"))
      (node (ref "X1501") (pin "5") (pinfunction "2_5") (pintype "passive"))
      (node (ref "X1511") (pin "2") (pinfunction "2_2") (pintype "passive"))
      (node (ref "X1511") (pin "3") (pinfunction "2_3") (pintype "passive"))
      (node (ref "X1511") (pin "4") (pinfunction "2_4") (pintype "passive"))
      (node (ref "X1511") (pin "5") (pinfunction "2_5") (pintype "passive"))
    )
    (net (code "62") (name "MCU_NRST") (class "Default")
      (node (ref "C0213") (pin "1") (pinfunction "1_1") (pintype "passive"))
      (node (ref "S0212") (pin "2") (pinfunction "S_2") (pintype "passive"))
      (node (ref "U0101") (pin "7") (pinfunction "NRST_7") (pintype "bidirectional"))
      (node (ref "X0201") (pin "10") (pinfunction "10_10") (pintype "passive"))
    )
    (net (code "63") (name "MCU_VBAT") (class "Default")
      (node (ref "C0451") (pin "1") (pinfunction "1_1") (pintype "passive"))
      (node (ref "TP_VBAT") (pin "TP") (pinfunction "TP_TP") (pintype "input"))
      (node (ref "U0101") (pin "1") (pinfunction "VBAT_1") (pintype "power_in"))
    )
    (net (code "64") (name "MCU_VDD") (class "Default")
      (node (ref "C0401") (pin "1") (pinfunction "1_1") (pintype "passive"))
      (node (ref "C0402") (pin "1") (pinfunction "1_1") (pintype "passive"))
      (node (ref "C0403") (pin "1") (pinfunction "1_1") (pintype "passive"))
      (node (ref "C0410") (pin "1") (pinfunction "1_1") (pintype "passive"))
      (node (ref "L0411") (pin "1") (pinfunction "1_1") (pintype "passive"))
      (node (ref "R0401") (pin "2") (pinfunction "2_2") (pintype "passive"))
      (node (ref "U0101") (pin "19") (pinfunction "VDD_19") (pintype "power_in"))
      (node (ref "U0101") (pin "32") (pinfunction "VDD_32") (pintype "power_in"))
      (node (ref "U0101") (pin "64") (pinfunction "VDD_64") (pintype "power_in"))
    )
    (net (code "65") (name "MCU_VDDA") (class "Default")
      (node (ref "C0412") (pin "1") (pinfunction "1_1") (pintype "passive"))
      (node (ref "C0413") (pin "1") (pinfunction "1_1") (pintype "passive"))
      (node (ref "L0411") (pin "2") (pinfunction "2_2") (pintype "passive"))
      (node (ref "U0101") (pin "13") (pinfunction "VDDA_VREF_P_13") (pintype "power_in"))
    )
    (net (code "66") (name "MCU_VREF_M") (class "Default")
      (node (ref "R0441") (pin "2") (pinfunction "2_2") (pintype "passive"))
      (node (ref "U0101") (pin "12") (pinfunction "VSSA_VREF_M_12") (pintype "passive"))
    )
    (net (code "67") (name "MP_CAT_CTS_R") (class "Default")
      (node (ref "R1103") (pin "2") (pinfunction "2_2") (pintype "passive"))
      (node (ref "U1101") (pin "10") (pinfunction "T2IN_10") (pintype "input"))
    )
    (net (code "68") (name "MP_CAT_RTR_R") (class "Default")
      (node (ref "R1104") (pin "2") (pinfunction "2_2") (pintype "passive"))
      (node (ref "U1101") (pin "9") (pinfunction "R2OUT_9") (pintype "output"))
    )
    (net (code "69") (name "MP_CAT_RXD_R") (class "Default")
      (node (ref "R1101") (pin "2") (pinfunction "2_2") (pintype "passive"))
      (node (ref "U1101") (pin "11") (pinfunction "T1IN_11") (pintype "input"))
    )
    (net (code "70") (name "MP_CAT_TXD_R") (class "Default")
      (node (ref "R1102") (pin "2") (pinfunction "2_2") (pintype "passive"))
      (node (ref "U1101") (pin "12") (pinfunction "R1OUT_12") (pintype "output"))
    )
    (net (code "71") (name "MP_RS_CTS_R") (class "Default")
      (node (ref "R1003") (pin "2") (pinfunction "2_2") (pintype "passive"))
      (node (ref "U1001") (pin "10") (pinfunction "T2IN_10") (pintype "input"))
    )
    (net (code "72") (name "MP_RS_RTR_R") (class "Default")
      (node (ref "R1004") (pin "2") (pinfunction "2_2") (pintype "passive"))
      (node (ref "U1001") (pin "9") (pinfunction "R2OUT_9") (pintype "output"))
    )
    (net (code "73") (name "MP_RS_RXD_R") (class "Default")
      (node (ref "R1001") (pin "2") (pinfunction "2_2") (pintype "passive"))
      (node (ref "U1001") (pin "11") (pinfunction "T1IN_11") (pintype "input"))
    )
    (net (code "74") (name "MP_RS_TXD_R") (class "Default")
      (node (ref "R1002") (pin "2") (pinfunction "2_2") (pintype "passive"))
      (node (ref "U1001") (pin "12") (pinfunction "R1OUT_12") (pintype "output"))
    )
    (net (code "75") (name "Net-(C0942-Pad2)") (class "Default")
      (node (ref "C0942") (pin "2") (pinfunction "2_2") (pintype "passive"))
      (node (ref "D0942") (pin "A") (pinfunction "A_A") (pintype "passive"))
      (node (ref "L0943") (pin "2") (pinfunction "2_2") (pintype "passive"))
    )
    (net (code "76") (name "Net-(C1211-Pad1)") (class "Default")
      (node (ref "C1211") (pin "1") (pinfunction "1_1") (pintype "passive"))
      (node (ref "L1211") (pin "2") (pinfunction "2_2") (pintype "passive"))
      (node (ref "U1201") (pin "1") (pinfunction "SW_1") (pintype "passive"))
      (node (ref "U1201") (pin "2") (pinfunction "SW_2") (pintype "passive"))
    )
    (net (code "77") (name "Net-(C1403-Pad2)") (class "Default")
      (node (ref "C1403") (pin "2") (pinfunction "2_2") (pintype "passive"))
      (node (ref "R1402") (pin "2") (pinfunction "2_2") (pintype "passive"))
      (node (ref "X1401") (pin "JSHIELD") (pinfunction "SHIELD_JSHIELD") (pintype "passive"))
      (node (ref "X1401") (pin "JSHIELD@2") (pinfunction "SHIELD_JSHIELD@2") (pintype "passive"))
      (node (ref "X1401") (pin "JSHIELD@3") (pinfunction "SHIELD_JSHIELD@3") (pintype "passive"))
      (node (ref "X1401") (pin "JSHIELD@4") (pinfunction "SHIELD_JSHIELD@4") (pintype "passive"))
      (node (ref "X1401") (pin "JSHIELD@5") (pinfunction "SHIELD_JSHIELD@5") (pintype "passive"))
      (node (ref "X1401") (pin "JSHIELD@6") (pinfunction "SHIELD_JSHIELD@6") (pintype "passive"))
    )
    (net (code "78") (name "Net-(R0901-Pad2)") (class "Default")
      (node (ref "R0901") (pin "2") (pinfunction "2_2") (pintype "passive"))
      (node (ref "R0902") (pin "2") (pinfunction "2_2") (pintype "passive"))
      (node (ref "R0903") (pin "1") (pinfunction "1_1") (pintype "passive"))
    )
    (net (code "79") (name "Net-(R0911-Pad2)") (class "Default")
      (node (ref "R0911") (pin "2") (pinfunction "2_2") (pintype "passive"))
      (node (ref "R0912") (pin "2") (pinfunction "2_2") (pintype "passive"))
      (node (ref "R0913") (pin "1") (pinfunction "1_1") (pintype "passive"))
    )
    (net (code "80") (name "Net-(U0601-SO)") (class "Default")
      (node (ref "R0611") (pin "2") (pinfunction "2_2") (pintype "passive"))
      (node (ref "U0601") (pin "22") (pinfunction "SO_22") (pintype "output"))
    )
    (net (code "81") (name "Net-(U0701-SO)") (class "Default")
      (node (ref "R0711") (pin "2") (pinfunction "2_2") (pintype "passive"))
      (node (ref "U0701") (pin "22") (pinfunction "SO_22") (pintype "output"))
    )
    (net (code "82") (name "Net-(U0801-SO)") (class "Default")
      (node (ref "R0811") (pin "2") (pinfunction "2_2") (pintype "passive"))
      (node (ref "U0801") (pin "22") (pinfunction "SO_22") (pintype "output"))
    )
    (net (code "83") (name "Net-(U0941-NFB)") (class "Default")
      (node (ref "C0945") (pin "1") (pinfunction "1_1") (pintype "passive"))
      (node (ref "R0945") (pin "1") (pinfunction "1_1") (pintype "passive"))
      (node (ref "R0946") (pin "2") (pinfunction "2_2") (pintype "passive"))
      (node (ref "U0941") (pin "3") (pinfunction "NFB_3") (pintype "input"))
    )
    (net (code "84") (name "Net-(U0941-SW)") (class "Default")
      (node (ref "C0942") (pin "1") (pinfunction "1_1") (pintype "passive"))
      (node (ref "L0941") (pin "1") (pinfunction "1_1") (pintype "passive"))
      (node (ref "U0941") (pin "1") (pinfunction "SW_1") (pintype "output"))
    )
    (net (code "85") (name "Net-(U0951-OUT)") (class "Default")
      (node (ref "D0951") (pin "C") (pinfunction "C_C") (pintype "passive"))
      (node (ref "R0961") (pin "1") (pinfunction "1_1") (pintype "passive"))
      (node (ref "U0951") (pin "1") (pinfunction "OUT_1") (pintype "output"))
    )
    (net (code "86") (name "Net-(U0961--IN)") (class "Default")
      (node (ref "C0963") (pin "1") (pinfunction "1_1") (pintype "passive"))
      (node (ref "R0961") (pin "2") (pinfunction "2_2") (pintype "passive"))
      (node (ref "R0962") (pin "1") (pinfunction "1_1") (pintype "passive"))
      (node (ref "U0961") (pin "4") (pinfunction "-IN_4") (pintype "input"))
      (node (ref "U0962") (pin "6") (pinfunction "P1W_6") (pintype "passive"))
    )
    (net (code "87") (name "Net-(U0961-OUT)") (class "Default")
      (node (ref "C0963") (pin "2") (pinfunction "2_2") (pintype "passive"))
      (node (ref "R0963") (pin "2") (pinfunction "2_2") (pintype "passive"))
      (node (ref "R0972") (pin "1") (pinfunction "1_1") (pintype "passive"))
      (node (ref "U0961") (pin "1") (pinfunction "OUT_1") (pintype "output"))
    )
    (net (code "88") (name "Net-(U0962-P0W)") (class "Default")
      (node (ref "R0962") (pin "2") (pinfunction "2_2") (pintype "passive"))
      (node (ref "U0962") (pin "9") (pinfunction "P0W_9") (pintype "passive"))
    )
    (net (code "89") (name "Net-(U0962-P1A)") (class "Default")
      (node (ref "R0963") (pin "1") (pinfunction "1_1") (pintype "passive"))
      (node (ref "U0962") (pin "7") (pinfunction "P1A_7") (pintype "passive"))
    )
    (net (code "90") (name "Net-(U1001A-C1-)") (class "Default")
      (node (ref "C1002") (pin "2") (pinfunction "2_2") (pintype "passive"))
      (node (ref "U1001") (pin "3") (pinfunction "C1-_3") (pintype "bidirectional"))
    )
    (net (code "91") (name "Net-(U1001A-C2-)") (class "Default")
      (node (ref "C1003") (pin "2") (pinfunction "2_2") (pintype "passive"))
      (node (ref "U1001") (pin "5") (pinfunction "C2-_5") (pintype "bidirectional"))
    )
    (net (code "92") (name "Net-(U1101A-C1-)") (class "Default")
      (node (ref "C1102") (pin "2") (pinfunction "2_2") (pintype "passive"))
      (node (ref "U1101") (pin "3") (pinfunction "C1-_3") (pintype "bidirectional"))
    )
    (net (code "93") (name "Net-(U1101A-C2-)") (class "Default")
      (node (ref "C1103") (pin "2") (pinfunction "2_2") (pintype "passive"))
      (node (ref "U1101") (pin "5") (pinfunction "C2-_5") (pintype "bidirectional"))
    )
    (net (code "94") (name "Net-(U1201-BIAS)") (class "Default")
      (node (ref "C1212") (pin "1") (pinfunction "1_1") (pintype "passive"))
      (node (ref "R1211") (pin "1") (pinfunction "1_1") (pintype "passive"))
      (node (ref "U1201") (pin "5") (pinfunction "BIAS_5") (pintype "power_in"))
    )
    (net (code "95") (name "Net-(U1201-CBOOT)") (class "Default")
      (node (ref "C1211") (pin "2") (pinfunction "2_2") (pintype "passive"))
      (node (ref "U1201") (pin "3") (pinfunction "CBOOT_3") (pintype "passive"))
    )
    (net (code "96") (name "Net-(U1201-VCC)") (class "Default")
      (node (ref "C1205") (pin "2") (pinfunction "2_2") (pintype "passive"))
      (node (ref "U1201") (pin "4") (pinfunction "VCC_4") (pintype "passive"))
    )
    (net (code "97") (name "Net-(U1301-LBI)") (class "Default")
      (node (ref "R1301") (pin "2") (pinfunction "2_2") (pintype "passive"))
      (node (ref "R1302") (pin "1") (pinfunction "1_1") (pintype "passive"))
      (node (ref "U1301") (pin "6") (pinfunction "LBI_6") (pintype "input"))
    )
    (net (code "98") (name "Net-(U1301-SW)") (class "Default")
      (node (ref "L1311") (pin "2") (pinfunction "2_2") (pintype "passive"))
      (node (ref "L1311") (pin "4") (pinfunction "2_4") (pintype "passive"))
      (node (ref "U1301") (pin "9") (pinfunction "SW_9") (pintype "passive"))
    )
    (net (code "99") (name "PA0") (class "Default")
      (node (ref "R1101") (pin "1") (pinfunction "1_1") (pintype "passive"))
      (node (ref "U0101") (pin "14") (pinfunction "PA0_WKUP_14") (pintype "bidirectional"))
    )
    (net (code "100") (name "PA1") (class "Default")
      (node (ref "R1102") (pin "1") (pinfunction "1_1") (pintype "passive"))
      (node (ref "U0101") (pin "15") (pinfunction "PA1_15") (pintype "bidirectional"))
    )
    (net (code "101") (name "PA3") (class "Default")
      (node (ref "R0922") (pin "1") (pinfunction "1_1") (pintype "passive"))
      (node (ref "U0101") (pin "17") (pinfunction "PA3_17") (pintype "bidirectional"))
    )
    (net (code "102") (name "PA5") (class "Default")
      (node (ref "R0621") (pin "1") (pinfunction "1_1") (pintype "passive"))
      (node (ref "U0101") (pin "21") (pinfunction "PA5_21") (pintype "bidirectional"))
    )
    (net (code "103") (name "PA6") (class "Default")
      (node (ref "R0622") (pin "1") (pinfunction "1_1") (pintype "passive"))
      (node (ref "U0101") (pin "22") (pinfunction "PA6_22") (pintype "bidirectional"))
    )
    (net (code "104") (name "PA7") (class "Default")
      (node (ref "R0623") (pin "1") (pinfunction "1_1") (pintype "passive"))
      (node (ref "U0101") (pin "23") (pinfunction "PA7_23") (pintype "bidirectional"))
    )
    (net (code "105") (name "PA9") (class "Default")
      (node (ref "PF1411") (pin "1") (pinfunction "1_1") (pintype "passive"))
      (node (ref "U0101") (pin "42") (pinfunction "PA9_42") (pintype "bidirectional"))
      (node (ref "X1401") (pin "VBUS") (pinfunction "J_VUSB_VBUS") (pintype "power_in"))
    )
    (net (code "106") (name "PA10") (class "Default")
      (node (ref "U0101") (pin "43") (pinfunction "PA10_43") (pintype "bidirectional"))
      (node (ref "X1401") (pin "ID") (pinfunction "J_ID_ID") (pintype "bidirectional"))
    )
    (net (code "107") (name "PA11") (class "Default")
      (node (ref "U0101") (pin "44") (pinfunction "PA11_44") (pintype "bidirectional"))
      (node (ref "X1401") (pin "D-") (pinfunction "J_D-_D-") (pintype "bidirectional"))
    )
    (net (code "108") (name "PA12") (class "Default")
      (node (ref "U0101") (pin "45") (pinfunction "PA12_45") (pintype "bidirectional"))
      (node (ref "X1401") (pin "D+") (pinfunction "J_D+_D+") (pintype "bidirectional"))
    )
    (net (code "109") (name "PA13") (class "Default")
      (node (ref "R0231") (pin "1") (pinfunction "1_1") (pintype "passive"))
      (node (ref "U0101") (pin "46") (pinfunction "PA13_JTMS_SWDIO_46") (pintype "bidirectional"))
      (node (ref "X0201") (pin "2") (pinfunction "2_2") (pintype "passive"))
    )
    (net (code "110") (name "PA14") (class "Default")
      (node (ref "R0232") (pin "2") (pinfunction "2_2") (pintype "passive"))
      (node (ref "U0101") (pin "49") (pinfunction "PA14_JTCK_SWCLK_49") (pintype "bidirectional"))
      (node (ref "X0201") (pin "4") (pinfunction "4_4") (pintype "passive"))
    )
    (net (code "111") (name "PA15") (class "Default")
      (node (ref "R1103") (pin "1") (pinfunction "1_1") (pintype "passive"))
      (node (ref "U0101") (pin "50") (pinfunction "PA15_JTDI_50") (pintype "bidirectional"))
    )
    (net (code "112") (name "PB0") (class "Default")
      (node (ref "R0624") (pin "1") (pinfunction "1_1") (pintype "passive"))
      (node (ref "U0101") (pin "26") (pinfunction "PB0_26") (pintype "bidirectional"))
    )
    (net (code "113") (name "PB1") (class "Default")
      (node (ref "R0724") (pin "1") (pinfunction "1_1") (pintype "passive"))
      (node (ref "U0101") (pin "27") (pinfunction "PB1_27") (pintype "bidirectional"))
    )
    (net (code "114") (name "PB2") (class "Default")
      (node (ref "R0824") (pin "1") (pinfunction "1_1") (pintype "passive"))
      (node (ref "U0101") (pin "28") (pinfunction "PB2_28") (pintype "bidirectional"))
    )
    (net (code "115") (name "PB6") (class "Default")
      (node (ref "R0512") (pin "1") (pinfunction "1_1") (pintype "passive"))
      (node (ref "U0101") (pin "58") (pinfunction "PB6_58") (pintype "bidirectional"))
      (node (ref "U0962") (pin "2") (pinfunction "SCL_2") (pintype "input"))
      (node (ref "X0501") (pin "1") (pinfunction "1_1") (pintype "passive"))
    )
    (net (code "116") (name "PB7") (class "Default")
      (node (ref "R1104") (pin "1") (pinfunction "1_1") (pintype "passive"))
      (node (ref "U0101") (pin "59") (pinfunction "PB7_59") (pintype "bidirectional"))
    )
    (net (code "117") (name "PB9") (class "Default")
      (node (ref "R0511") (pin "1") (pinfunction "1_1") (pintype "passive"))
      (node (ref "U0101") (pin "62") (pinfunction "PB9_62") (pintype "bidirectional"))
      (node (ref "U0962") (pin "3") (pinfunction "SDA_3") (pintype "bidirectional"))
      (node (ref "X0501") (pin "3") (pinfunction "3_3") (pintype "passive"))
    )
    (net (code "118") (name "PB10") (class "Default")
      (node (ref "R1002") (pin "1") (pinfunction "1_1") (pintype "passive"))
      (node (ref "U0101") (pin "29") (pinfunction "PB10_29") (pintype "bidirectional"))
    )
    (net (code "119") (name "PB11") (class "Default")
      (node (ref "R0626") (pin "1") (pinfunction "1_1") (pintype "passive"))
      (node (ref "U0101") (pin "30") (pinfunction "PB11_30") (pintype "bidirectional"))
    )
    (net (code "120") (name "PB12") (class "Default")
      (node (ref "R1003") (pin "1") (pinfunction "1_1") (pintype "passive"))
      (node (ref "U0101") (pin "33") (pinfunction "PB12_33") (pintype "bidirectional"))
    )
    (net (code "121") (name "PB13") (class "Default")
      (node (ref "R1004") (pin "1") (pinfunction "1_1") (pintype "passive"))
      (node (ref "U0101") (pin "34") (pinfunction "PB13_34") (pintype "bidirectional"))
    )
    (net (code "122") (name "PC0") (class "Default")
      (node (ref "R0972") (pin "2") (pinfunction "2_2") (pintype "passive"))
      (node (ref "U0101") (pin "8") (pinfunction "PC0_8") (pintype "bidirectional"))
    )
    (net (code "123") (name "PC1") (class "Default")
      (node (ref "R1001") (pin "1") (pinfunction "1_1") (pintype "passive"))
      (node (ref "U0101") (pin "9") (pinfunction "PC1_9") (pintype "bidirectional"))
    )
    (net (code "124") (name "PC2") (class "Default")
      (node (ref "D0971") (pin "A") (pinfunction "A_A") (pintype "passive"))
      (node (ref "R0971") (pin "2") (pinfunction "2_2") (pintype "passive"))
      (node (ref "U0101") (pin "10") (pinfunction "PC2_10") (pintype "bidirectional"))
    )
    (net (code "125") (name "PC3") (class "Default")
      (node (ref "R0921") (pin "1") (pinfunction "1_1") (pintype "passive"))
      (node (ref "U0101") (pin "11") (pinfunction "PC3_11") (pintype "bidirectional"))
    )
    (net (code "126") (name "PC4") (class "Default")
      (node (ref "R0625") (pin "1") (pinfunction "1_1") (pintype "passive"))
      (node (ref "U0101") (pin "24") (pinfunction "PC4_24") (pintype "bidirectional"))
    )
    (net (code "127") (name "PC14_OSC32_IN") (class "Default")
      (node (ref "C0331") (pin "-") (pinfunction "E_-") (pintype "passive"))
      (node (ref "C0332") (pin "1") (pinfunction "1_1") (pintype "passive"))
      (node (ref "Q0321") (pin "2") (pinfunction "2_2") (pintype "passive"))
      (node (ref "U0101") (pin "3") (pinfunction "PC14_OSC32_IN_3") (pintype "bidirectional"))
    )
    (net (code "128") (name "PC15_OSC32_OUT") (class "Default")
      (node (ref "C0311") (pin "1") (pinfunction "1_1") (pintype "passive"))
      (node (ref "Q0321") (pin "1") (pinfunction "1_1") (pintype "passive"))
      (node (ref "U0101") (pin "4") (pinfunction "PC15_OSC32_OUT_4") (pintype "bidirectional"))
    )
    (net (code "129") (name "PH0") (class "Default")
      (node (ref "U0101") (pin "5") (pinfunction "PH0_OSC_IN_5") (pintype "bidirectional"))
    )
    (net (code "130") (name "PH1") (class "Default")
      (node (ref "U0101") (pin "6") (pinfunction "PH1_OSC_OUT_6") (pintype "bidirectional"))
    )
    (net (code "131") (name "PH3_BOOT0") (class "Default")
      (node (ref "R0221") (pin "2") (pinfunction "2_2") (pintype "passive"))
      (node (ref "U0101") (pin "60") (pinfunction "BOOT0_60") (pintype "output"))
      (node (ref "X0222") (pin "2") (pinfunction "2_2") (pintype "passive"))
    )
    (net (code "132") (name "RELAY1") (class "Default")
      (node (ref "U0601") (pin "1") (pinfunction "OUT0_1") (pintype "passive"))
      (node (ref "X1601") (pin "1") (pinfunction "1_1") (pintype "passive"))
    )
    (net (code "133") (name "RELAY2") (class "Default")
      (node (ref "U0601") (pin "2") (pinfunction "OUT1_2") (pintype "passive"))
      (node (ref "X1601") (pin "2") (pinfunction "2_2") (pintype "passive"))
    )
    (net (code "134") (name "RELAY3") (class "Default")
      (node (ref "U0601") (pin "4") (pinfunction "OUT2_4") (pintype "passive"))
      (node (ref "X1601") (pin "3") (pinfunction "3_3") (pintype "passive"))
    )
    (net (code "135") (name "RELAY4") (class "Default")
      (node (ref "U0601") (pin "5") (pinfunction "OUT3_5") (pintype "passive"))
      (node (ref "X1601") (pin "4") (pinfunction "4_4") (pintype "passive"))
    )
    (net (code "136") (name "RELAY5") (class "Default")
      (node (ref "U0601") (pin "12") (pinfunction "OUT4_12") (pintype "passive"))
      (node (ref "X1601") (pin "5") (pinfunction "5_5") (pintype "passive"))
    )
    (net (code "137") (name "RELAY6") (class "Default")
      (node (ref "U0601") (pin "13") (pinfunction "OUT5_13") (pintype "passive"))
      (node (ref "X1601") (pin "6") (pinfunction "6_6") (pintype "passive"))
    )
    (net (code "138") (name "RELAY7") (class "Default")
      (node (ref "U0601") (pin "15") (pinfunction "OUT6_15") (pintype "passive"))
      (node (ref "X1601") (pin "7") (pinfunction "7_7") (pintype "passive"))
    )
    (net (code "139") (name "RELAY8") (class "Default")
      (node (ref "U0601") (pin "16") (pinfunction "OUT7_16") (pintype "passive"))
      (node (ref "X1601") (pin "8") (pinfunction "8_8") (pintype "passive"))
    )
    (net (code "140") (name "RELAY9") (class "Default")
      (node (ref "U0601") (pin "17") (pinfunction "OUT8_17") (pintype "passive"))
      (node (ref "X1601") (pin "9") (pinfunction "9_9") (pintype "passive"))
    )
    (net (code "141") (name "RELAY10") (class "Default")
      (node (ref "U0601") (pin "18") (pinfunction "OUT9_18") (pintype "passive"))
      (node (ref "X1601") (pin "10") (pinfunction "10_10") (pintype "passive"))
    )
    (net (code "142") (name "RELAY11") (class "Default")
      (node (ref "U0601") (pin "20") (pinfunction "OUT10_20") (pintype "passive"))
      (node (ref "X1601") (pin "11") (pinfunction "11_11") (pintype "passive"))
    )
    (net (code "143") (name "RELAY12") (class "Default")
      (node (ref "U0601") (pin "21") (pinfunction "OUT11_21") (pintype "passive"))
      (node (ref "X1601") (pin "12") (pinfunction "12_12") (pintype "passive"))
    )
    (net (code "144") (name "RELAY13") (class "Default")
      (node (ref "U0601") (pin "28") (pinfunction "OUT12_28") (pintype "passive"))
      (node (ref "X1601") (pin "13") (pinfunction "13_13") (pintype "passive"))
    )
    (net (code "145") (name "RELAY14") (class "Default")
      (node (ref "U0601") (pin "29") (pinfunction "OUT13_29") (pintype "passive"))
      (node (ref "X1601") (pin "14") (pinfunction "14_14") (pintype "passive"))
    )
    (net (code "146") (name "RELAY15") (class "Default")
      (node (ref "U0601") (pin "31") (pinfunction "OUT14_31") (pintype "passive"))
      (node (ref "X1601") (pin "15") (pinfunction "15_15") (pintype "passive"))
    )
    (net (code "147") (name "RELAY16") (class "Default")
      (node (ref "U0601") (pin "32") (pinfunction "OUT15_32") (pintype "passive"))
      (node (ref "X1601") (pin "16") (pinfunction "16_16") (pintype "passive"))
    )
    (net (code "148") (name "RELAY17") (class "Default")
      (node (ref "U0701") (pin "1") (pinfunction "OUT0_1") (pintype "passive"))
      (node (ref "X1601") (pin "17") (pinfunction "17_17") (pintype "passive"))
    )
    (net (code "149") (name "RELAY18") (class "Default")
      (node (ref "U0701") (pin "2") (pinfunction "OUT1_2") (pintype "passive"))
      (node (ref "X1601") (pin "18") (pinfunction "18_18") (pintype "passive"))
    )
    (net (code "150") (name "RELAY19") (class "Default")
      (node (ref "U0701") (pin "4") (pinfunction "OUT2_4") (pintype "passive"))
      (node (ref "X1601") (pin "19") (pinfunction "19_19") (pintype "passive"))
    )
    (net (code "151") (name "RELAY20") (class "Default")
      (node (ref "U0701") (pin "5") (pinfunction "OUT3_5") (pintype "passive"))
      (node (ref "X1601") (pin "20") (pinfunction "20_20") (pintype "passive"))
    )
    (net (code "152") (name "RELAY21") (class "Default")
      (node (ref "U0701") (pin "12") (pinfunction "OUT4_12") (pintype "passive"))
      (node (ref "X1602") (pin "1") (pinfunction "1_1") (pintype "passive"))
    )
    (net (code "153") (name "RELAY22") (class "Default")
      (node (ref "U0701") (pin "13") (pinfunction "OUT5_13") (pintype "passive"))
      (node (ref "X1602") (pin "2") (pinfunction "2_2") (pintype "passive"))
    )
    (net (code "154") (name "RELAY23") (class "Default")
      (node (ref "U0701") (pin "15") (pinfunction "OUT6_15") (pintype "passive"))
      (node (ref "X1602") (pin "3") (pinfunction "3_3") (pintype "passive"))
    )
    (net (code "155") (name "RELAY24") (class "Default")
      (node (ref "U0701") (pin "16") (pinfunction "OUT7_16") (pintype "passive"))
      (node (ref "X1602") (pin "4") (pinfunction "4_4") (pintype "passive"))
    )
    (net (code "156") (name "RELAY25") (class "Default")
      (node (ref "U0701") (pin "17") (pinfunction "OUT8_17") (pintype "passive"))
      (node (ref "X1602") (pin "5") (pinfunction "5_5") (pintype "passive"))
    )
    (net (code "157") (name "RELAY26") (class "Default")
      (node (ref "U0701") (pin "18") (pinfunction "OUT9_18") (pintype "passive"))
      (node (ref "X1602") (pin "6") (pinfunction "6_6") (pintype "passive"))
    )
    (net (code "158") (name "RELAY27") (class "Default")
      (node (ref "U0701") (pin "20") (pinfunction "OUT10_20") (pintype "passive"))
      (node (ref "X1602") (pin "7") (pinfunction "7_7") (pintype "passive"))
    )
    (net (code "159") (name "RELAY28") (class "Default")
      (node (ref "U0701") (pin "21") (pinfunction "OUT11_21") (pintype "passive"))
      (node (ref "X1602") (pin "8") (pinfunction "8_8") (pintype "passive"))
    )
    (net (code "160") (name "RELAY29") (class "Default")
      (node (ref "U0701") (pin "28") (pinfunction "OUT12_28") (pintype "passive"))
      (node (ref "X1602") (pin "9") (pinfunction "9_9") (pintype "passive"))
    )
    (net (code "161") (name "RELAY30") (class "Default")
      (node (ref "U0701") (pin "29") (pinfunction "OUT13_29") (pintype "passive"))
      (node (ref "X1602") (pin "10") (pinfunction "10_10") (pintype "passive"))
    )
    (net (code "162") (name "RELAY31") (class "Default")
      (node (ref "U0701") (pin "31") (pinfunction "OUT14_31") (pintype "passive"))
      (node (ref "X1602") (pin "11") (pinfunction "11_11") (pintype "passive"))
    )
    (net (code "163") (name "RELAY32") (class "Default")
      (node (ref "U0701") (pin "32") (pinfunction "OUT15_32") (pintype "passive"))
      (node (ref "X1602") (pin "12") (pinfunction "12_12") (pintype "passive"))
    )
    (net (code "164") (name "RELAY33") (class "Default")
      (node (ref "U0801") (pin "1") (pinfunction "OUT0_1") (pintype "passive"))
      (node (ref "X1602") (pin "13") (pinfunction "13_13") (pintype "passive"))
    )
    (net (code "165") (name "RELAY34") (class "Default")
      (node (ref "U0801") (pin "2") (pinfunction "OUT1_2") (pintype "passive"))
      (node (ref "X1602") (pin "14") (pinfunction "14_14") (pintype "passive"))
    )
    (net (code "166") (name "RELAY35") (class "Default")
      (node (ref "U0801") (pin "4") (pinfunction "OUT2_4") (pintype "passive"))
      (node (ref "X1602") (pin "15") (pinfunction "15_15") (pintype "passive"))
    )
    (net (code "167") (name "RELAY36") (class "Default")
      (node (ref "U0801") (pin "5") (pinfunction "OUT3_5") (pintype "passive"))
      (node (ref "X1602") (pin "16") (pinfunction "16_16") (pintype "passive"))
    )
    (net (code "168") (name "RM_FWD") (class "Default")
      (node (ref "L0901") (pin "2") (pinfunction "2_2") (pintype "passive"))
      (node (ref "X1501") (pin "1") (pinfunction "1_1") (pintype "passive"))
    )
    (net (code "169") (name "RM_REV") (class "Default")
      (node (ref "L0911") (pin "2") (pinfunction "2_2") (pintype "passive"))
      (node (ref "X1511") (pin "1") (pinfunction "1_1") (pintype "passive"))
    )
    (net (code "170") (name "RS_DTE_CTS") (class "Default")
      (node (ref "C1053") (pin "1") (pinfunction "1_1") (pintype "passive"))
      (node (ref "U1001") (pin "7") (pinfunction "T2OUT_7") (pintype "output"))
      (node (ref "X1053") (pin "1") (pinfunction "1_1") (pintype "passive"))
    )
    (net (code "171") (name "RS_DTE_RTR") (class "Default")
      (node (ref "C1054") (pin "1") (pinfunction "1_1") (pintype "passive"))
      (node (ref "U1001") (pin "8") (pinfunction "R2IN_8") (pintype "input"))
      (node (ref "X1053") (pin "2") (pinfunction "2_2") (pintype "passive"))
    )
    (net (code "172") (name "RS_DTE_RXD") (class "Default")
      (node (ref "C1051") (pin "1") (pinfunction "1_1") (pintype "passive"))
      (node (ref "U1001") (pin "14") (pinfunction "T1OUT_14") (pintype "output"))
      (node (ref "X1051") (pin "1") (pinfunction "1_1") (pintype "passive"))
    )
    (net (code "173") (name "RS_DTE_TXD") (class "Default")
      (node (ref "C1052") (pin "1") (pinfunction "1_1") (pintype "passive"))
      (node (ref "U1001") (pin "13") (pinfunction "R1IN_13") (pintype "input"))
      (node (ref "X1051") (pin "2") (pinfunction "2_2") (pintype "passive"))
    )
    (net (code "174") (name "RS_MX_C1P") (class "Default")
      (node (ref "C1002") (pin "1") (pinfunction "1_1") (pintype "passive"))
      (node (ref "U1001") (pin "1") (pinfunction "C1+_1") (pintype "bidirectional"))
    )
    (net (code "175") (name "RS_MX_C2P") (class "Default")
      (node (ref "C1003") (pin "1") (pinfunction "1_1") (pintype "passive"))
      (node (ref "U1001") (pin "4") (pinfunction "C2+_4") (pintype "bidirectional"))
    )
    (net (code "176") (name "RS_MX_VM") (class "Default")
      (node (ref "C1005") (pin "1") (pinfunction "1_1") (pintype "passive"))
      (node (ref "U1001") (pin "6") (pinfunction "V-_6") (pintype "bidirectional"))
    )
    (net (code "177") (name "RS_MX_VP") (class "Default")
      (node (ref "C1004") (pin "1") (pinfunction "1_1") (pintype "passive"))
      (node (ref "U1001") (pin "2") (pinfunction "V+_2") (pintype "bidirectional"))
    )
    (net (code "178") (name "SPI_DRV_C_~{CS}") (class "Default")
      (node (ref "R0724") (pin "2") (pinfunction "2_2") (pintype "passive"))
      (node (ref "U0701") (pin "14") (pinfunction "~{CS}_14") (pintype "input"))
    )
    (net (code "179") (name "SPI_DRV_EXT_~{CS}") (class "Default")
      (node (ref "R0824") (pin "2") (pinfunction "2_2") (pintype "passive"))
      (node (ref "U0801") (pin "14") (pinfunction "~{CS}_14") (pintype "input"))
    )
    (net (code "180") (name "SPI_DRV_L_~{CS}") (class "Default")
      (node (ref "R0624") (pin "2") (pinfunction "2_2") (pintype "passive"))
      (node (ref "U0601") (pin "14") (pinfunction "~{CS}_14") (pintype "input"))
    )
    (net (code "181") (name "SPI_DRV_PWM") (class "Default")
      (node (ref "R0626") (pin "2") (pinfunction "2_2") (pintype "passive"))
      (node (ref "U0601") (pin "30") (pinfunction "PWM_30") (pintype "input"))
      (node (ref "U0701") (pin "30") (pinfunction "PWM_30") (pintype "input"))
      (node (ref "U0801") (pin "30") (pinfunction "PWM_30") (pintype "input"))
    )
    (net (code "182") (name "SPI_DRV_SCLK") (class "Default")
      (node (ref "R0621") (pin "2") (pinfunction "2_2") (pintype "passive"))
      (node (ref "U0601") (pin "11") (pinfunction "SCLK_11") (pintype "input"))
      (node (ref "U0701") (pin "11") (pinfunction "SCLK_11") (pintype "input"))
      (node (ref "U0801") (pin "11") (pinfunction "SCLK_11") (pintype "input"))
    )
    (net (code "183") (name "SPI_DRV_SI") (class "Default")
      (node (ref "R0623") (pin "2") (pinfunction "2_2") (pintype "passive"))
      (node (ref "U0601") (pin "19") (pinfunction "SI_19") (pintype "input"))
      (node (ref "U0701") (pin "19") (pinfunction "SI_19") (pintype "input"))
      (node (ref "U0801") (pin "19") (pinfunction "SI_19") (pintype "input"))
    )
    (net (code "184") (name "SPI_DRV_SO") (class "Default")
      (node (ref "R0611") (pin "1") (pinfunction "1_1") (pintype "passive"))
      (node (ref "R0622") (pin "2") (pinfunction "2_2") (pintype "passive"))
      (node (ref "R0711") (pin "1") (pinfunction "1_1") (pintype "passive"))
      (node (ref "R0811") (pin "1") (pinfunction "1_1") (pintype "passive"))
    )
    (net (code "185") (name "SPI_DRV_~{RST}") (class "Default")
      (node (ref "R0625") (pin "2") (pinfunction "2_2") (pintype "passive"))
      (node (ref "U0601") (pin "27") (pinfunction "~{RST}_27") (pintype "input"))
      (node (ref "U0701") (pin "27") (pinfunction "~{RST}_27") (pintype "input"))
      (node (ref "U0801") (pin "27") (pinfunction "~{RST}_27") (pintype "input"))
    )
    (net (code "186") (name "SWR_IN_FWD") (class "Default")
      (node (ref "R0903") (pin "2") (pinfunction "2_2") (pintype "passive"))
      (node (ref "R0904") (pin "1") (pinfunction "1_1") (pintype "passive"))
      (node (ref "U0921") (pin "1") (pinfunction "1_1") (pintype "passive"))
    )
    (net (code "187") (name "SWR_IN_FWD_HI") (class "Default")
      (node (ref "C0901") (pin "1") (pinfunction "1_1") (pintype "passive"))
      (node (ref "L0901") (pin "1") (pinfunction "1_1") (pintype "passive"))
      (node (ref "R0901") (pin "1") (pinfunction "1_1") (pintype "passive"))
    )
    (net (code "188") (name "SWR_IN_REV") (class "Default")
      (node (ref "R0913") (pin "2") (pinfunction "2_2") (pintype "passive"))
      (node (ref "R0914") (pin "1") (pinfunction "1_1") (pintype "passive"))
      (node (ref "U0921") (pin "5") (pinfunction "5_5") (pintype "passive"))
    )
    (net (code "189") (name "SWR_IN_REV_HI") (class "Default")
      (node (ref "C0911") (pin "1") (pinfunction "1_1") (pintype "passive"))
      (node (ref "L0911") (pin "1") (pinfunction "1_1") (pintype "passive"))
      (node (ref "R0911") (pin "1") (pinfunction "1_1") (pintype "passive"))
    )
    (net (code "190") (name "SWR_SEL_FWD") (class "Default")
      (node (ref "R0921") (pin "2") (pinfunction "2_2") (pintype "passive"))
      (node (ref "U0921") (pin "7") (pinfunction "7_7") (pintype "input"))
    )
    (net (code "191") (name "SWR_SEL_PWR") (class "Default")
      (node (ref "D0951") (pin "A") (pinfunction "A_A") (pintype "passive"))
      (node (ref "R0923") (pin "2") (pinfunction "2_2") (pintype "passive"))
      (node (ref "U0921") (pin "2") (pinfunction "2_2") (pintype "passive"))
      (node (ref "U0921") (pin "6") (pinfunction "6_6") (pintype "passive"))
      (node (ref "U0951") (pin "4") (pinfunction "-IN_4") (pintype "input"))
    )
    (net (code "192") (name "SWR_SEL_REV") (class "Default")
      (node (ref "R0922") (pin "2") (pinfunction "2_2") (pintype "passive"))
      (node (ref "U0921") (pin "3") (pinfunction "3_3") (pintype "input"))
    )
    (net (code "193") (name "TPS_LBO") (class "Default")
      (node (ref "R1322") (pin "1") (pinfunction "1_1") (pintype "passive"))
      (node (ref "U1301") (pin "2") (pinfunction "LBO_2") (pintype "output"))
    )
    (net (code "194") (name "TPS_PG") (class "Default")
      (node (ref "R1321") (pin "1") (pinfunction "1_1") (pintype "passive"))
      (node (ref "U1301") (pin "4") (pinfunction "PG_4") (pintype "output"))
    )
    (net (code "195") (name "VDDUSB") (class "Default")
      (node (ref "D1221") (pin "A") (pinfunction "A_A") (pintype "passive"))
      (node (ref "PF1411") (pin "2") (pinfunction "2_2") (pintype "passive"))
      (node (ref "U0101") (pin "48") (pinfunction "VDDUSB_48") (pintype "power_in"))
    )
    (net (code "196") (name "unconnected-(U0101-PA2_WKUP-Pad16)") (class "Default")
      (node (ref "U0101") (pin "16") (pinfunction "PA2_WKUP_16") (pintype "bidirectional"))
    )
    (net (code "197") (name "unconnected-(U0101-PA4-Pad20)") (class "Default")
      (node (ref "U0101") (pin "20") (pinfunction "PA4_20") (pintype "bidirectional"))
    )
    (net (code "198") (name "unconnected-(U0101-PA8-Pad41)") (class "Default")
      (node (ref "U0101") (pin "41") (pinfunction "PA8_41") (pintype "bidirectional"))
    )
    (net (code "199") (name "unconnected-(U0101-PB3_JTDO_TRACESWO-Pad55)") (class "Default")
      (node (ref "U0101") (pin "55") (pinfunction "PB3_JTDO_TRACESWO_55") (pintype "bidirectional"))
    )
    (net (code "200") (name "unconnected-(U0101-PB4_NJTRST-Pad56)") (class "Default")
      (node (ref "U0101") (pin "56") (pinfunction "PB4_NJTRST_56") (pintype "bidirectional"))
    )
    (net (code "201") (name "unconnected-(U0101-PB5-Pad57)") (class "Default")
      (node (ref "U0101") (pin "57") (pinfunction "PB5_57") (pintype "bidirectional"))
    )
    (net (code "202") (name "unconnected-(U0101-PB8-Pad61)") (class "Default")
      (node (ref "U0101") (pin "61") (pinfunction "PB8_61") (pintype "bidirectional"))
    )
    (net (code "203") (name "unconnected-(U0101-PB14-Pad35)") (class "Default")
      (node (ref "U0101") (pin "35") (pinfunction "PB14_35") (pintype "bidirectional"))
    )
    (net (code "204") (name "unconnected-(U0101-PB15-Pad36)") (class "Default")
      (node (ref "U0101") (pin "36") (pinfunction "PB15_36") (pintype "bidirectional"))
    )
    (net (code "205") (name "unconnected-(U0101-PC5_WKUP-Pad25)") (class "Default")
      (node (ref "U0101") (pin "25") (pinfunction "PC5_WKUP_25") (pintype "bidirectional"))
    )
    (net (code "206") (name "unconnected-(U0101-PC6-Pad37)") (class "Default")
      (node (ref "U0101") (pin "37") (pinfunction "PC6_37") (pintype "bidirectional"))
    )
    (net (code "207") (name "unconnected-(U0101-PC7-Pad38)") (class "Default")
      (node (ref "U0101") (pin "38") (pinfunction "PC7_38") (pintype "bidirectional"))
    )
    (net (code "208") (name "unconnected-(U0101-PC8-Pad39)") (class "Default")
      (node (ref "U0101") (pin "39") (pinfunction "PC8_39") (pintype "bidirectional"))
    )
    (net (code "209") (name "unconnected-(U0101-PC9-Pad40)") (class "Default")
      (node (ref "U0101") (pin "40") (pinfunction "PC9_40") (pintype "bidirectional"))
    )
    (net (code "210") (name "unconnected-(U0101-PC10-Pad51)") (class "Default")
      (node (ref "U0101") (pin "51") (pinfunction "PC10_51") (pintype "bidirectional"))
    )
    (net (code "211") (name "unconnected-(U0101-PC11-Pad52)") (class "Default")
      (node (ref "U0101") (pin "52") (pinfunction "PC11_52") (pintype "bidirectional"))
    )
    (net (code "212") (name "unconnected-(U0101-PC12-Pad53)") (class "Default")
      (node (ref "U0101") (pin "53") (pinfunction "PC12_53") (pintype "bidirectional"))
    )
    (net (code "213") (name "unconnected-(U0101-PC13_WKUP-Pad2)") (class "Default")
      (node (ref "U0101") (pin "2") (pinfunction "PC13_WKUP_2") (pintype "bidirectional"))
    )
    (net (code "214") (name "unconnected-(U0101-PD2-Pad54)") (class "Default")
      (node (ref "U0101") (pin "54") (pinfunction "PD2_54") (pintype "bidirectional"))
    )
    (net (code "215") (name "unconnected-(U0962-P0B-Pad10)") (class "Default")
      (node (ref "U0962") (pin "10") (pinfunction "P0B_10") (pintype "passive"))
    )
    (net (code "216") (name "unconnected-(U0962-P1B-Pad5)") (class "Default")
      (node (ref "U0962") (pin "5") (pinfunction "P1B_5") (pintype "passive"))
    )
    (net (code "217") (name "unconnected-(U1201-NC-Pad14)") (class "Default")
      (node (ref "U1201") (pin "14") (pinfunction "NC_14") (pintype "no_connect"))
    )
    (net (code "218") (name "unconnected-(U1201-~{RESET}-Pad8)") (class "Default")
      (node (ref "U1201") (pin "8") (pinfunction "~{RESET}_8") (pintype "output"))
    )
    (net (code "219") (name "unconnected-(X0201-Pad6)") (class "Default")
      (node (ref "X0201") (pin "6") (pinfunction "6_6") (pintype "passive"))
    )
    (net (code "220") (name "unconnected-(X0201-Pad7)") (class "Default")
      (node (ref "X0201") (pin "7") (pinfunction "7_7") (pintype "passive"))
    )
    (net (code "221") (name "unconnected-(X0201-Pad8)") (class "Default")
      (node (ref "X0201") (pin "8") (pinfunction "8_8") (pintype "passive"))
    )
  )
)
